# DL0WH_BiTuner_MCU_1V0.net
KiCad netlist of a schematic drawn in EAGLE
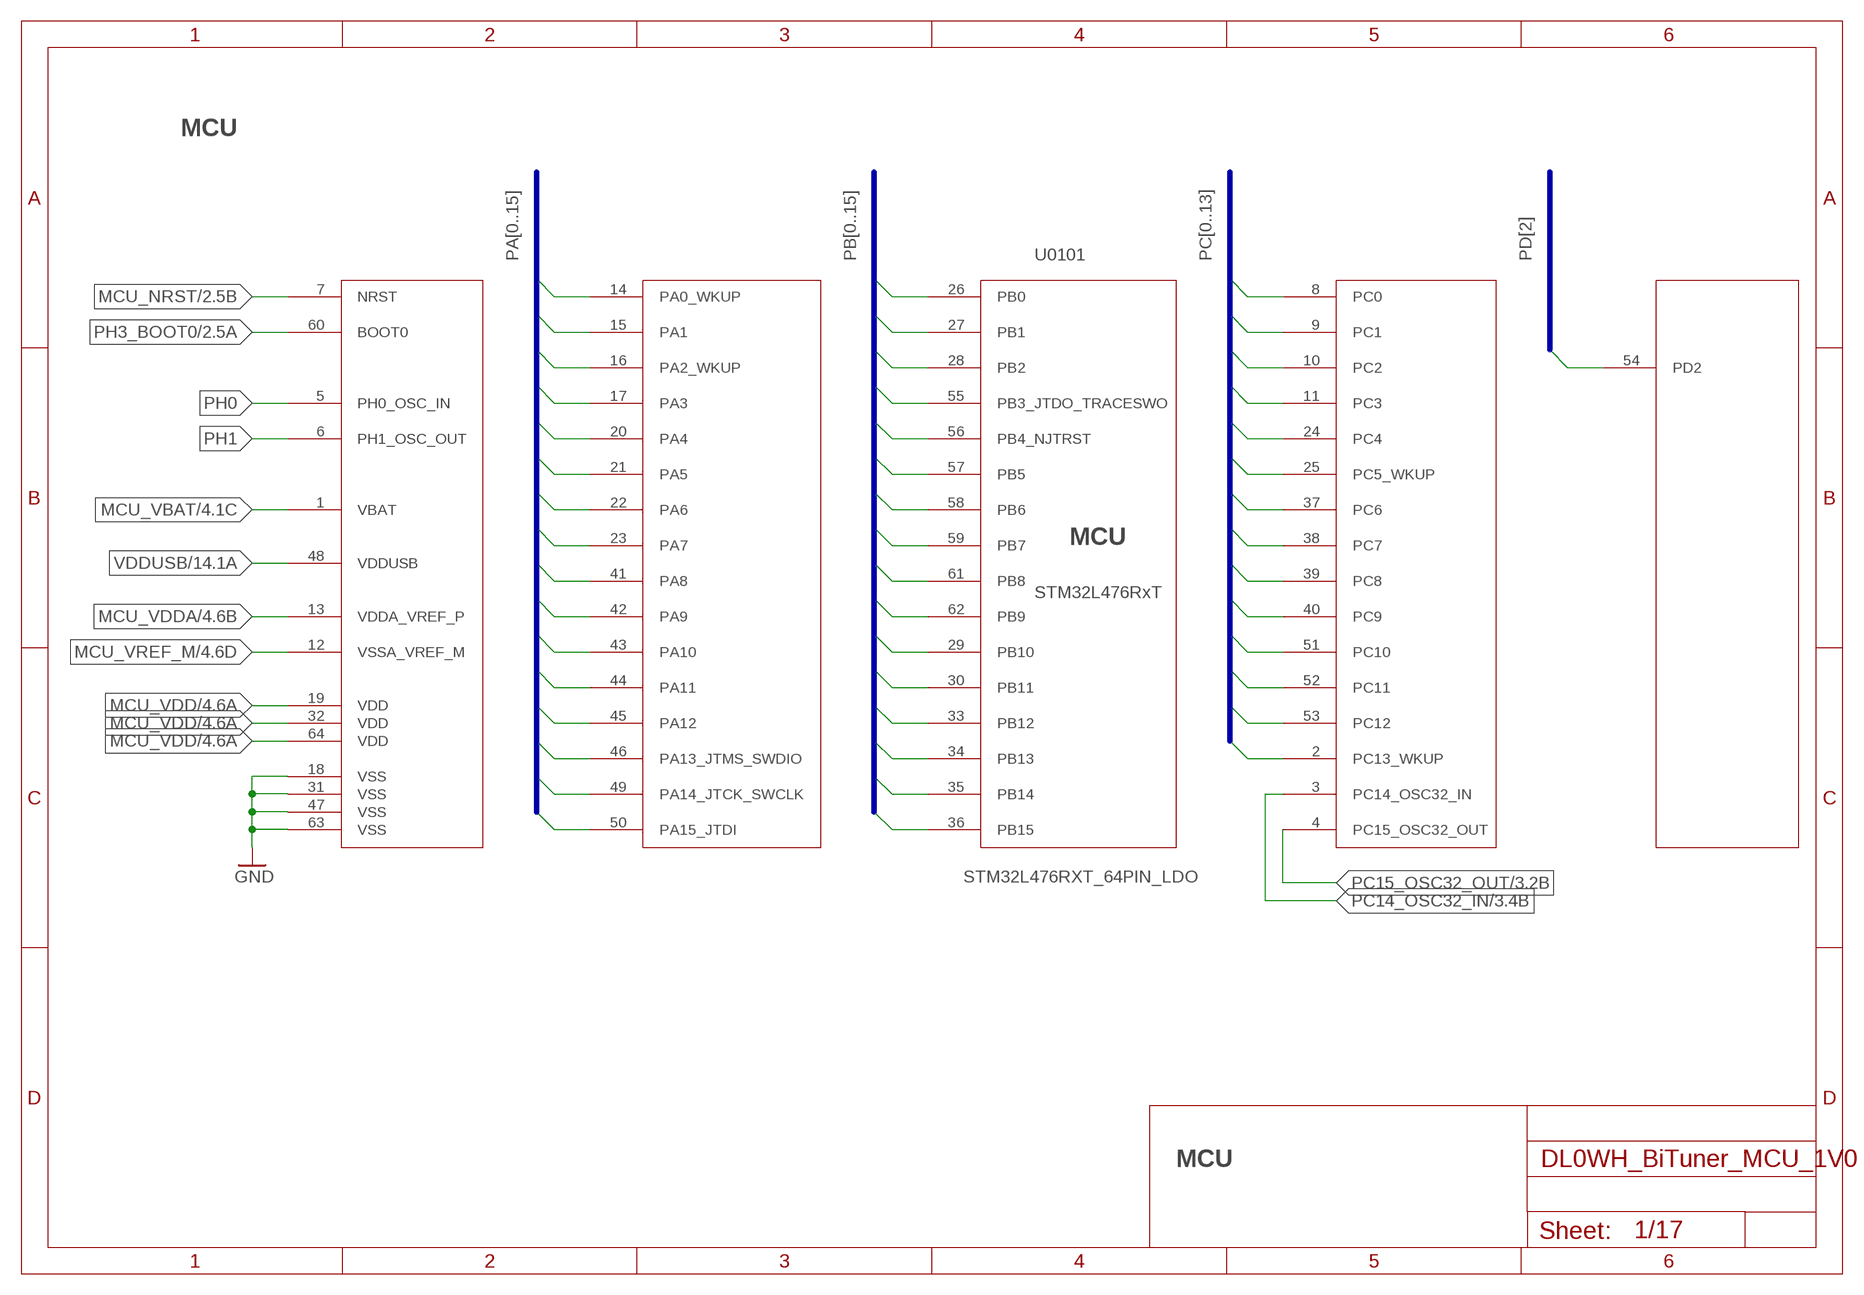
[diagram p0: schematic, sheet 1]
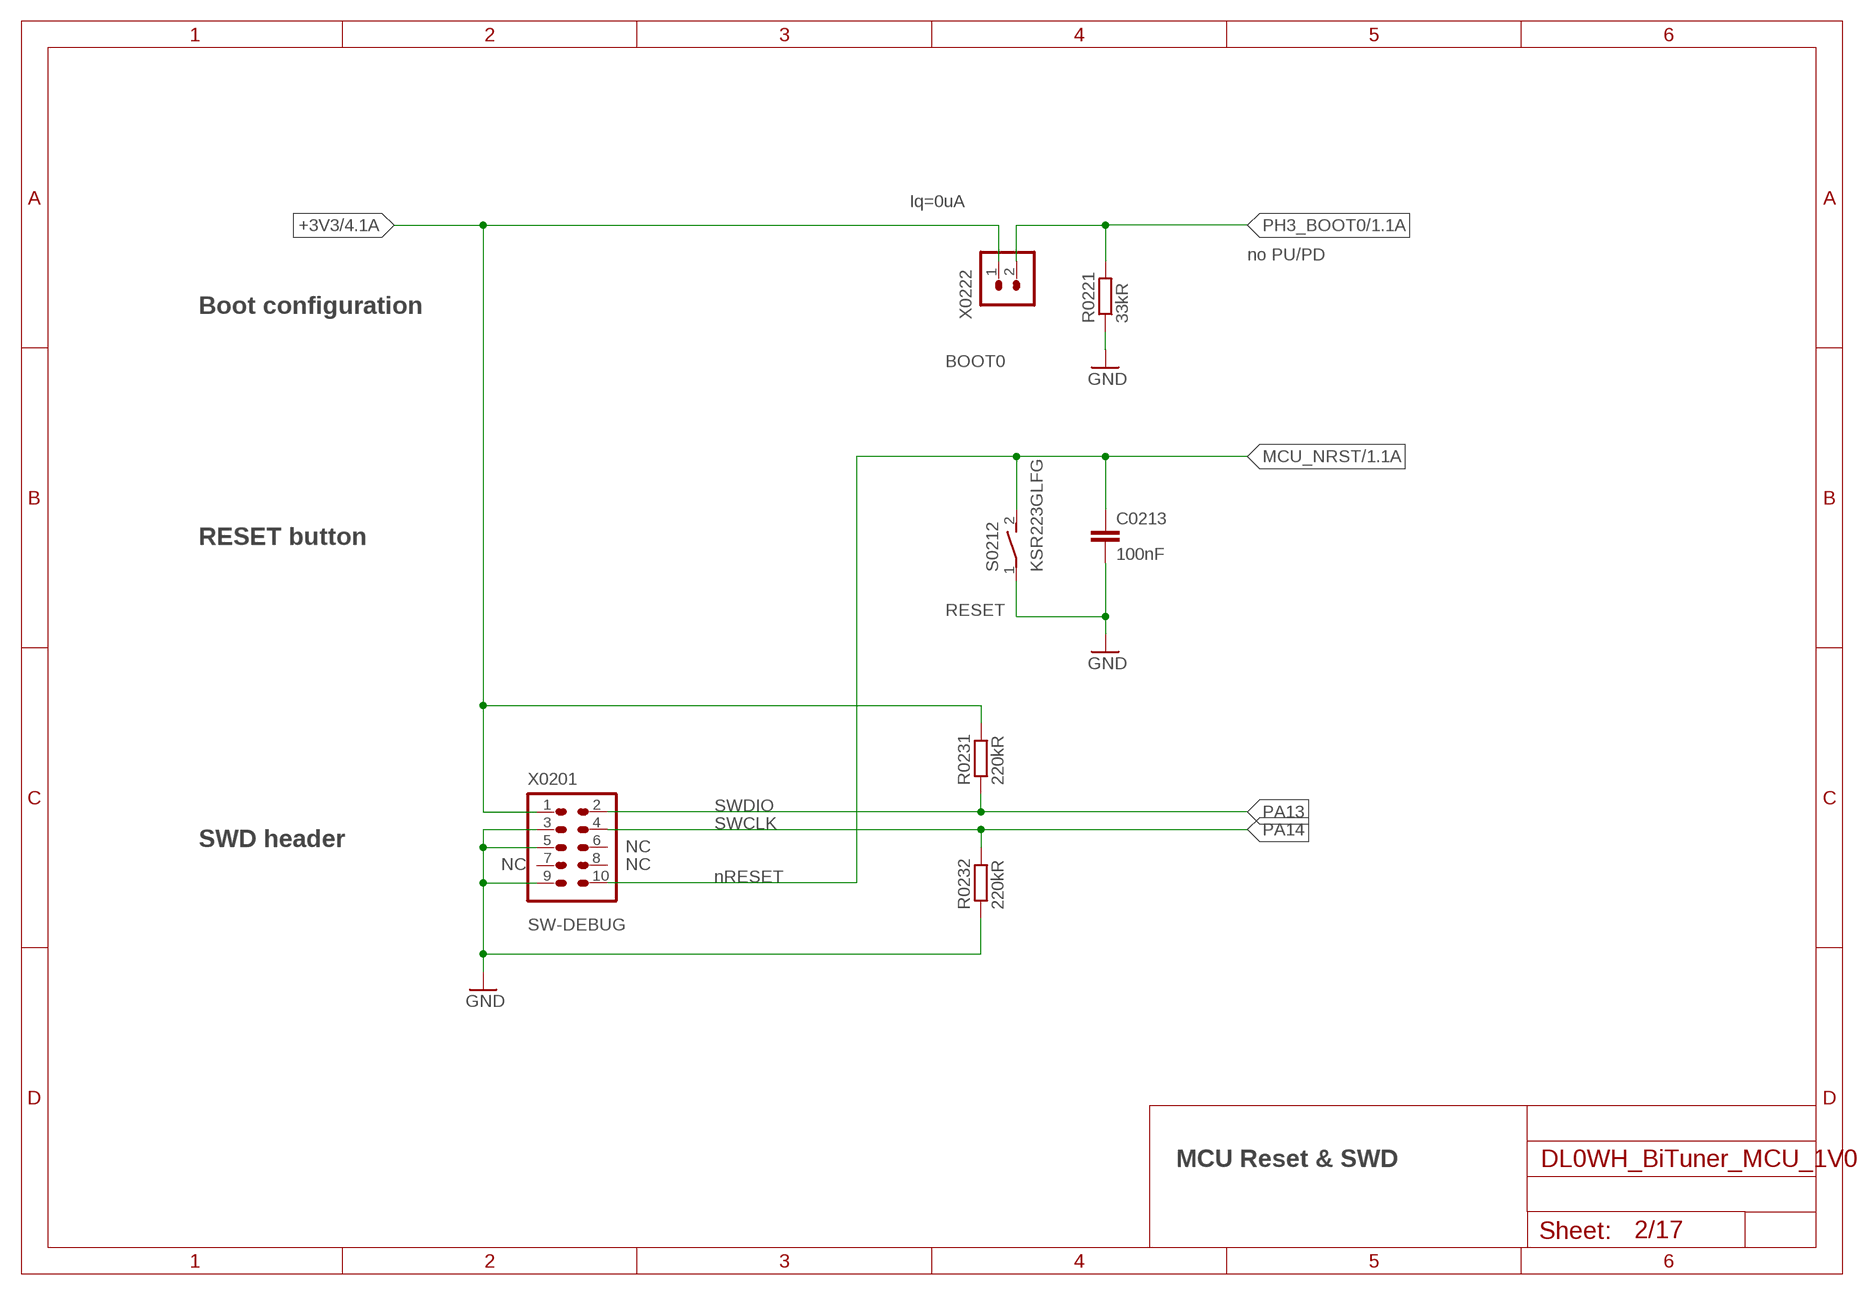
[diagram p1: schematic, sheet 2]
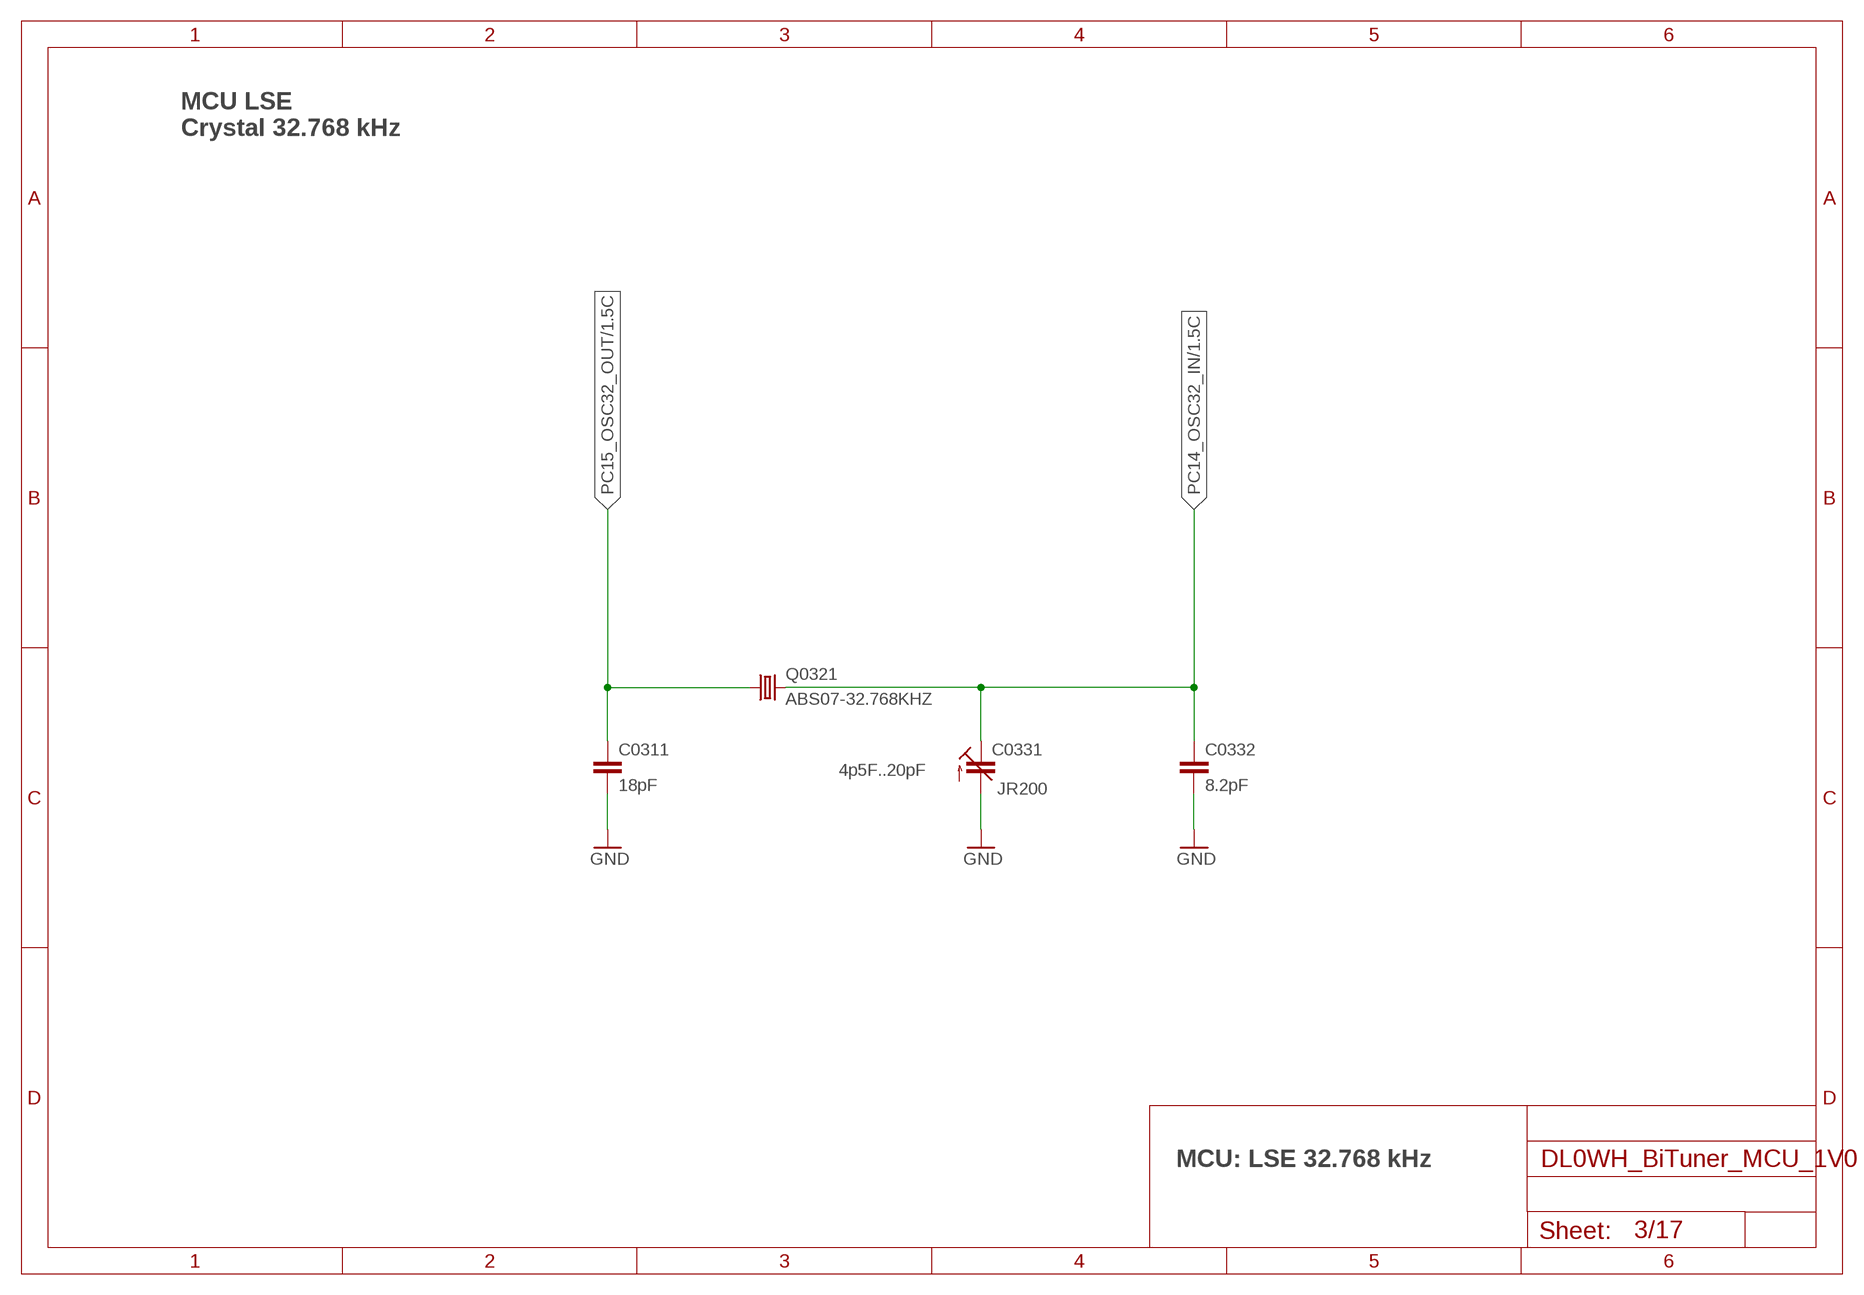
[diagram p2: schematic, sheet 3]
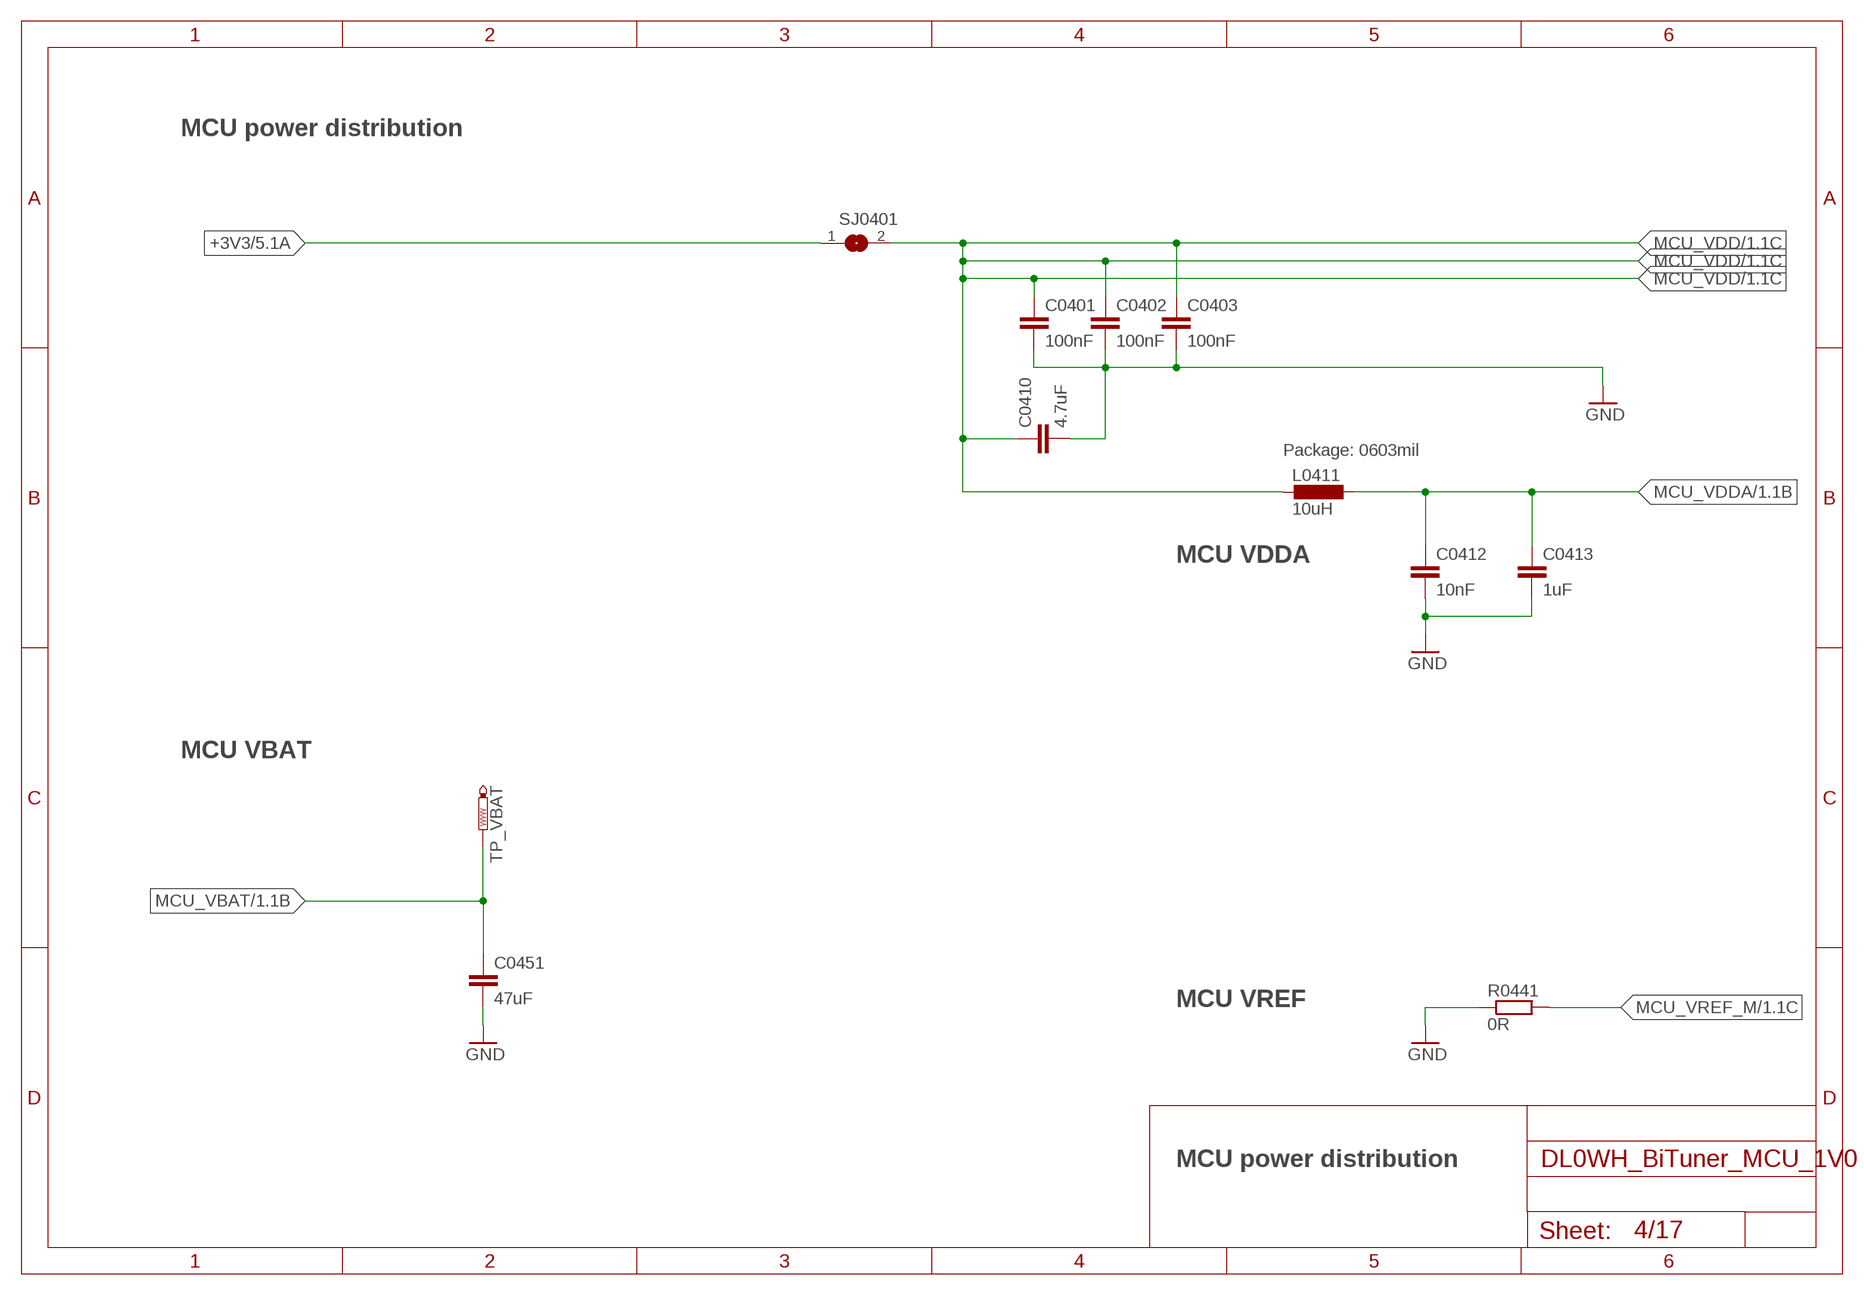
[diagram p3: schematic, sheet 4]
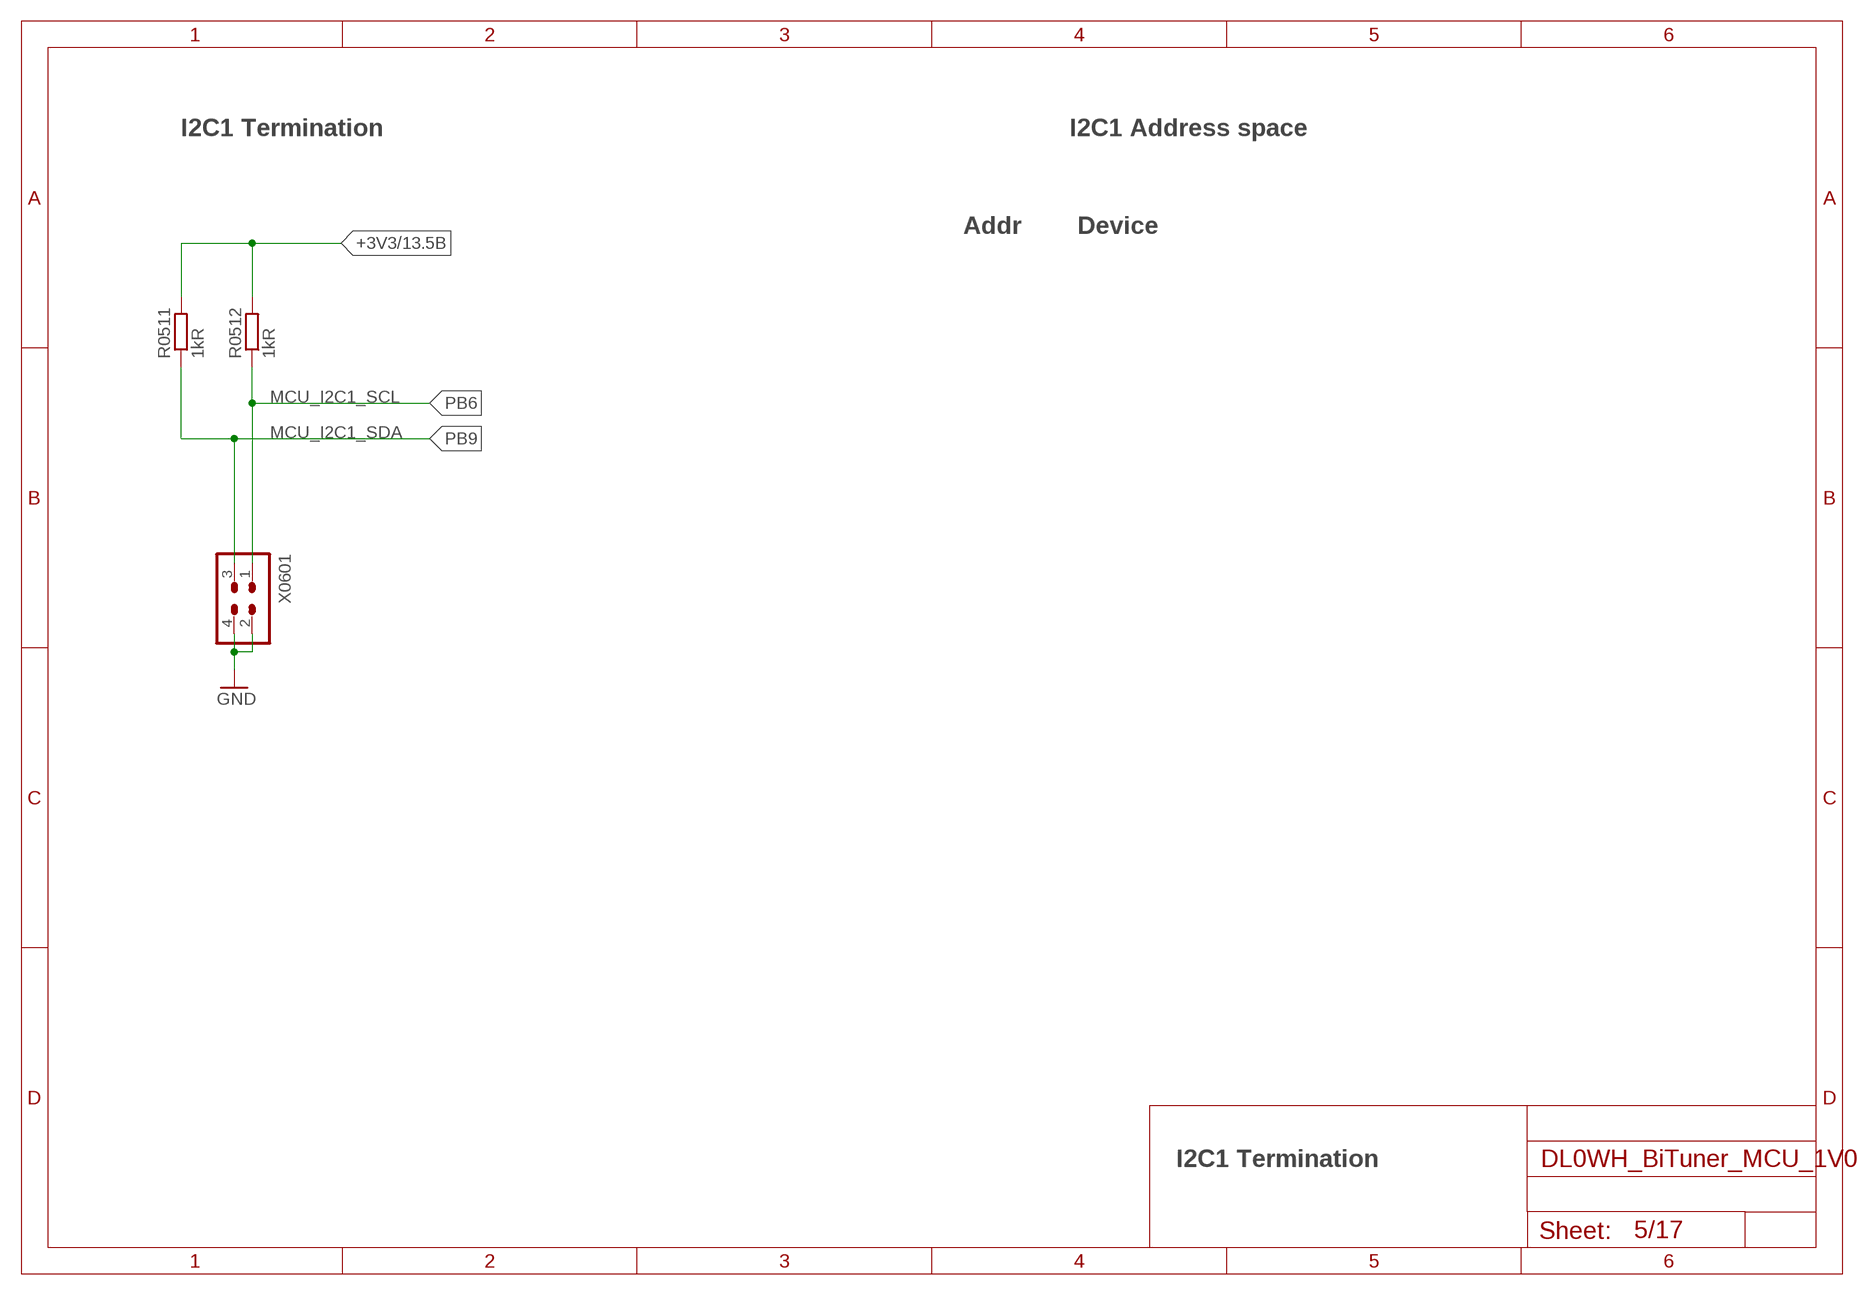
[diagram p4: schematic, sheet 5]
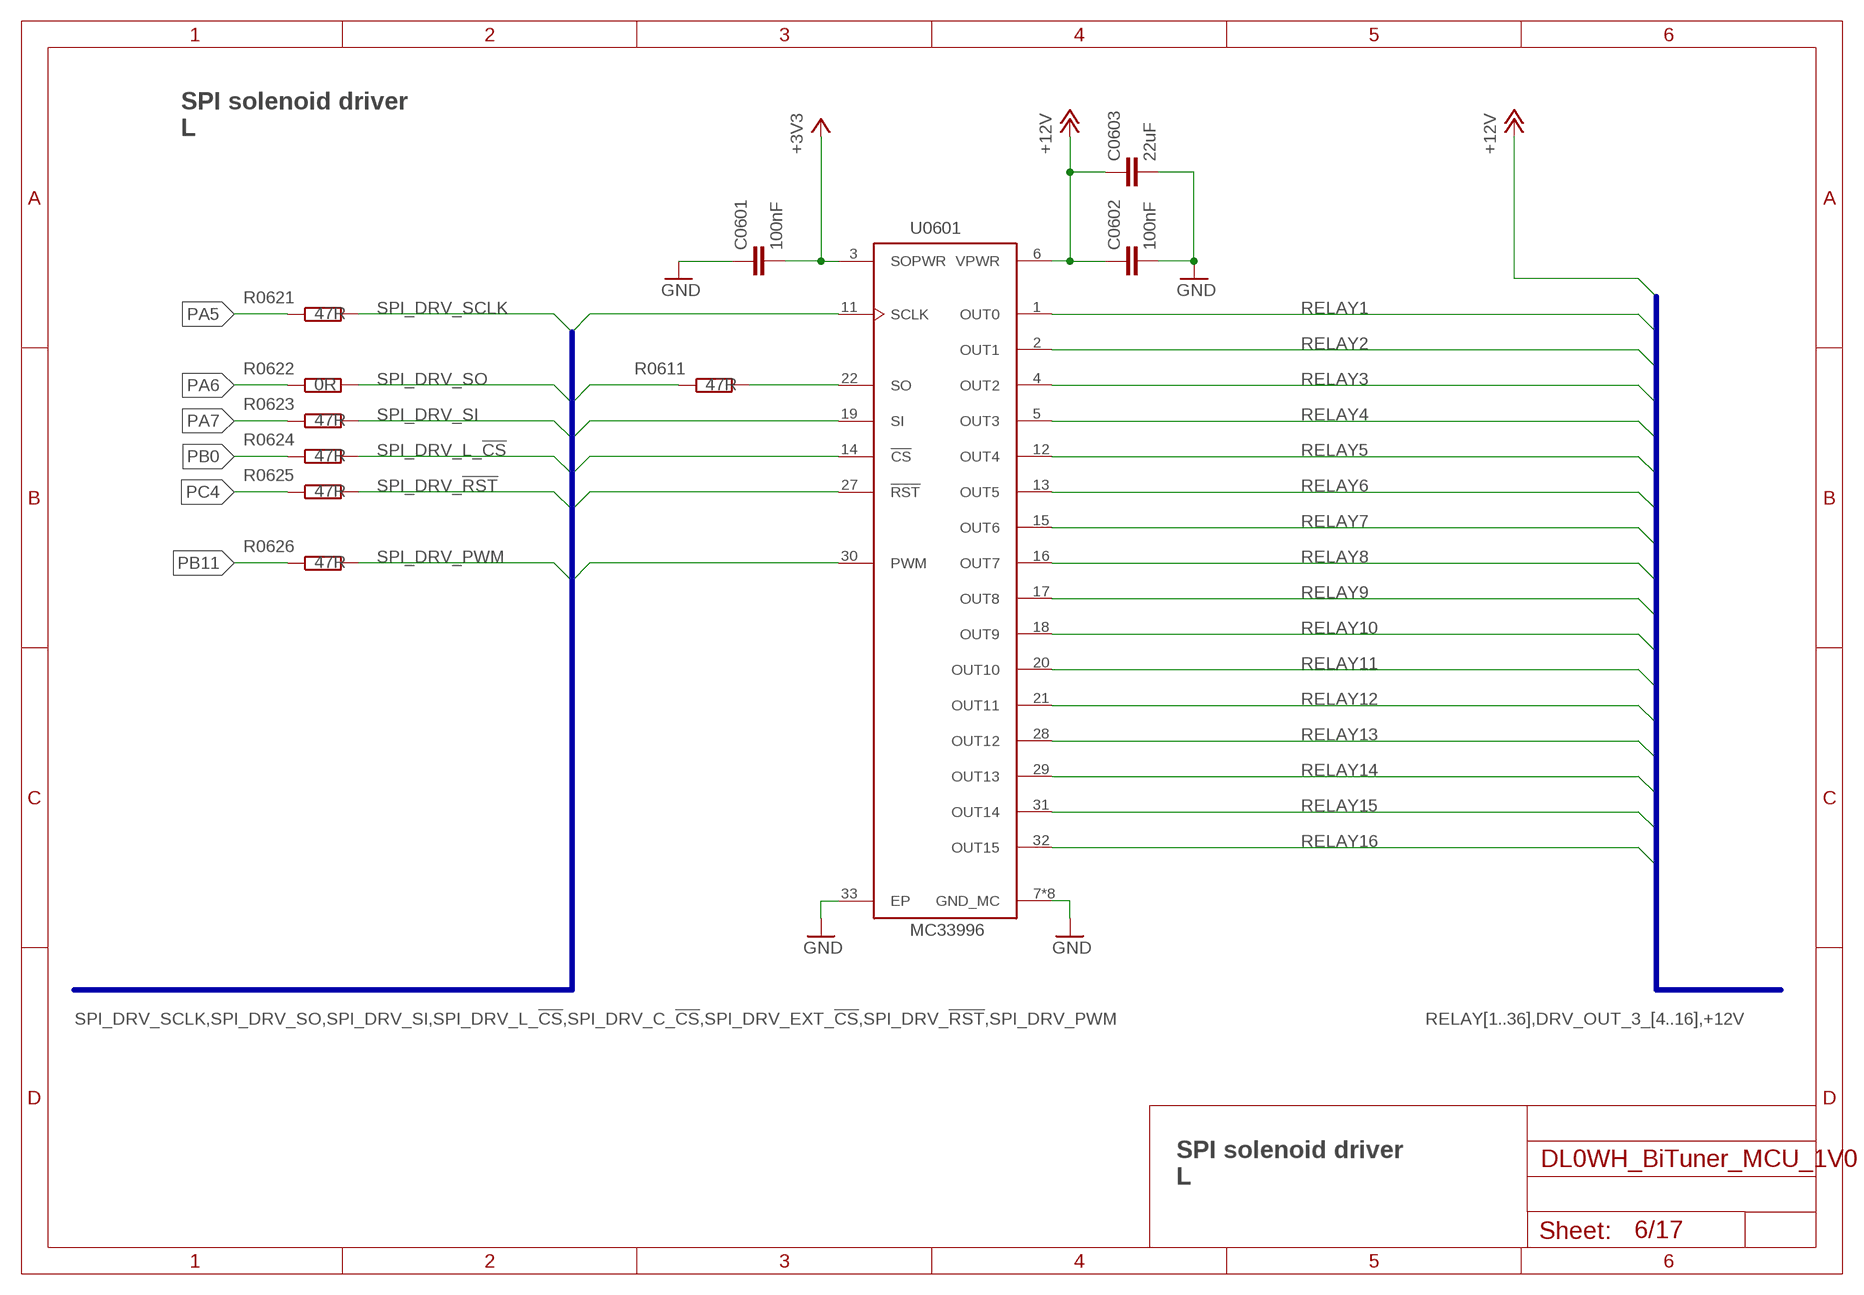
[diagram p5: schematic, sheet 6]
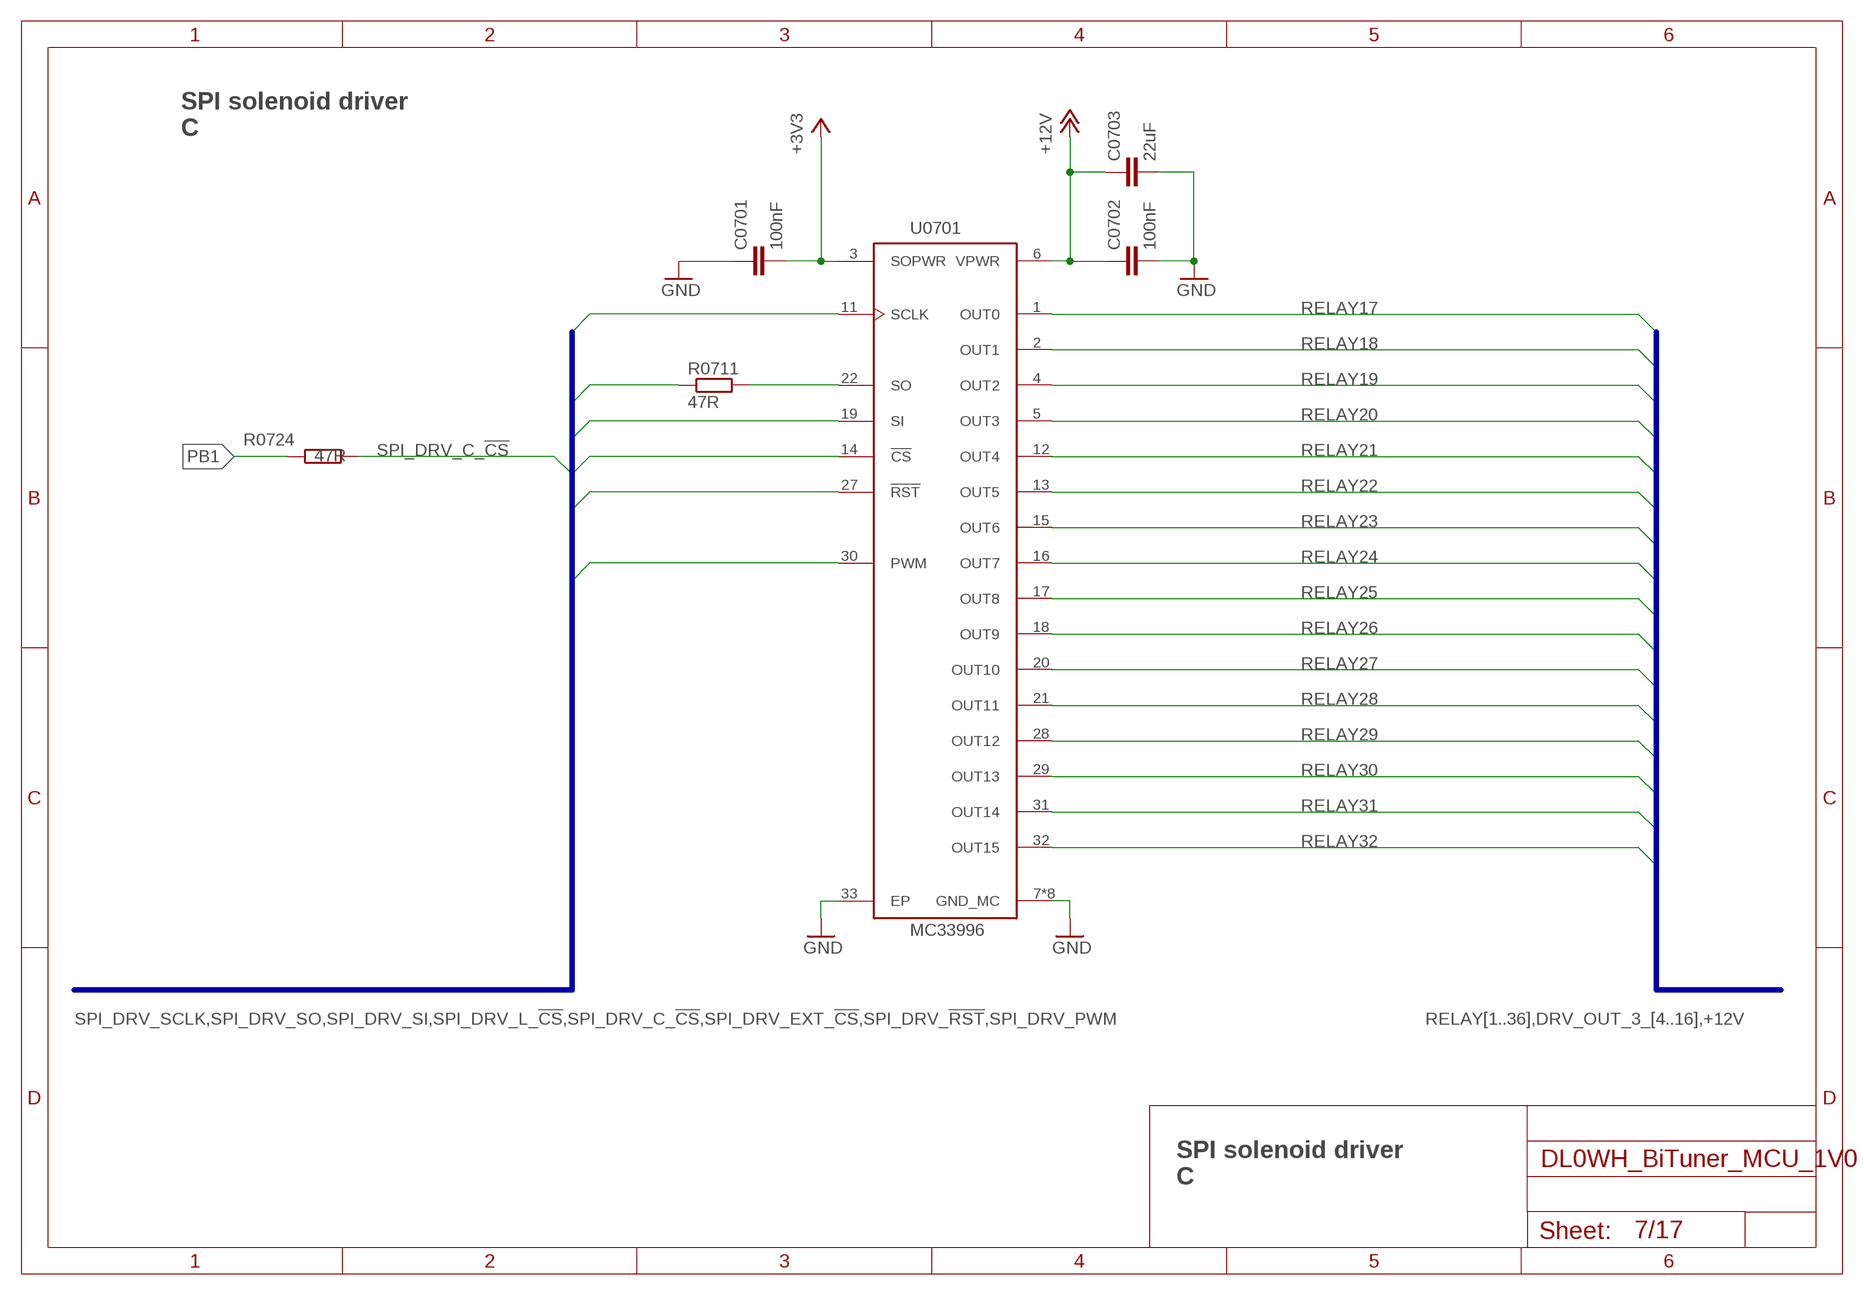
[diagram p6: schematic, sheet 7]
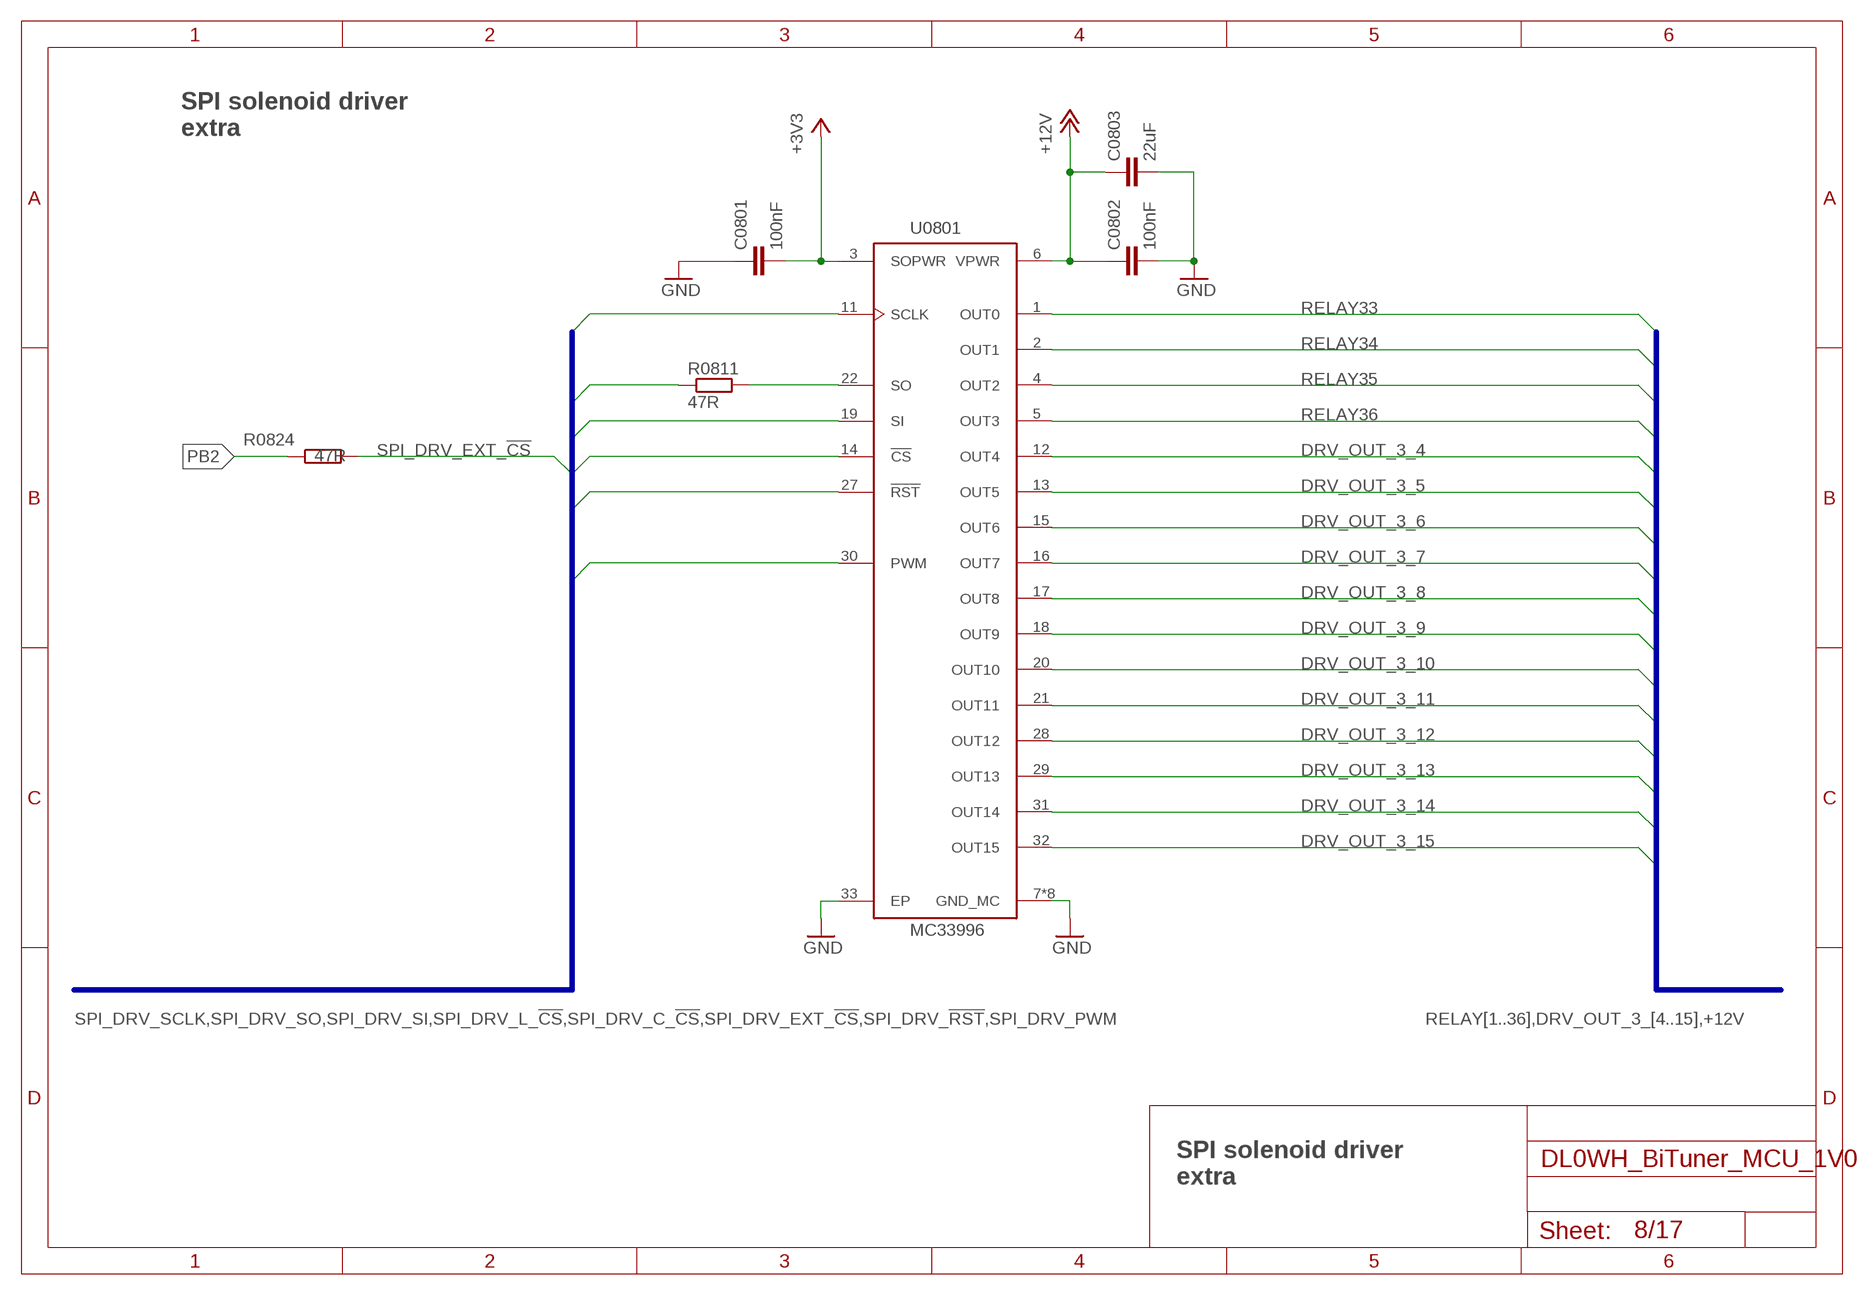
[diagram p7: schematic, sheet 8]
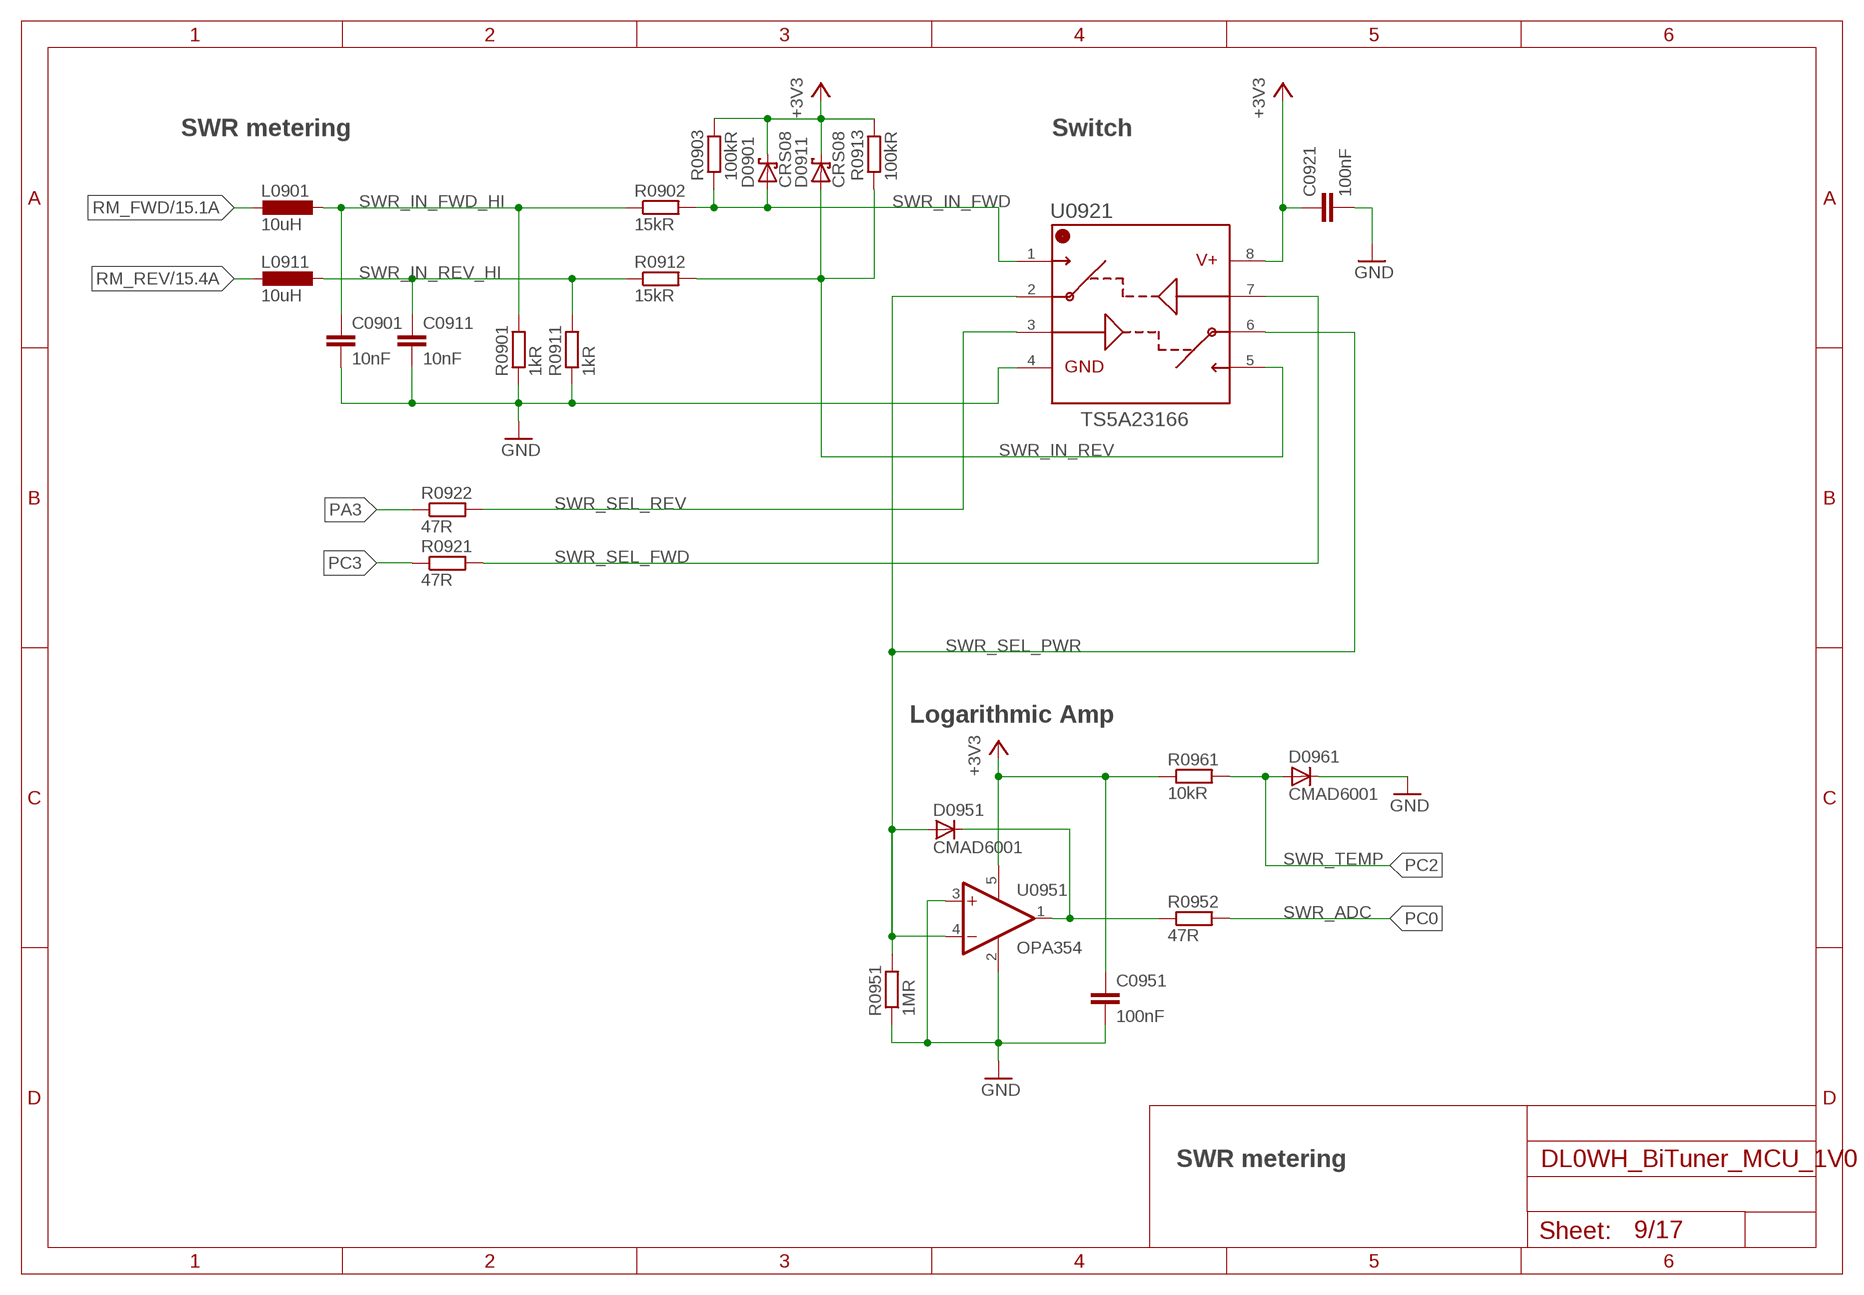
[diagram p8: schematic, sheet 9]
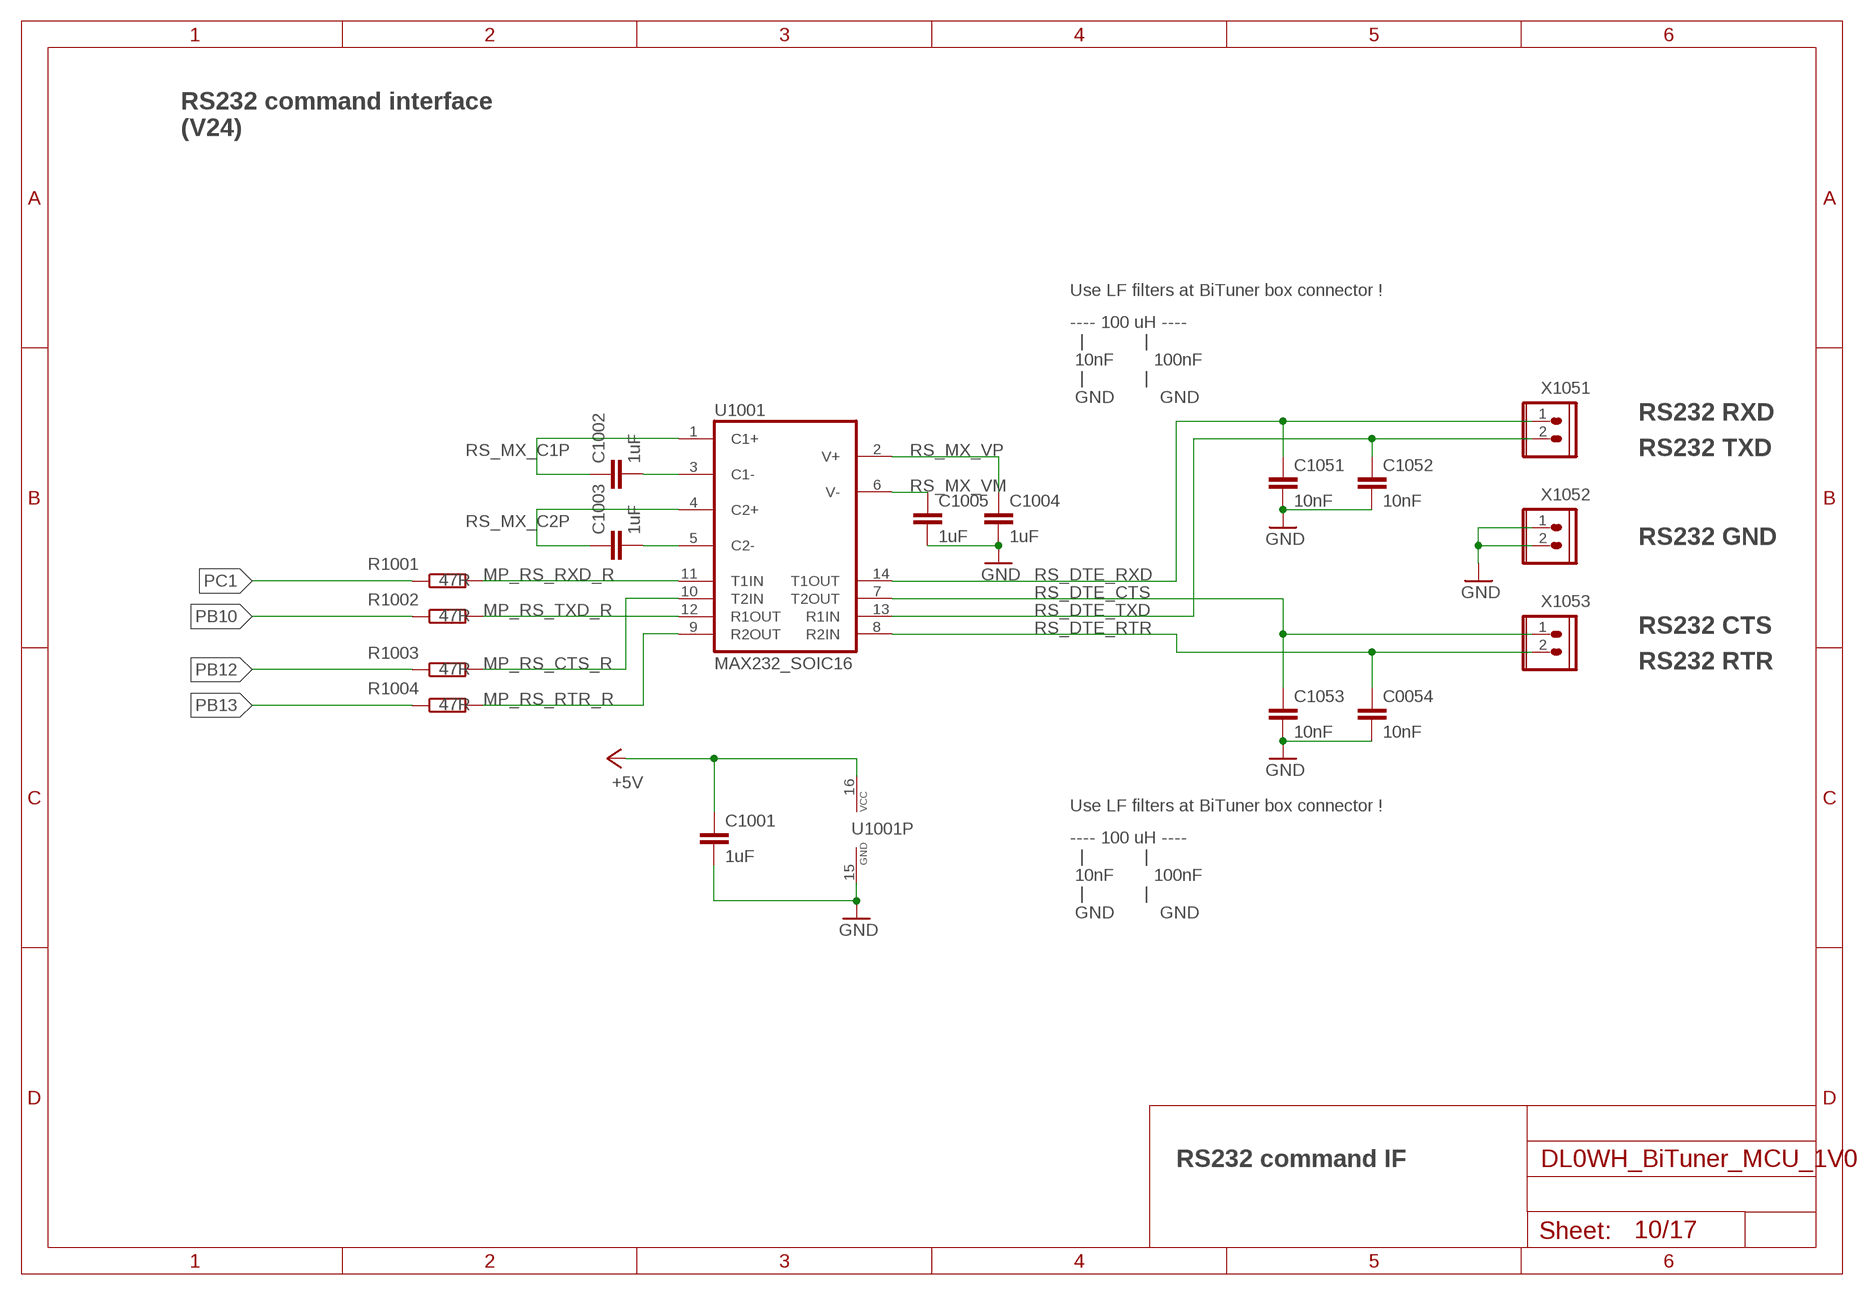
[diagram p9: schematic, sheet 10]
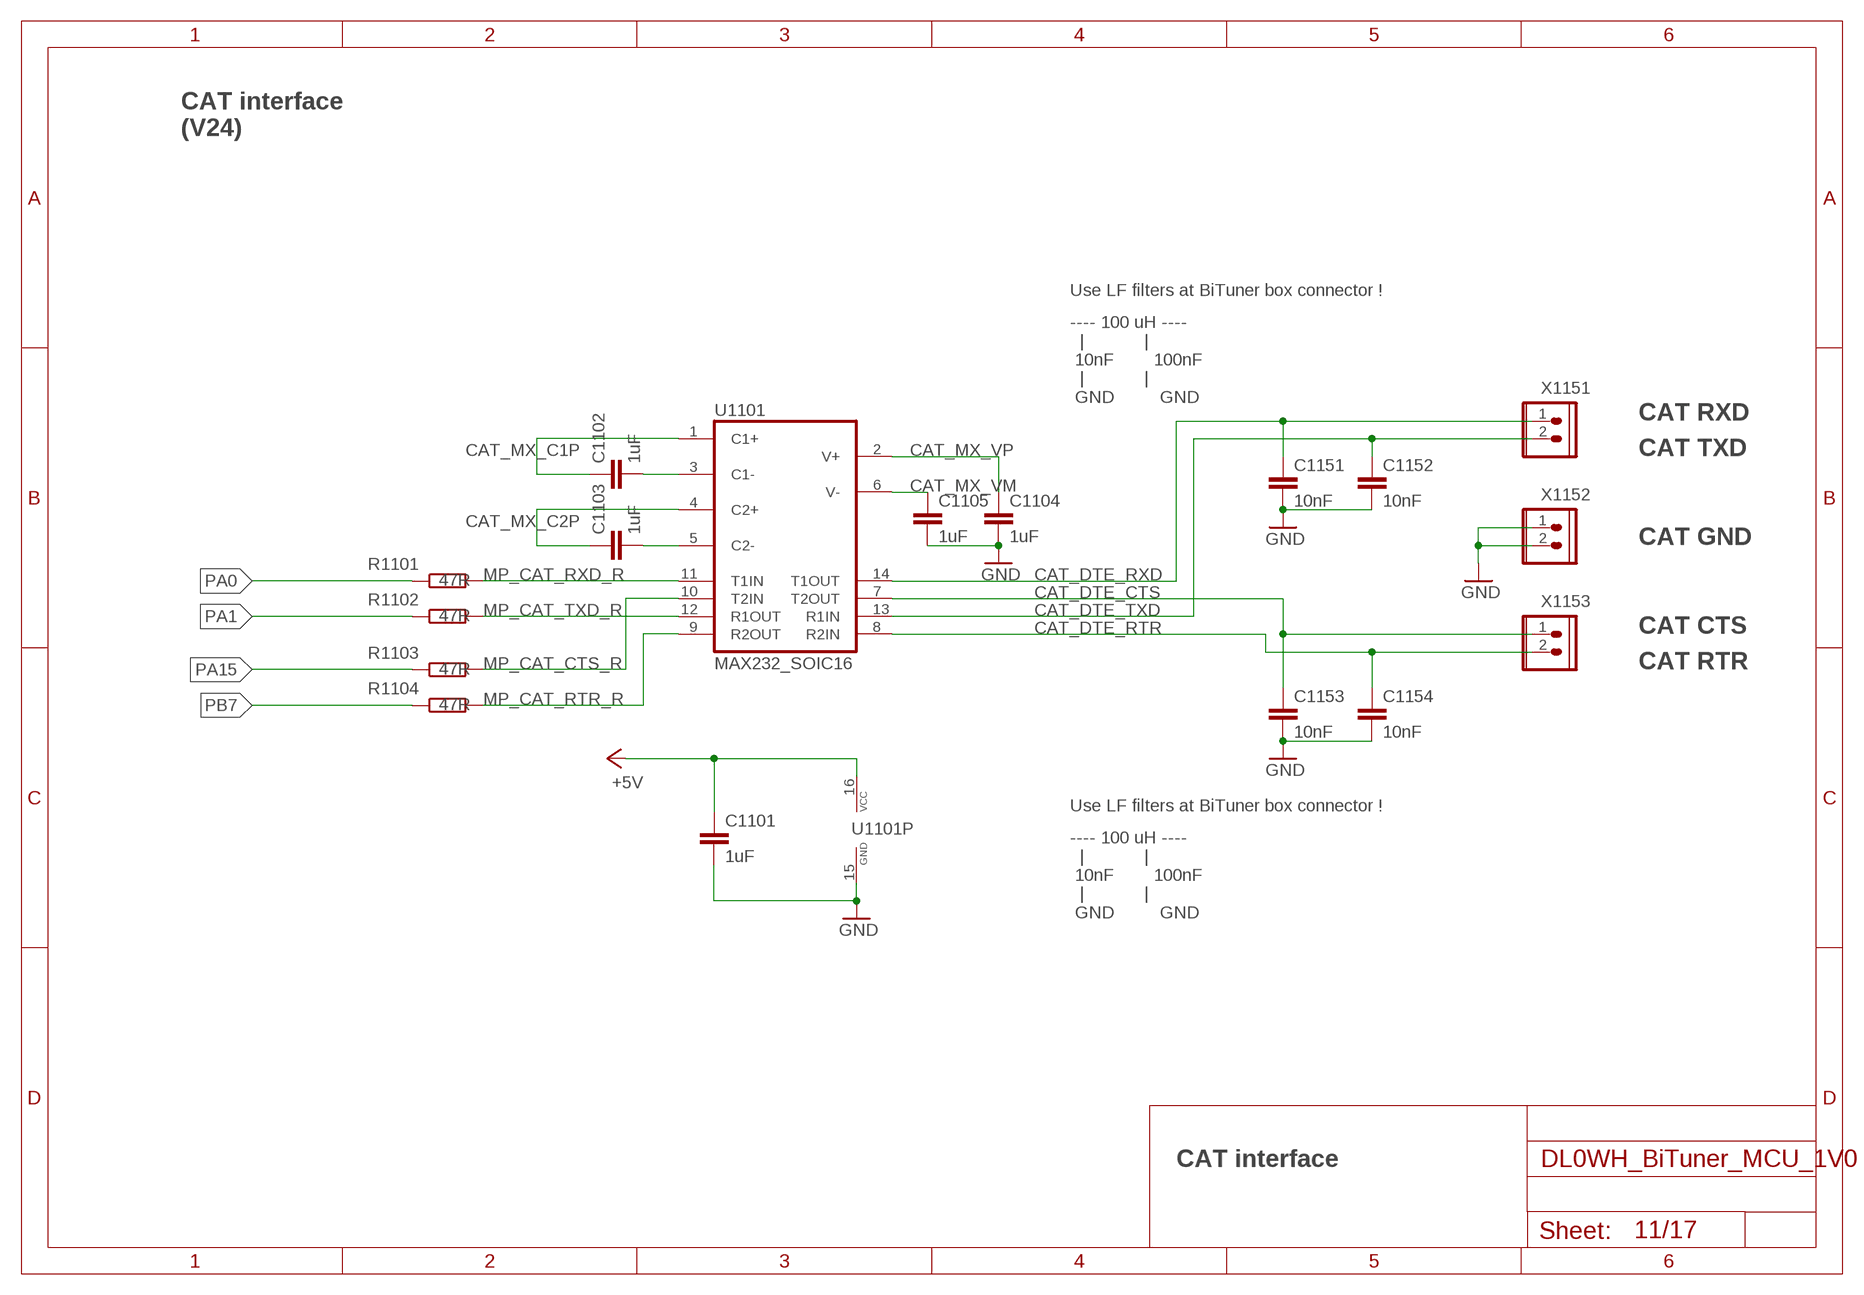
[diagram p10: schematic, sheet 11]
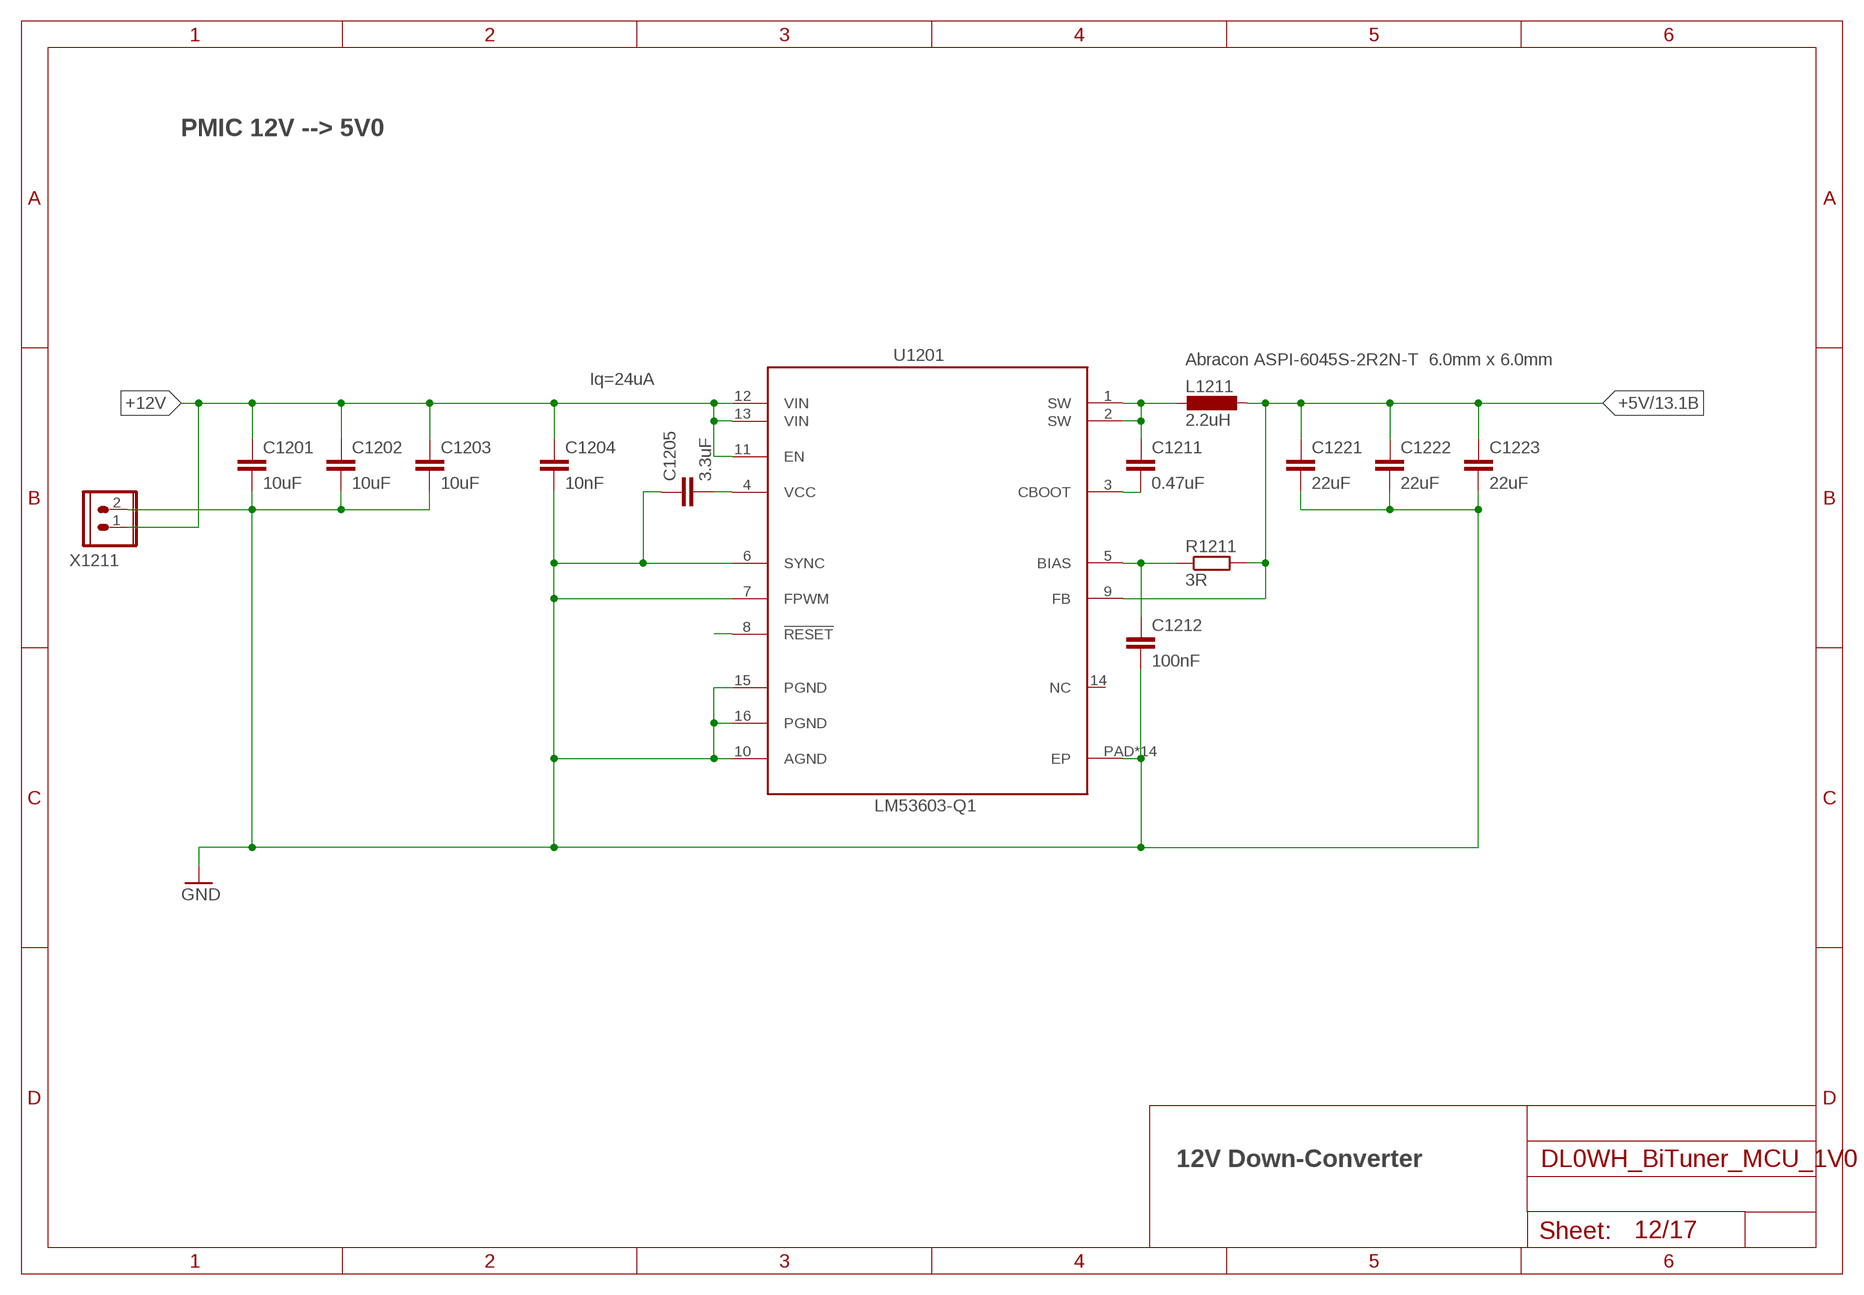
[diagram p11: schematic, sheet 12]
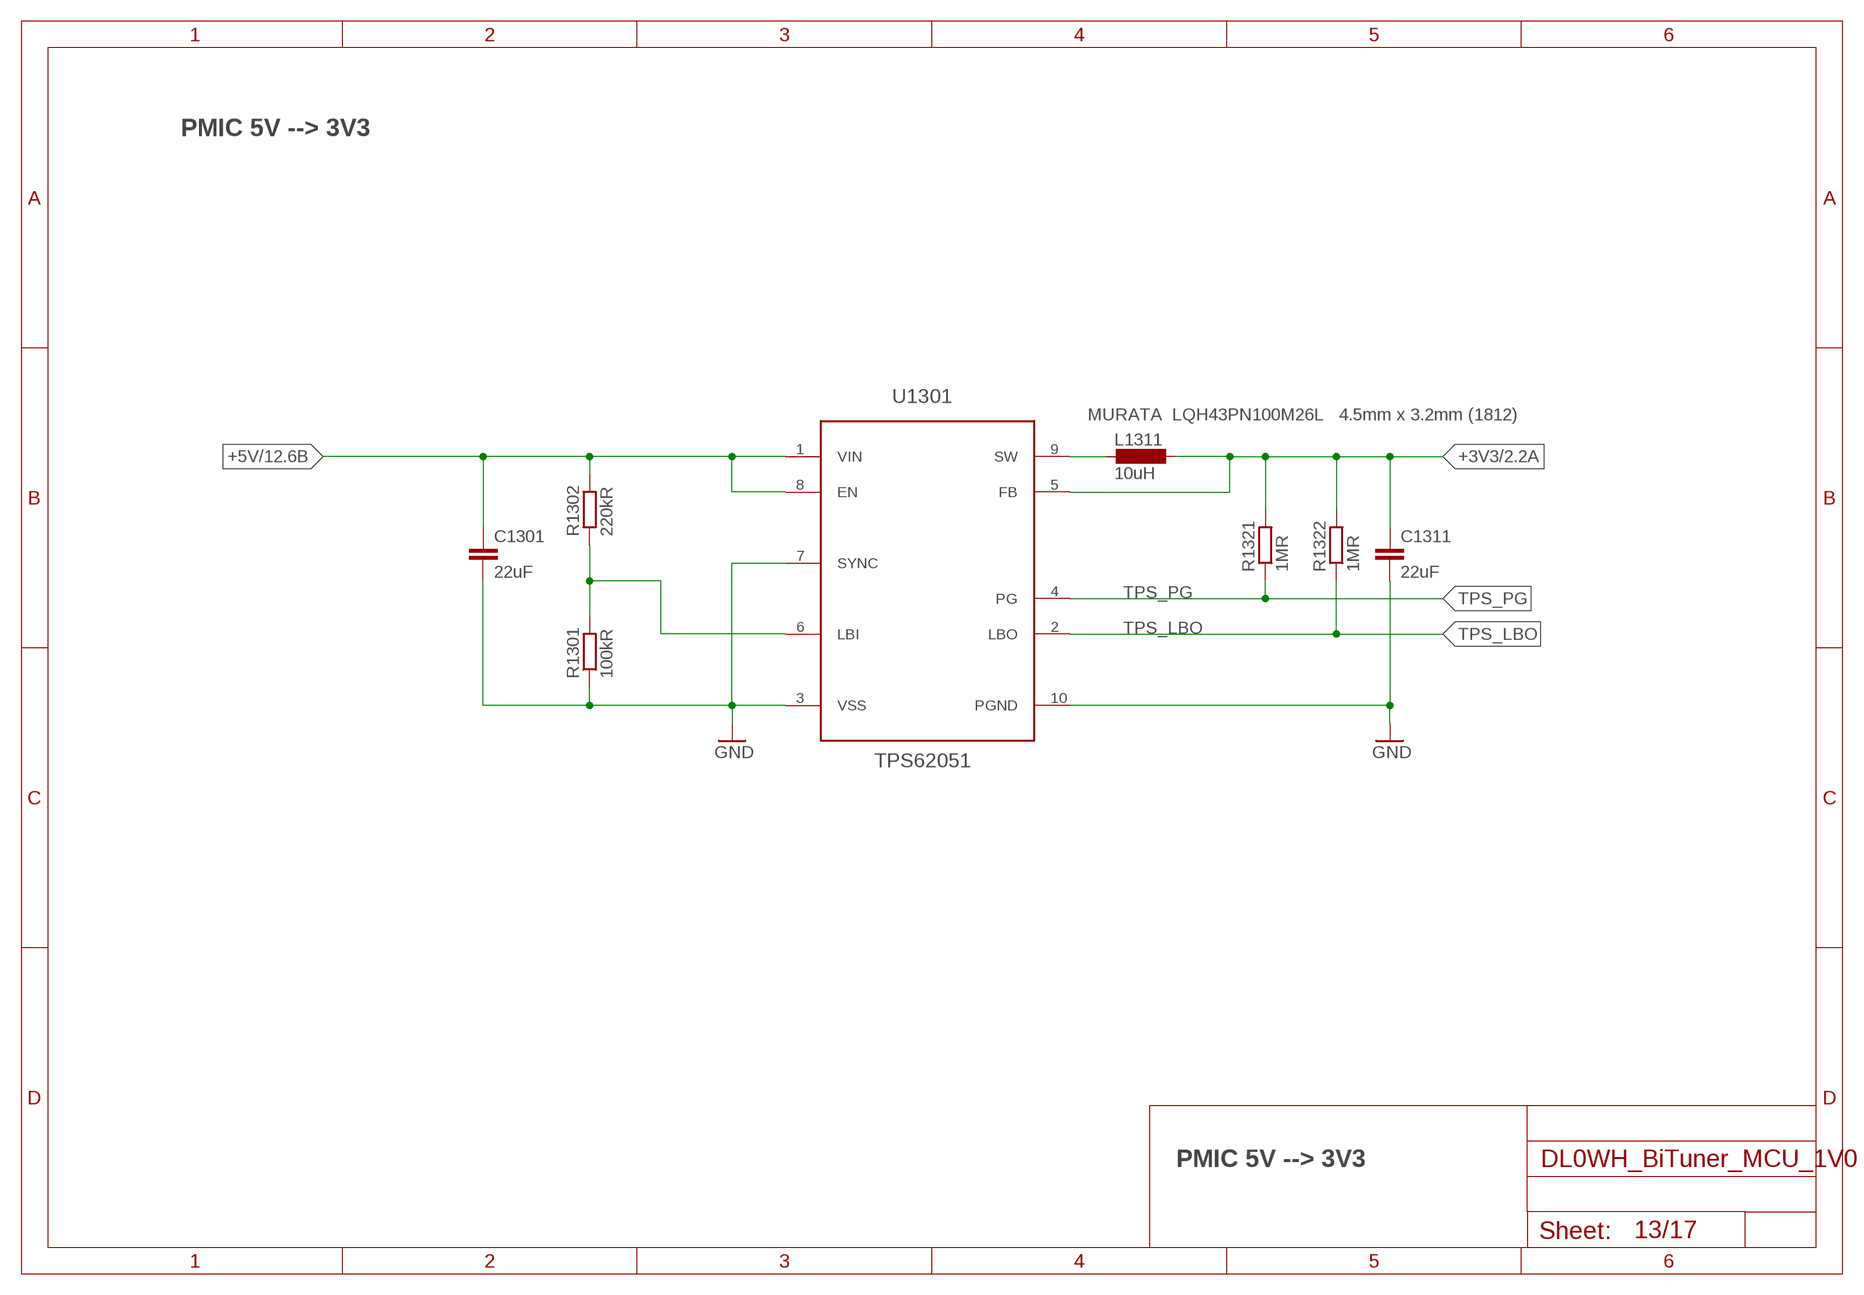
[diagram p12: schematic, sheet 13]
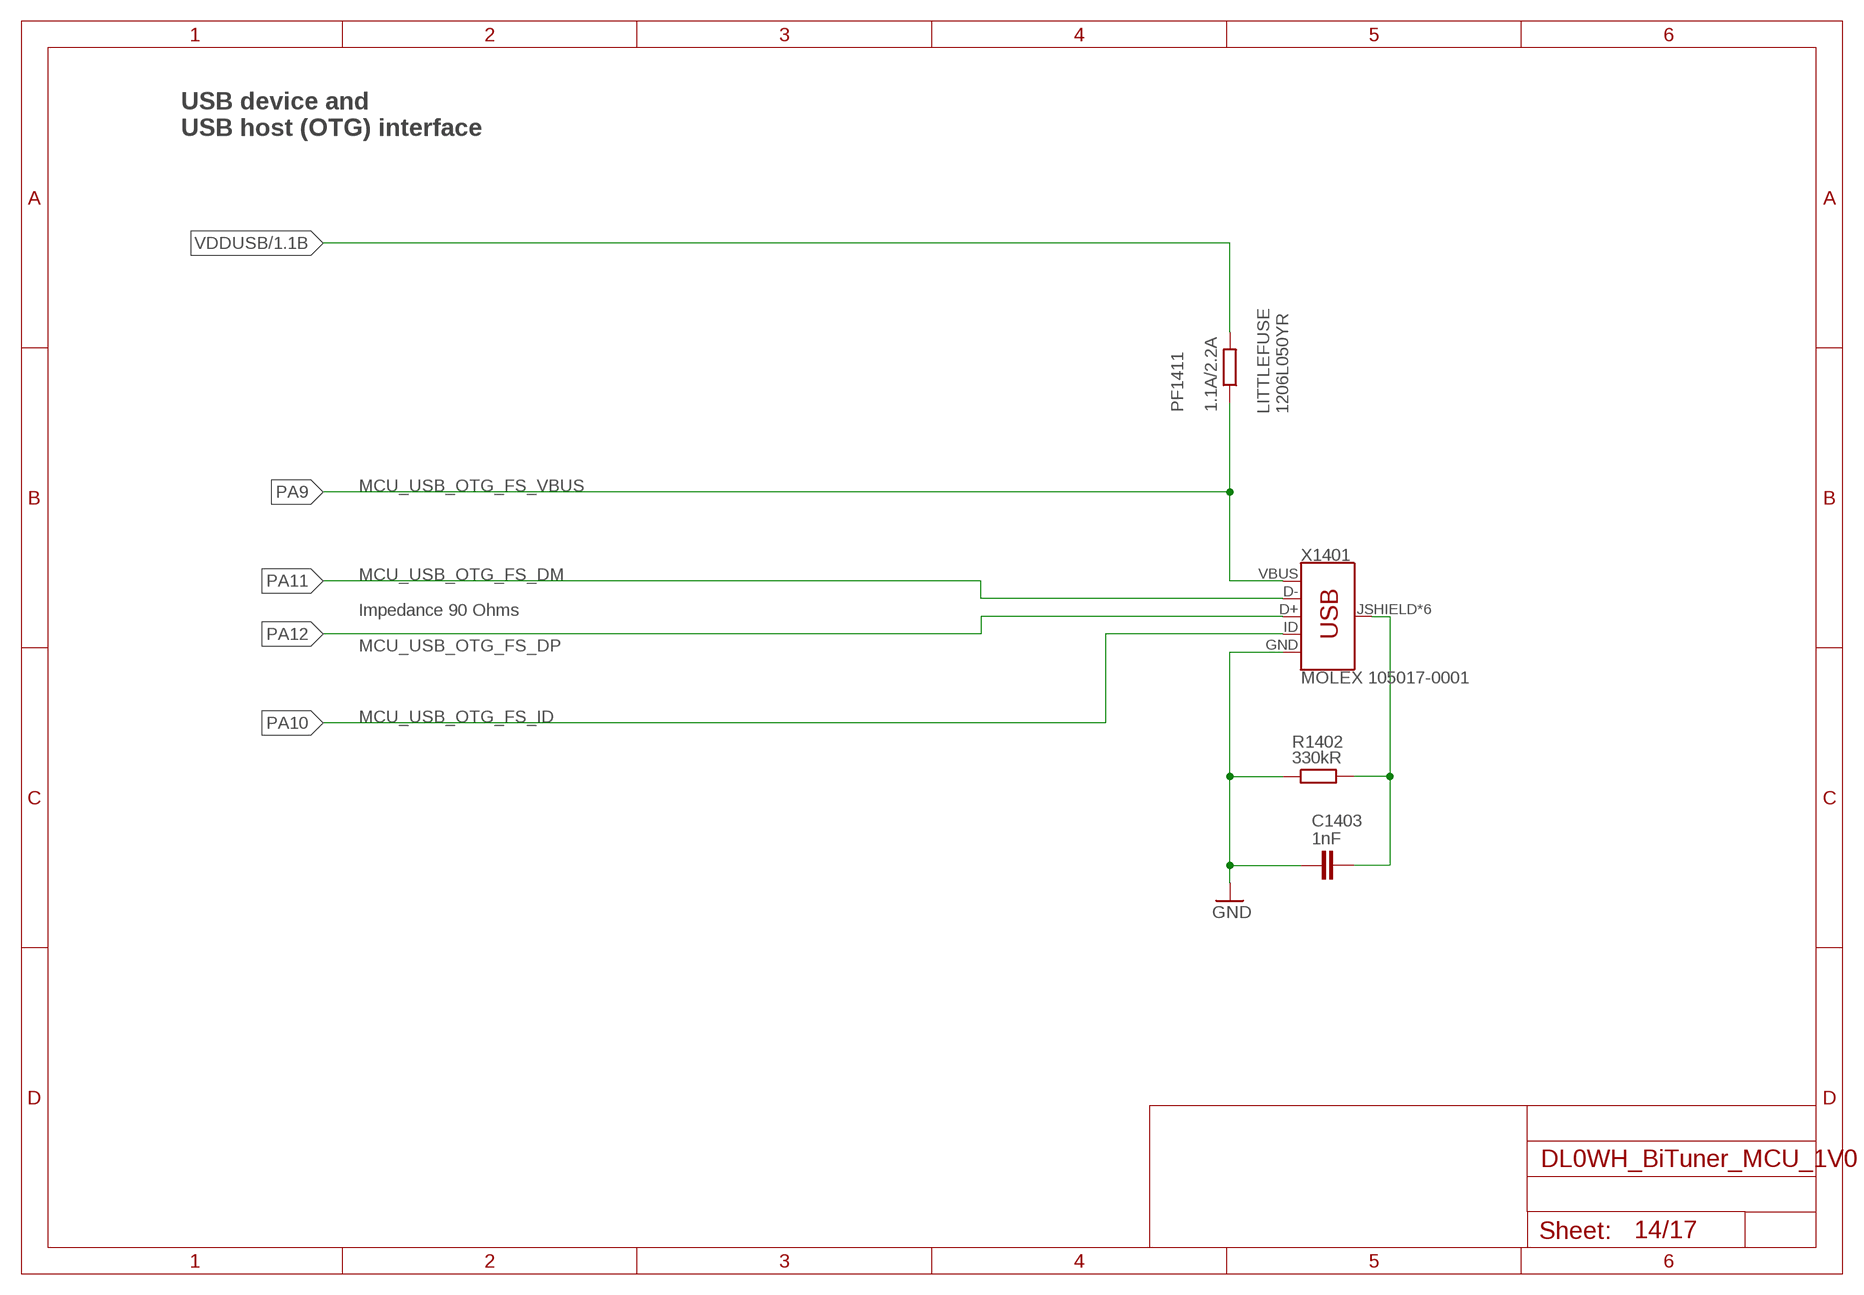
[diagram p13: schematic, sheet 14]
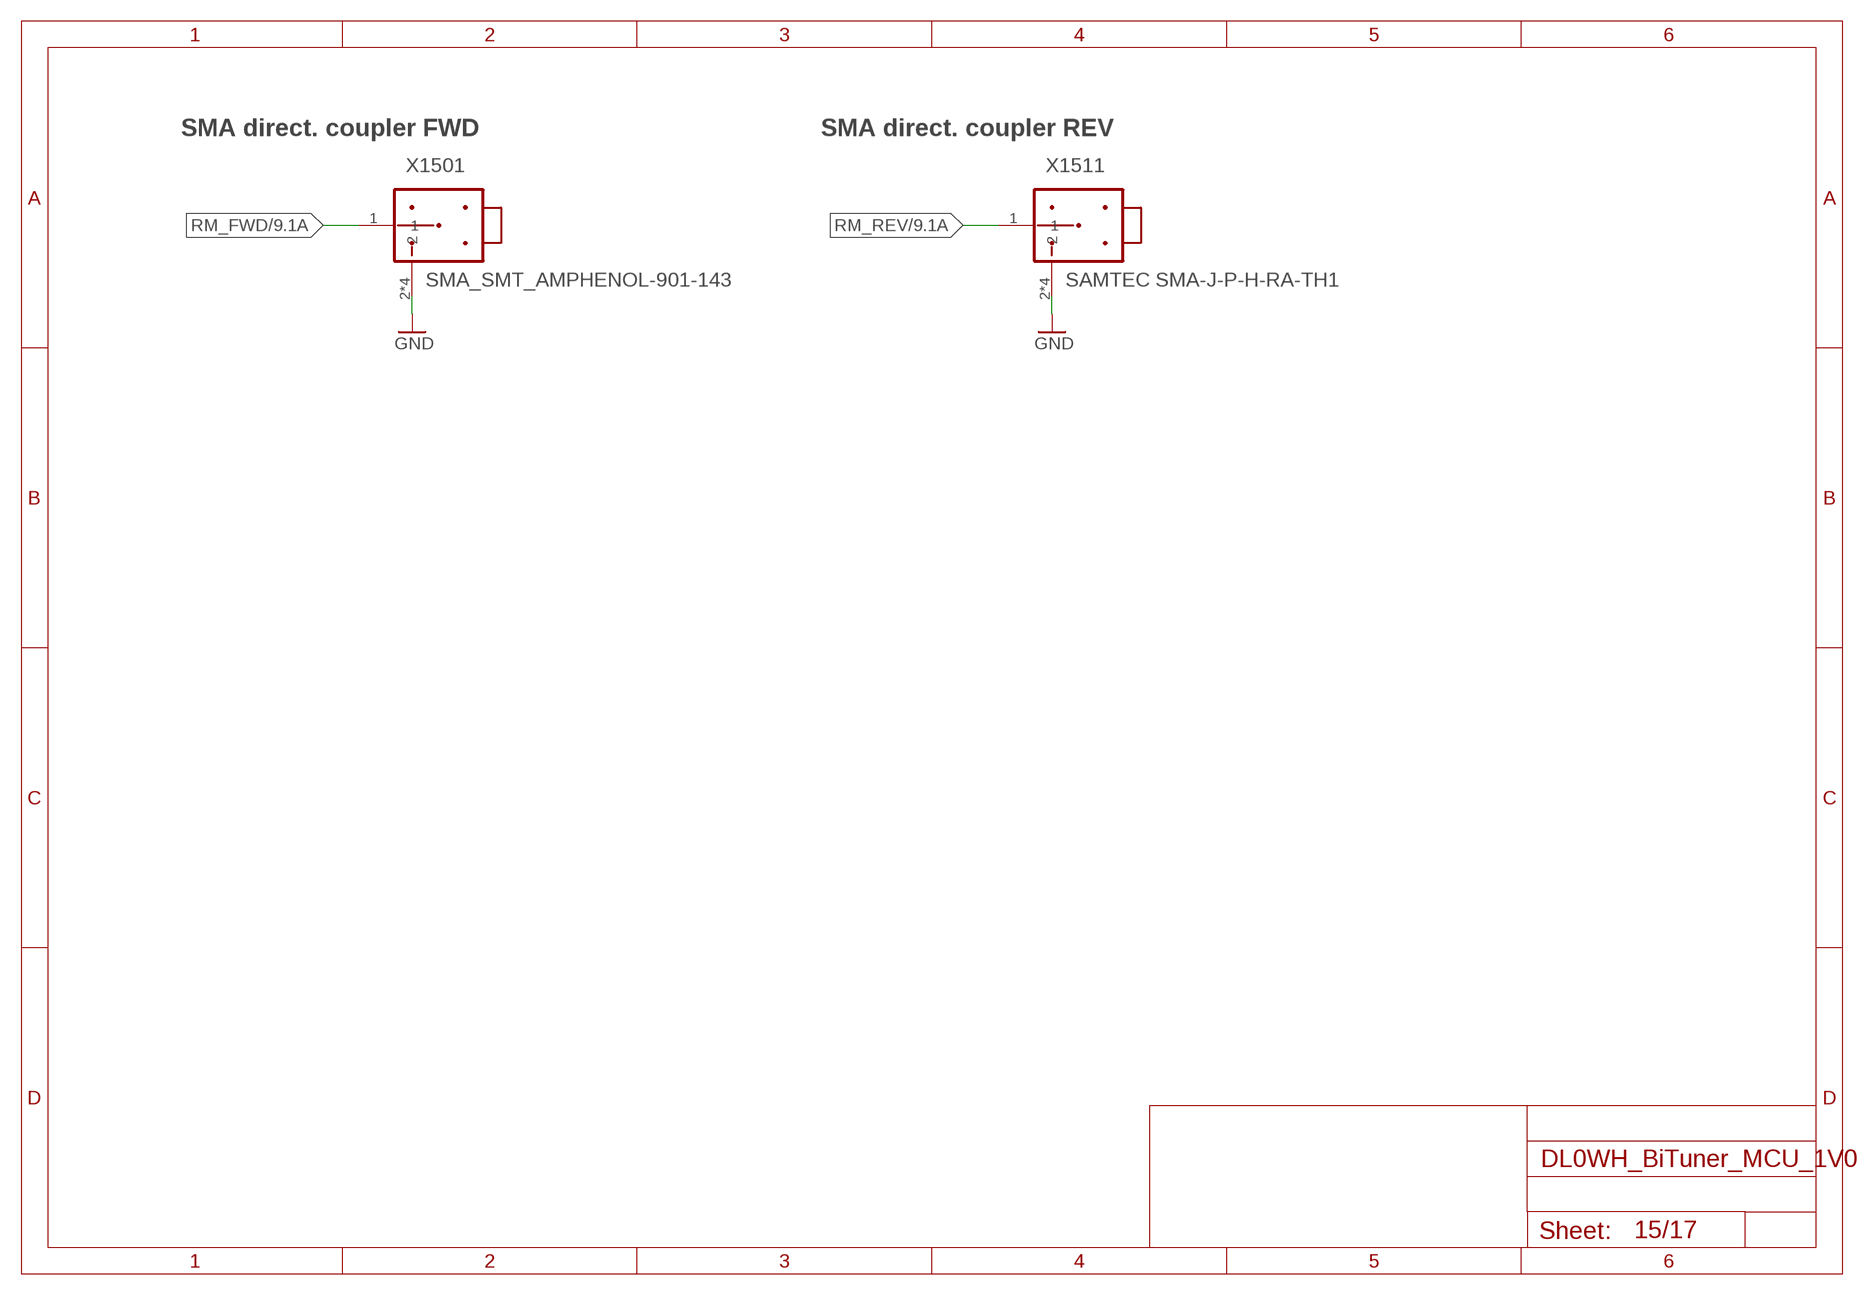
[diagram p14: schematic, sheet 15]
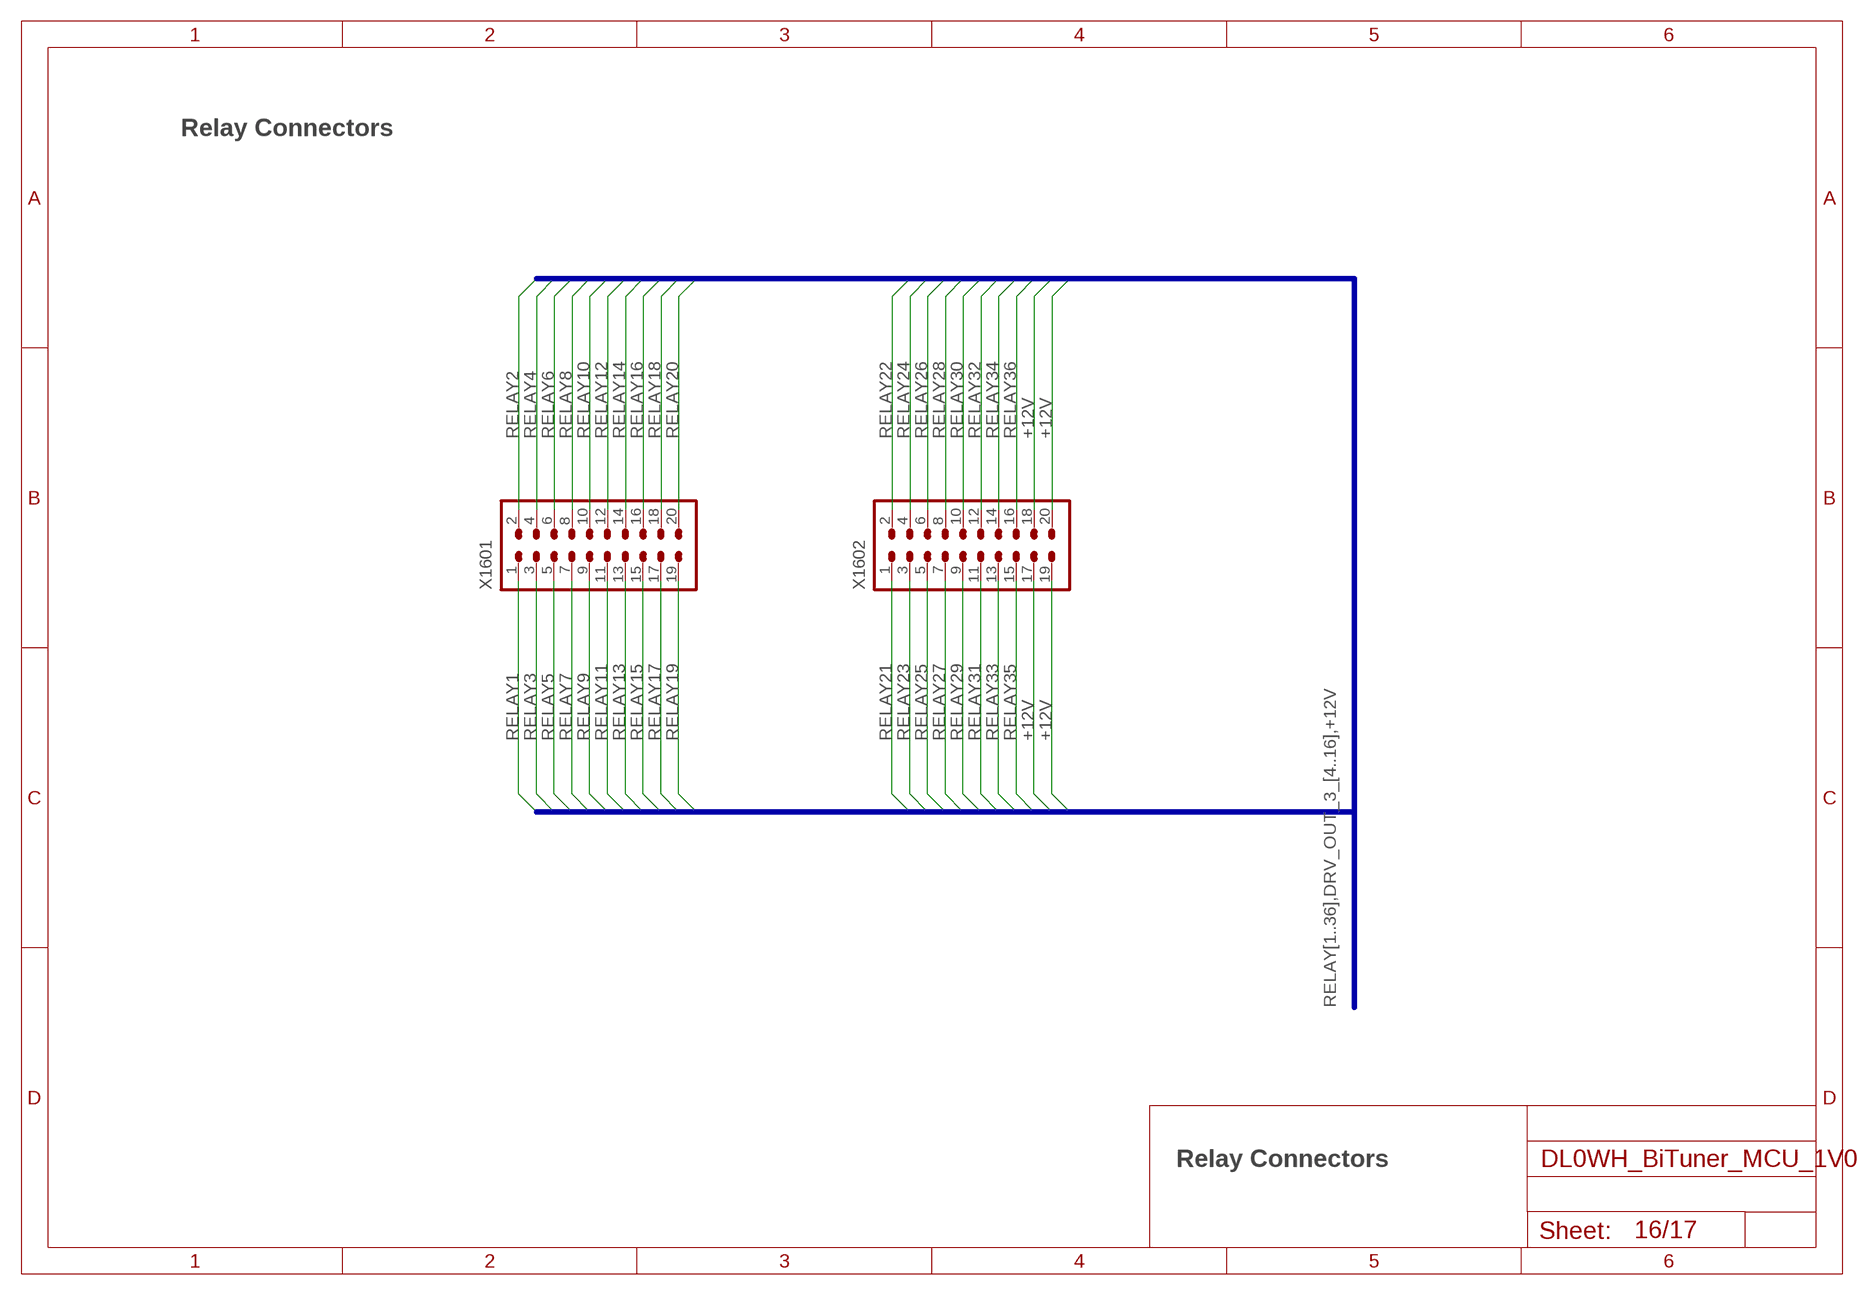
[diagram p15: schematic, sheet 16]
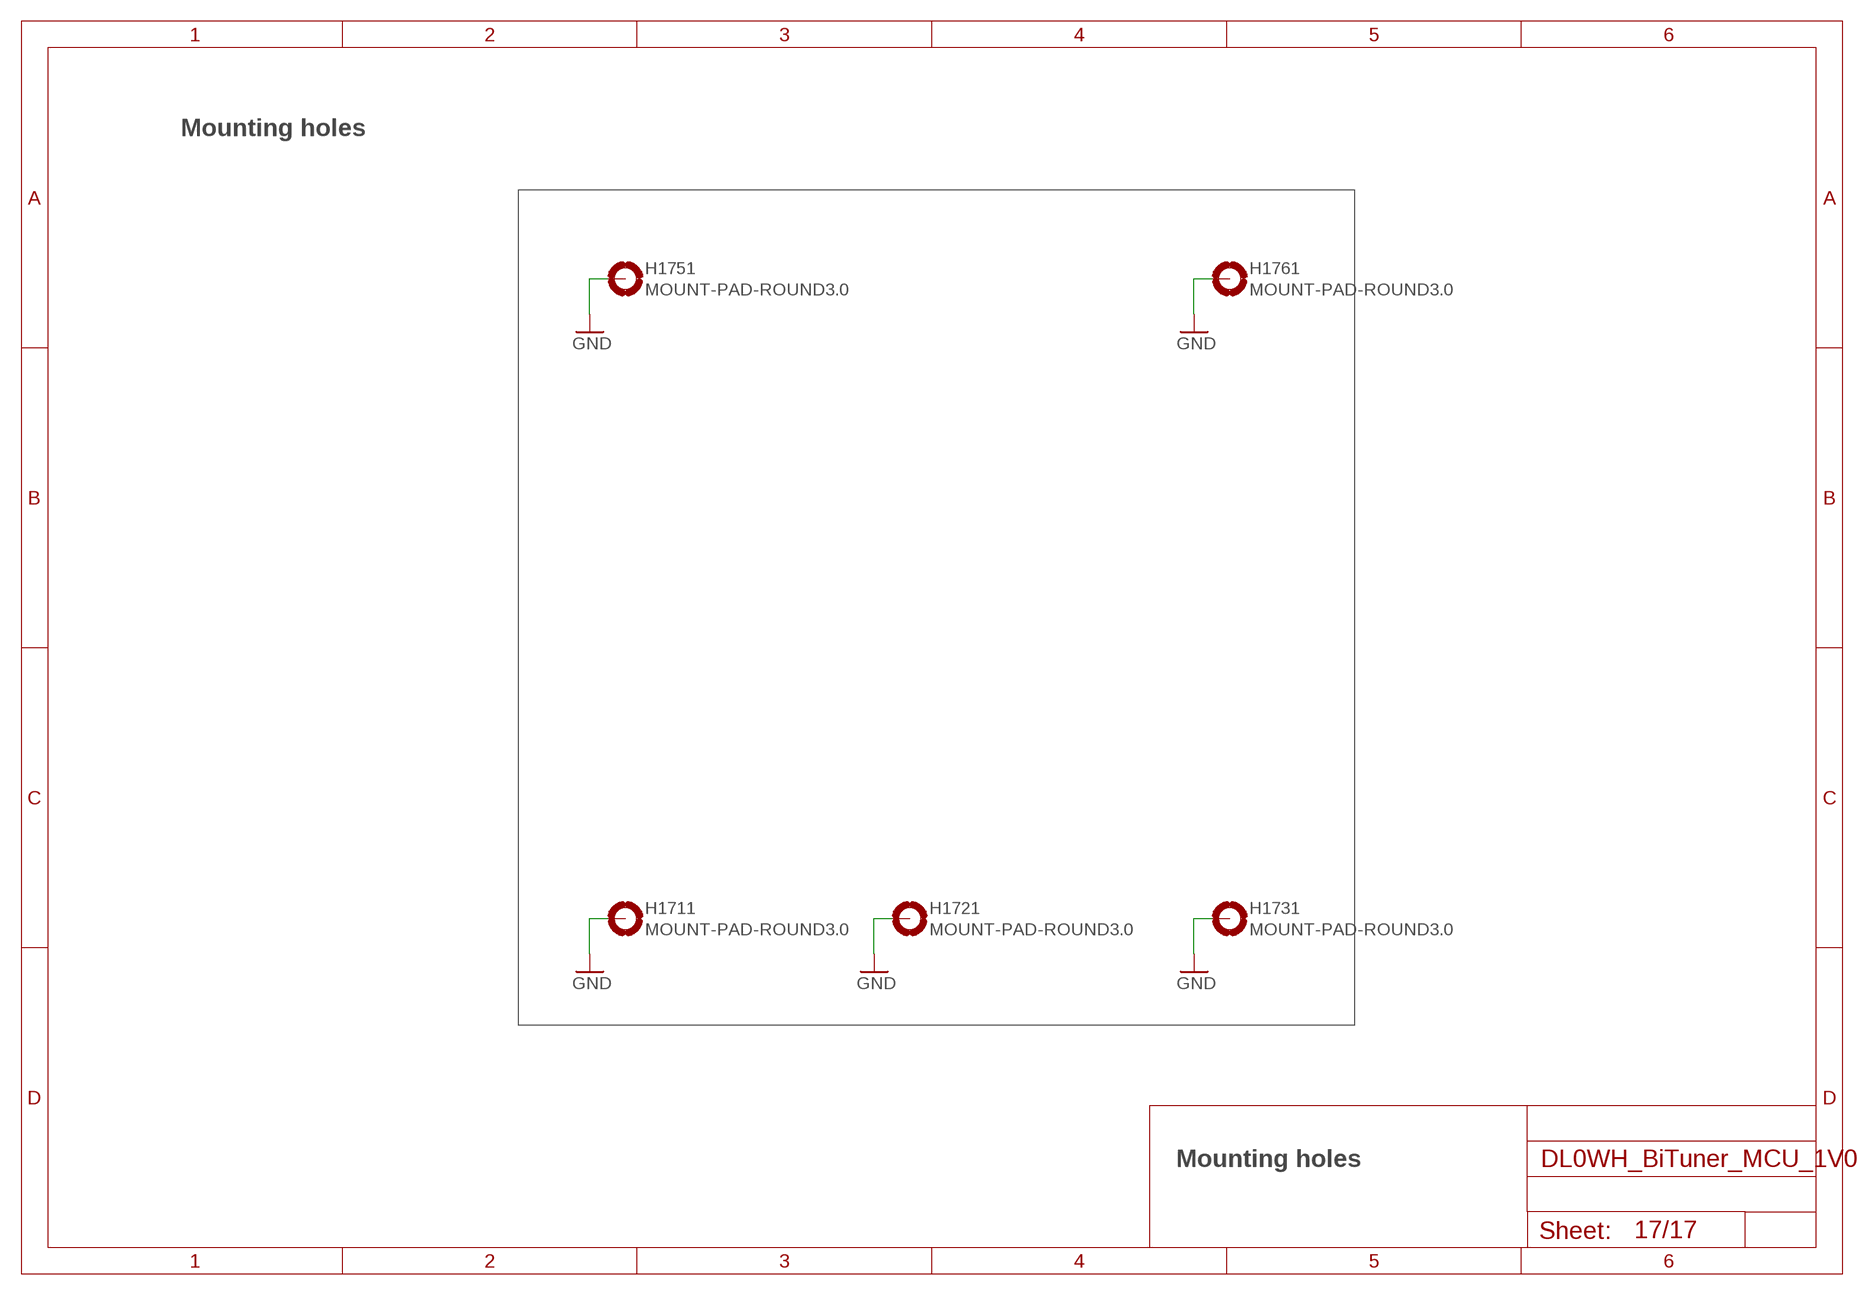
[diagram p16: schematic, sheet 17]

(export (version "E")
  (design (tool "Eeschema 10.0.6"))
  (components
    (comp (ref "C1301")
      (value "22uF")
      (footprint "eagle-import:C0603")
      (libsource (lib "eagle-import") (part "C-EUC0603"))
    )
    (comp (ref "C1311")
      (value "22uF")
      (footprint "eagle-import:C0603")
      (libsource (lib "eagle-import") (part "C-EUC0603"))
    )
    (comp (ref "L1311")
      (value "10uH")
      (footprint "eagle-import:L_4.50MM_X_3.20MM")
      (libsource (lib "eagle-import") (part "L-EU4.50X3.20MM"))
    )
    (comp (ref "R1301")
      (value "100kR")
      (footprint "eagle-import:R0402")
      (libsource (lib "eagle-import") (part "R-EU_R0402"))
    )
    (comp (ref "R1302")
      (value "220kR")
      (footprint "eagle-import:R0402")
      (libsource (lib "eagle-import") (part "R-EU_R0402"))
    )
    (comp (ref "R1321")
      (value "1MR")
      (footprint "eagle-import:R0402")
      (libsource (lib "eagle-import") (part "R-EU_R0402"))
    )
    (comp (ref "R1322")
      (value "1MR")
      (footprint "eagle-import:R0402")
      (libsource (lib "eagle-import") (part "R-EU_R0402"))
    )
    (comp (ref "U1301")
      (value "TPS62051")
      (footprint "eagle-import:S-PDSO-G10")
      (libsource (lib "eagle-import") (part "TPS62051"))
    )
    (comp (ref "C0901")
      (value "10nF")
      (footprint "eagle-import:C0402")
      (libsource (lib "eagle-import") (part "C-EUC0402"))
    )
    (comp (ref "C0911")
      (value "10nF")
      (footprint "eagle-import:C0402")
      (libsource (lib "eagle-import") (part "C-EUC0402"))
    )
    (comp (ref "C0921")
      (value "100nF")
      (footprint "eagle-import:C0402")
      (libsource (lib "eagle-import") (part "C-EUC0402"))
    )
    (comp (ref "C0951")
      (value "100nF")
      (footprint "eagle-import:C0402")
      (libsource (lib "eagle-import") (part "C-EUC0402"))
    )
    (comp (ref "D0901")
      (value "CRS08")
      (footprint "eagle-import:SOD80C")
      (libsource (lib "eagle-import") (part "CRS08"))
    )
    (comp (ref "D0911")
      (value "CRS08")
      (footprint "eagle-import:SOD80C")
      (libsource (lib "eagle-import") (part "CRS08"))
    )
    (comp (ref "D0951")
      (value "CMAD6001")
      (footprint "eagle-import:SOD923")
      (libsource (lib "eagle-import") (part "D_SOD923"))
    )
    (comp (ref "D0961")
      (value "CMAD6001")
      (footprint "eagle-import:SOD923")
      (libsource (lib "eagle-import") (part "D_SOD923"))
    )
    (comp (ref "L0901")
      (value "10uH")
      (footprint "eagle-import:L0603")
      (libsource (lib "eagle-import") (part "L-EUL0603"))
    )
    (comp (ref "L0911")
      (value "10uH")
      (footprint "eagle-import:L0603")
      (libsource (lib "eagle-import") (part "L-EUL0603"))
    )
    (comp (ref "R0901")
      (value "1kR")
      (footprint "eagle-import:R0402")
      (libsource (lib "eagle-import") (part "R-EU_R0402"))
    )
    (comp (ref "R0902")
      (value "15kR")
      (footprint "eagle-import:R0402")
      (libsource (lib "eagle-import") (part "R-EU_R0402"))
    )
    (comp (ref "R0903")
      (value "100kR")
      (footprint "eagle-import:R0402")
      (libsource (lib "eagle-import") (part "R-EU_R0402"))
    )
    (comp (ref "R0911")
      (value "1kR")
      (footprint "eagle-import:R0402")
      (libsource (lib "eagle-import") (part "R-EU_R0402"))
    )
    (comp (ref "R0912")
      (value "15kR")
      (footprint "eagle-import:R0402")
      (libsource (lib "eagle-import") (part "R-EU_R0402"))
    )
    (comp (ref "R0913")
      (value "100kR")
      (footprint "eagle-import:R0402")
      (libsource (lib "eagle-import") (part "R-EU_R0402"))
    )
    (comp (ref "R0921")
      (value "47R")
      (footprint "eagle-import:R0402")
      (libsource (lib "eagle-import") (part "R-EU_R0402"))
    )
    (comp (ref "R0922")
      (value "47R")
      (footprint "eagle-import:R0402")
      (libsource (lib "eagle-import") (part "R-EU_R0402"))
    )
    (comp (ref "R0951")
      (value "1MR")
      (footprint "eagle-import:R0402")
      (libsource (lib "eagle-import") (part "R-EU_R0402"))
    )
    (comp (ref "R0952")
      (value "47R")
      (footprint "eagle-import:R0402")
      (libsource (lib "eagle-import") (part "R-EU_R0402"))
    )
    (comp (ref "R0961")
      (value "10kR")
      (footprint "eagle-import:R0402")
      (libsource (lib "eagle-import") (part "R-EU_R0402"))
    )
    (comp (ref "U0921")
      (value "TS5A23166")
      (footprint "eagle-import:R-PDSO-G8")
      (libsource (lib "eagle-import") (part "TS5A23166"))
    )
    (comp (ref "U0951")
      (value "OPA354")
      (footprint "eagle-import:SOT-23-5")
      (fields (field (name "MPN") "OPA354AIDBVT"))
      (libsource (lib "eagle-import") (part "OPA354"))
    )
    (comp (ref "C1201")
      (value "10uF")
      (footprint "eagle-import:C0603")
      (libsource (lib "eagle-import") (part "C-EUC0603"))
    )
    (comp (ref "C1202")
      (value "10uF")
      (footprint "eagle-import:C0603")
      (libsource (lib "eagle-import") (part "C-EUC0603"))
    )
    (comp (ref "C1203")
      (value "10uF")
      (footprint "eagle-import:C0603")
      (libsource (lib "eagle-import") (part "C-EUC0603"))
    )
    (comp (ref "C1204")
      (value "10nF")
      (footprint "eagle-import:C0402")
      (libsource (lib "eagle-import") (part "C-EUC0402"))
    )
    (comp (ref "C1205")
      (value "3.3uF")
      (footprint "eagle-import:C0603")
      (libsource (lib "eagle-import") (part "C-EUC0603"))
    )
    (comp (ref "C1211")
      (value "0.47uF")
      (footprint "eagle-import:C0402")
      (libsource (lib "eagle-import") (part "C-EUC0402"))
    )
    (comp (ref "C1212")
      (value "100nF")
      (footprint "eagle-import:C0402")
      (libsource (lib "eagle-import") (part "C-EUC0402"))
    )
    (comp (ref "C1221")
      (value "22uF")
      (footprint "eagle-import:C0603")
      (libsource (lib "eagle-import") (part "C-EUC0603"))
    )
    (comp (ref "C1222")
      (value "22uF")
      (footprint "eagle-import:C0603")
      (libsource (lib "eagle-import") (part "C-EUC0603"))
    )
    (comp (ref "C1223")
      (value "22uF")
      (footprint "eagle-import:C0603")
      (libsource (lib "eagle-import") (part "C-EUC0603"))
    )
    (comp (ref "L1211")
      (value "2.2uH")
      (footprint "eagle-import:L_6.00MM_X_6.00MM")
      (libsource (lib "eagle-import") (part "L-EU6.00X6.00MM"))
    )
    (comp (ref "R1211")
      (value "3R")
      (footprint "eagle-import:R0402")
      (libsource (lib "eagle-import") (part "R-EU_R0402"))
    )
    (comp (ref "U1201")
      (value "LM53603-Q1")
      (footprint "eagle-import:HTSSOP16")
      (libsource (lib "eagle-import") (part "LM53603-Q1"))
    )
    (comp (ref "X1211")
      (value "WIRE-TO-BOARD_5MM08_1X02")
      (footprint "eagle-import:WIRE-TO-BOARD_5MM08_1X02")
      (libsource (lib "eagle-import") (part "WIRE-TO-BOARD_5MM08_1X02"))
    )
    (comp (ref "C1101")
      (value "1uF")
      (footprint "eagle-import:C0402")
      (libsource (lib "eagle-import") (part "C-EUC0402"))
    )
    (comp (ref "C1102")
      (value "1uF")
      (footprint "eagle-import:C0402")
      (libsource (lib "eagle-import") (part "C-EUC0402"))
    )
    (comp (ref "C1103")
      (value "1uF")
      (footprint "eagle-import:C0402")
      (libsource (lib "eagle-import") (part "C-EUC0402"))
    )
    (comp (ref "C1104")
      (value "1uF")
      (footprint "eagle-import:C0402")
      (libsource (lib "eagle-import") (part "C-EUC0402"))
    )
    (comp (ref "C1105")
      (value "1uF")
      (footprint "eagle-import:C0402")
      (libsource (lib "eagle-import") (part "C-EUC0402"))
    )
    (comp (ref "C1151")
      (value "10nF")
      (footprint "eagle-import:C0603")
      (libsource (lib "eagle-import") (part "C-EUC0603"))
    )
    (comp (ref "C1152")
      (value "10nF")
      (footprint "eagle-import:C0603")
      (libsource (lib "eagle-import") (part "C-EUC0603"))
    )
    (comp (ref "C1153")
      (value "10nF")
      (footprint "eagle-import:C0603")
      (libsource (lib "eagle-import") (part "C-EUC0603"))
    )
    (comp (ref "C1154")
      (value "10nF")
      (footprint "eagle-import:C0603")
      (libsource (lib "eagle-import") (part "C-EUC0603"))
    )
    (comp (ref "R1101")
      (value "47R")
      (footprint "eagle-import:R0402")
      (libsource (lib "eagle-import") (part "R-EU_R0402"))
    )
    (comp (ref "R1102")
      (value "47R")
      (footprint "eagle-import:R0402")
      (libsource (lib "eagle-import") (part "R-EU_R0402"))
    )
    (comp (ref "R1103")
      (value "47R")
      (footprint "eagle-import:R0402")
      (libsource (lib "eagle-import") (part "R-EU_R0402"))
    )
    (comp (ref "R1104")
      (value "47R")
      (footprint "eagle-import:R0402")
      (libsource (lib "eagle-import") (part "R-EU_R0402"))
    )
    (comp (ref "U1101")
      (value "MAX232_SOIC16")
      (footprint "eagle-import:SOIC16N")
      (fields (field (name "MF") "MAXIM") (field (name "MPN") "MAX232ECDR"))
      (libsource (lib "eagle-import") (part "MAX232_SOIC16"))
    )
    (comp (ref "X1151")
      (value "WIRE-TO-BOARD_5MM08_1X02")
      (footprint "eagle-import:WIRE-TO-BOARD_5MM08_1X02")
      (libsource (lib "eagle-import") (part "WIRE-TO-BOARD_5MM08_1X02"))
    )
    (comp (ref "X1152")
      (value "WIRE-TO-BOARD_5MM08_1X02")
      (footprint "eagle-import:WIRE-TO-BOARD_5MM08_1X02")
      (libsource (lib "eagle-import") (part "WIRE-TO-BOARD_5MM08_1X02"))
    )
    (comp (ref "X1153")
      (value "WIRE-TO-BOARD_5MM08_1X02")
      (footprint "eagle-import:WIRE-TO-BOARD_5MM08_1X02")
      (libsource (lib "eagle-import") (part "WIRE-TO-BOARD_5MM08_1X02"))
    )
    (comp (ref "C0601")
      (value "100nF")
      (footprint "eagle-import:C0402")
      (libsource (lib "eagle-import") (part "C-EUC0402"))
    )
    (comp (ref "C0602")
      (value "100nF")
      (footprint "eagle-import:C0402")
      (libsource (lib "eagle-import") (part "C-EUC0402"))
    )
    (comp (ref "C0603")
      (value "22uF")
      (footprint "eagle-import:C0603")
      (libsource (lib "eagle-import") (part "C-EUC0603"))
    )
    (comp (ref "R0611")
      (value "47R")
      (footprint "eagle-import:R0402")
      (libsource (lib "eagle-import") (part "R-EU_R0402"))
    )
    (comp (ref "R0621")
      (value "47R")
      (footprint "eagle-import:R0402")
      (libsource (lib "eagle-import") (part "R-EU_R0402"))
    )
    (comp (ref "R0622")
      (value "0R")
      (footprint "eagle-import:R0402")
      (libsource (lib "eagle-import") (part "R-EU_R0402"))
    )
    (comp (ref "R0623")
      (value "47R")
      (footprint "eagle-import:R0402")
      (libsource (lib "eagle-import") (part "R-EU_R0402"))
    )
    (comp (ref "R0624")
      (value "47R")
      (footprint "eagle-import:R0402")
      (libsource (lib "eagle-import") (part "R-EU_R0402"))
    )
    (comp (ref "R0625")
      (value "47R")
      (footprint "eagle-import:R0402")
      (libsource (lib "eagle-import") (part "R-EU_R0402"))
    )
    (comp (ref "R0626")
      (value "47R")
      (footprint "eagle-import:R0402")
      (libsource (lib "eagle-import") (part "R-EU_R0402"))
    )
    (comp (ref "U0601")
      (value "MC33996")
      (footprint "eagle-import:SOICW32")
      (libsource (lib "eagle-import") (part "MC33996"))
    )
    (comp (ref "C0213")
      (value "100nF")
      (footprint "eagle-import:C0402")
      (libsource (lib "eagle-import") (part "C-EUC0402"))
    )
    (comp (ref "R0221")
      (value "33kR")
      (footprint "eagle-import:R0402")
      (libsource (lib "eagle-import") (part "R-EU_R0402"))
    )
    (comp (ref "R0231")
      (value "220kR")
      (footprint "eagle-import:R0402")
      (libsource (lib "eagle-import") (part "R-EU_R0402"))
    )
    (comp (ref "R0232")
      (value "220kR")
      (footprint "eagle-import:R0402")
      (libsource (lib "eagle-import") (part "R-EU_R0402"))
    )
    (comp (ref "S0212")
      (value "KSR223GLFG")
      (footprint "eagle-import:KSR223G_SMD_1POL")
      (libsource (lib "eagle-import") (part "KSR223G_SMD_1POL"))
    )
    (comp (ref "X0201")
      (value "HEADER-2X5_1MM27CORTEX_10PIN_JTAG-SWD")
      (footprint "eagle-import:2X05_SHROUDED_1MM27")
      (libsource (lib "eagle-import") (part "HEADER-2X5_1MM27CORTEX_10PIN_JTAG-SWD"))
    )
    (comp (ref "X0222")
      (value "HEADER-1X2")
      (footprint "eagle-import:1X02")
      (libsource (lib "eagle-import") (part "HEADER-1X2"))
    )
    (comp (ref "U0101")
      (value "STM32L476RXT_64PIN_LDO")
      (footprint "eagle-import:LQFP64")
      (libsource (lib "eagle-import") (part "STM32L476RXT_64PIN_LDO"))
    )
    (comp (ref "C1403")
      (value "1nF")
      (footprint "eagle-import:C0402")
      (libsource (lib "eagle-import") (part "C-EUC0402"))
    )
    (comp (ref "PF1411")
      (value "1.1A/2.2A")
      (footprint "eagle-import:M1206")
      (libsource (lib "eagle-import") (part "rcl_R-EU_M1206"))
    )
    (comp (ref "R1402")
      (value "330kR")
      (footprint "eagle-import:R0402")
      (libsource (lib "eagle-import") (part "R-EU_R0402"))
    )
    (comp (ref "X1401")
      (value "MOLEX 105017-0001")
      (footprint "eagle-import:USB-B-MICRO-SMD_MOLEX-105017-0001")
      (libsource (lib "eagle-import") (part "USB_MICRO-B_MOLEX"))
    )
    (comp (ref "C0054")
      (value "10nF")
      (footprint "eagle-import:C0603")
      (libsource (lib "eagle-import") (part "C-EUC0603"))
    )
    (comp (ref "C1001")
      (value "1uF")
      (footprint "eagle-import:C0402")
      (libsource (lib "eagle-import") (part "C-EUC0402"))
    )
    (comp (ref "C1002")
      (value "1uF")
      (footprint "eagle-import:C0402")
      (libsource (lib "eagle-import") (part "C-EUC0402"))
    )
    (comp (ref "C1003")
      (value "1uF")
      (footprint "eagle-import:C0402")
      (libsource (lib "eagle-import") (part "C-EUC0402"))
    )
    (comp (ref "C1004")
      (value "1uF")
      (footprint "eagle-import:C0402")
      (libsource (lib "eagle-import") (part "C-EUC0402"))
    )
    (comp (ref "C1005")
      (value "1uF")
      (footprint "eagle-import:C0402")
      (libsource (lib "eagle-import") (part "C-EUC0402"))
    )
    (comp (ref "C1051")
      (value "10nF")
      (footprint "eagle-import:C0603")
      (libsource (lib "eagle-import") (part "C-EUC0603"))
    )
    (comp (ref "C1052")
      (value "10nF")
      (footprint "eagle-import:C0603")
      (libsource (lib "eagle-import") (part "C-EUC0603"))
    )
    (comp (ref "C1053")
      (value "10nF")
      (footprint "eagle-import:C0603")
      (libsource (lib "eagle-import") (part "C-EUC0603"))
    )
    (comp (ref "R1001")
      (value "47R")
      (footprint "eagle-import:R0402")
      (libsource (lib "eagle-import") (part "R-EU_R0402"))
    )
    (comp (ref "R1002")
      (value "47R")
      (footprint "eagle-import:R0402")
      (libsource (lib "eagle-import") (part "R-EU_R0402"))
    )
    (comp (ref "R1003")
      (value "47R")
      (footprint "eagle-import:R0402")
      (libsource (lib "eagle-import") (part "R-EU_R0402"))
    )
    (comp (ref "R1004")
      (value "47R")
      (footprint "eagle-import:R0402")
      (libsource (lib "eagle-import") (part "R-EU_R0402"))
    )
    (comp (ref "U1001")
      (value "MAX232_SOIC16")
      (footprint "eagle-import:SOIC16N")
      (fields (field (name "MF") "MAXIM") (field (name "MPN") "MAX232ECDR"))
      (libsource (lib "eagle-import") (part "MAX232_SOIC16"))
    )
    (comp (ref "X1051")
      (value "WIRE-TO-BOARD_5MM08_1X02")
      (footprint "eagle-import:WIRE-TO-BOARD_5MM08_1X02")
      (libsource (lib "eagle-import") (part "WIRE-TO-BOARD_5MM08_1X02"))
    )
    (comp (ref "X1052")
      (value "WIRE-TO-BOARD_5MM08_1X02")
      (footprint "eagle-import:WIRE-TO-BOARD_5MM08_1X02")
      (libsource (lib "eagle-import") (part "WIRE-TO-BOARD_5MM08_1X02"))
    )
    (comp (ref "X1053")
      (value "WIRE-TO-BOARD_5MM08_1X02")
      (footprint "eagle-import:WIRE-TO-BOARD_5MM08_1X02")
      (libsource (lib "eagle-import") (part "WIRE-TO-BOARD_5MM08_1X02"))
    )
    (comp (ref "C0311")
      (value "18pF")
      (footprint "eagle-import:C0402")
      (libsource (lib "eagle-import") (part "C-EUC0402"))
    )
    (comp (ref "C0331")
      (value "JR200")
      (footprint "eagle-import:3MM2_X_2MM5")
      (libsource (lib "eagle-import") (part "C-TRIMM3MM2_2MM5"))
    )
    (comp (ref "C0332")
      (value "8.2pF")
      (footprint "eagle-import:C0402")
      (libsource (lib "eagle-import") (part "C-EUC0402"))
    )
    (comp (ref "Q0321")
      (value "ABS07-32.768KHZ")
      (footprint "eagle-import:ABS07")
      (fields (field (name "MANUFACTURER") "ABS07-32.768KHZ-1-T"))
      (libsource (lib "eagle-import") (part "ABS07-32.768KHZ"))
    )
    (comp (ref "R0511")
      (value "1kR")
      (footprint "eagle-import:R0402")
      (libsource (lib "eagle-import") (part "R-EU_R0402"))
    )
    (comp (ref "R0512")
      (value "1kR")
      (footprint "eagle-import:R0402")
      (libsource (lib "eagle-import") (part "R-EU_R0402"))
    )
    (comp (ref "X0601")
      (value "HEADER-2X2")
      (footprint "eagle-import:2X02")
      (libsource (lib "eagle-import") (part "HEADER-2X2"))
    )
    (comp (ref "H1711")
      (value "MOUNT-PAD-ROUND3.0")
      (footprint "eagle-import:3,0-PAD")
      (libsource (lib "eagle-import") (part "MOUNT-PAD-ROUND3.0"))
    )
    (comp (ref "H1721")
      (value "MOUNT-PAD-ROUND3.0")
      (footprint "eagle-import:3,0-PAD")
      (libsource (lib "eagle-import") (part "MOUNT-PAD-ROUND3.0"))
    )
    (comp (ref "H1731")
      (value "MOUNT-PAD-ROUND3.0")
      (footprint "eagle-import:3,0-PAD")
      (libsource (lib "eagle-import") (part "MOUNT-PAD-ROUND3.0"))
    )
    (comp (ref "H1751")
      (value "MOUNT-PAD-ROUND3.0")
      (footprint "eagle-import:3,0-PAD")
      (libsource (lib "eagle-import") (part "MOUNT-PAD-ROUND3.0"))
    )
    (comp (ref "H1761")
      (value "MOUNT-PAD-ROUND3.0")
      (footprint "eagle-import:3,0-PAD")
      (libsource (lib "eagle-import") (part "MOUNT-PAD-ROUND3.0"))
    )
    (comp (ref "C0401")
      (value "100nF")
      (footprint "eagle-import:C0402")
      (libsource (lib "eagle-import") (part "C-EUC0402"))
    )
    (comp (ref "C0402")
      (value "100nF")
      (footprint "eagle-import:C0402")
      (libsource (lib "eagle-import") (part "C-EUC0402"))
    )
    (comp (ref "C0403")
      (value "100nF")
      (footprint "eagle-import:C0402")
      (libsource (lib "eagle-import") (part "C-EUC0402"))
    )
    (comp (ref "C0410")
      (value "4.7uF")
      (footprint "eagle-import:C0603")
      (libsource (lib "eagle-import") (part "C-EUC0603"))
    )
    (comp (ref "C0412")
      (value "10nF")
      (footprint "eagle-import:C0402")
      (libsource (lib "eagle-import") (part "C-EUC0402"))
    )
    (comp (ref "C0413")
      (value "1uF")
      (footprint "eagle-import:C0402")
      (libsource (lib "eagle-import") (part "C-EUC0402"))
    )
    (comp (ref "C0451")
      (value "47uF")
      (footprint "eagle-import:C0805")
      (libsource (lib "eagle-import") (part "C-EUC0805"))
    )
    (comp (ref "L0411")
      (value "10uH")
      (footprint "eagle-import:L0603")
      (libsource (lib "eagle-import") (part "L-EUL0603"))
    )
    (comp (ref "R0441")
      (value "0R")
      (footprint "eagle-import:R0402")
      (libsource (lib "eagle-import") (part "R-EU_R0402"))
    )
    (comp (ref "SJ0401")
      (value "SJ")
      (footprint "eagle-import:SJ")
      (libsource (lib "eagle-import") (part "SJ"))
    )
    (comp (ref "TP_VBAT")
      (value "PTR1B1,27")
      (footprint "eagle-import:B1,27")
      (libsource (lib "eagle-import") (part "PTR1B1,27"))
    )
    (comp (ref "X1501")
      (value "SMA_SMT_AMPHENOL-901-143")
      (footprint "eagle-import:SMA_SMT_AMPHENOL_901-143")
      (fields (field (name "MPN") "901-143"))
      (libsource (lib "eagle-import") (part "SMA_SMT_AMPHENOL-901-143"))
    )
    (comp (ref "X1511")
      (value "SAMTEC SMA-J-P-H-RA-TH1")
      (footprint "eagle-import:SMA_SMT_AMPHENOL_901-143")
      (fields (field (name "MPN") "901-143"))
      (libsource (lib "eagle-import") (part "SMA_SMT_AMPHENOL-901-143"))
    )
    (comp (ref "X1601")
      (value "2X10_2MM56_SOCKET")
      (footprint "eagle-import:2X10")
      (libsource (lib "eagle-import") (part "2X10_2MM56_SOCKET"))
    )
    (comp (ref "X1602")
      (value "2X10_2MM56_SOCKET")
      (footprint "eagle-import:2X10")
      (libsource (lib "eagle-import") (part "2X10_2MM56_SOCKET"))
    )
    (comp (ref "C0801")
      (value "100nF")
      (footprint "eagle-import:C0402")
      (libsource (lib "eagle-import") (part "C-EUC0402"))
    )
    (comp (ref "C0802")
      (value "100nF")
      (footprint "eagle-import:C0402")
      (libsource (lib "eagle-import") (part "C-EUC0402"))
    )
    (comp (ref "C0803")
      (value "22uF")
      (footprint "eagle-import:C0603")
      (libsource (lib "eagle-import") (part "C-EUC0603"))
    )
    (comp (ref "R0811")
      (value "47R")
      (footprint "eagle-import:R0402")
      (libsource (lib "eagle-import") (part "R-EU_R0402"))
    )
    (comp (ref "R0824")
      (value "47R")
      (footprint "eagle-import:R0402")
      (libsource (lib "eagle-import") (part "R-EU_R0402"))
    )
    (comp (ref "U0801")
      (value "MC33996")
      (footprint "eagle-import:SOICW32")
      (libsource (lib "eagle-import") (part "MC33996"))
    )
    (comp (ref "C0701")
      (value "100nF")
      (footprint "eagle-import:C0402")
      (libsource (lib "eagle-import") (part "C-EUC0402"))
    )
    (comp (ref "C0702")
      (value "100nF")
      (footprint "eagle-import:C0402")
      (libsource (lib "eagle-import") (part "C-EUC0402"))
    )
    (comp (ref "C0703")
      (value "22uF")
      (footprint "eagle-import:C0603")
      (libsource (lib "eagle-import") (part "C-EUC0603"))
    )
    (comp (ref "R0711")
      (value "47R")
      (footprint "eagle-import:R0402")
      (libsource (lib "eagle-import") (part "R-EU_R0402"))
    )
    (comp (ref "R0724")
      (value "47R")
      (footprint "eagle-import:R0402")
      (libsource (lib "eagle-import") (part "R-EU_R0402"))
    )
    (comp (ref "U0701")
      (value "MC33996")
      (footprint "eagle-import:SOICW32")
      (libsource (lib "eagle-import") (part "MC33996"))
    )
  )
  (nets
    (net (code "26") (name "+3V3") (class "Default")
      (node (ref "C0601") (pin "2") (pinfunction "2_2") (pintype "passive"))
      (node (ref "C0701") (pin "2") (pinfunction "2_2") (pintype "passive"))
      (node (ref "C0801") (pin "2") (pinfunction "2_2") (pintype "passive"))
      (node (ref "C0921") (pin "1") (pinfunction "1_1") (pintype "passive"))
      (node (ref "C0951") (pin "1") (pinfunction "1_1") (pintype "passive"))
      (node (ref "C1311") (pin "1") (pinfunction "1_1") (pintype "passive"))
      (node (ref "D0901") (pin "C") (pinfunction "C_C") (pintype "passive"))
      (node (ref "D0911") (pin "C") (pinfunction "C_C") (pintype "passive"))
      (node (ref "L1311") (pin "1") (pinfunction "1_1") (pintype "passive"))
      (node (ref "L1311") (pin "3") (pinfunction "1_3") (pintype "passive"))
      (node (ref "R0231") (pin "2") (pinfunction "2_2") (pintype "passive"))
      (node (ref "R0511") (pin "2") (pinfunction "2_2") (pintype "passive"))
      (node (ref "R0512") (pin "2") (pinfunction "2_2") (pintype "passive"))
      (node (ref "R0903") (pin "2") (pinfunction "2_2") (pintype "passive"))
      (node (ref "R0913") (pin "2") (pinfunction "2_2") (pintype "passive"))
      (node (ref "R0961") (pin "1") (pinfunction "1_1") (pintype "passive"))
      (node (ref "R1321") (pin "2") (pinfunction "2_2") (pintype "passive"))
      (node (ref "R1322") (pin "2") (pinfunction "2_2") (pintype "passive"))
      (node (ref "SJ0401") (pin "1") (pinfunction "1_1") (pintype "passive"))
      (node (ref "U0601") (pin "3") (pinfunction "SOPWR_3") (pintype "power_in"))
      (node (ref "U0701") (pin "3") (pinfunction "SOPWR_3") (pintype "power_in"))
      (node (ref "U0801") (pin "3") (pinfunction "SOPWR_3") (pintype "power_in"))
      (node (ref "U0921") (pin "8") (pinfunction "8_8") (pintype "power_in"))
      (node (ref "U0951") (pin "5") (pinfunction "V+_5") (pintype "power_in"))
      (node (ref "U1301") (pin "5") (pinfunction "FB_5") (pintype "passive"))
      (node (ref "X0201") (pin "1") (pinfunction "1_1") (pintype "passive"))
      (node (ref "X0222") (pin "1") (pinfunction "1_1") (pintype "passive"))
    )
    (net (code "27") (name "+5V") (class "Default")
      (node (ref "C1001") (pin "1") (pinfunction "1_1") (pintype "passive"))
      (node (ref "C1101") (pin "1") (pinfunction "1_1") (pintype "passive"))
      (node (ref "C1221") (pin "1") (pinfunction "1_1") (pintype "passive"))
      (node (ref "C1222") (pin "1") (pinfunction "1_1") (pintype "passive"))
      (node (ref "C1223") (pin "1") (pinfunction "1_1") (pintype "passive"))
      (node (ref "C1301") (pin "1") (pinfunction "1_1") (pintype "passive"))
      (node (ref "L1211") (pin "1") (pinfunction "1_1") (pintype "passive"))
      (node (ref "R1211") (pin "2") (pinfunction "2_2") (pintype "passive"))
      (node (ref "R1302") (pin "2") (pinfunction "2_2") (pintype "passive"))
      (node (ref "U1001") (pin "16") (pinfunction "VCC_16") (pintype "power_in"))
      (node (ref "U1101") (pin "16") (pinfunction "VCC_16") (pintype "power_in"))
      (node (ref "U1201") (pin "9") (pinfunction "FB_9") (pintype "passive"))
      (node (ref "U1301") (pin "1") (pinfunction "VIN_1") (pintype "power_in"))
      (node (ref "U1301") (pin "8") (pinfunction "EN_8") (pintype "input"))
    )
    (net (code "28") (name "+12V") (class "Default")
      (node (ref "C0602") (pin "1") (pinfunction "1_1") (pintype "passive"))
      (node (ref "C0603") (pin "1") (pinfunction "1_1") (pintype "passive"))
      (node (ref "C0702") (pin "1") (pinfunction "1_1") (pintype "passive"))
      (node (ref "C0703") (pin "1") (pinfunction "1_1") (pintype "passive"))
      (node (ref "C0802") (pin "1") (pinfunction "1_1") (pintype "passive"))
      (node (ref "C0803") (pin "1") (pinfunction "1_1") (pintype "passive"))
      (node (ref "C1201") (pin "1") (pinfunction "1_1") (pintype "passive"))
      (node (ref "C1202") (pin "1") (pinfunction "1_1") (pintype "passive"))
      (node (ref "C1203") (pin "1") (pinfunction "1_1") (pintype "passive"))
      (node (ref "C1204") (pin "1") (pinfunction "1_1") (pintype "passive"))
      (node (ref "U0601") (pin "6") (pinfunction "VPWR_6") (pintype "power_in"))
      (node (ref "U0701") (pin "6") (pinfunction "VPWR_6") (pintype "power_in"))
      (node (ref "U0801") (pin "6") (pinfunction "VPWR_6") (pintype "power_in"))
      (node (ref "U1201") (pin "11") (pinfunction "EN_11") (pintype "input"))
      (node (ref "U1201") (pin "12") (pinfunction "VIN_12") (pintype "power_in"))
      (node (ref "U1201") (pin "13") (pinfunction "VIN_13") (pintype "power_in"))
      (node (ref "X1211") (pin "1") (pinfunction "1_1") (pintype "passive"))
      (node (ref "X1602") (pin "17") (pinfunction "17_17") (pintype "passive"))
      (node (ref "X1602") (pin "18") (pinfunction "18_18") (pintype "passive"))
      (node (ref "X1602") (pin "19") (pinfunction "19_19") (pintype "passive"))
      (node (ref "X1602") (pin "20") (pinfunction "20_20") (pintype "passive"))
    )
    (net (code "40") (name "CAT_DTE_CTS") (class "Default")
      (node (ref "C1153") (pin "1") (pinfunction "1_1") (pintype "passive"))
      (node (ref "U1101") (pin "7") (pinfunction "T2OUT_7") (pintype "output"))
      (node (ref "X1153") (pin "1") (pinfunction "1_1") (pintype "passive"))
    )
    (net (code "41") (name "CAT_DTE_RTR") (class "Default")
      (node (ref "C1154") (pin "1") (pinfunction "1_1") (pintype "passive"))
      (node (ref "U1101") (pin "8") (pinfunction "R2IN_8") (pintype "input"))
      (node (ref "X1153") (pin "2") (pinfunction "2_2") (pintype "passive"))
    )
    (net (code "42") (name "CAT_DTE_RXD") (class "Default")
      (node (ref "C1151") (pin "1") (pinfunction "1_1") (pintype "passive"))
      (node (ref "U1101") (pin "14") (pinfunction "T1OUT_14") (pintype "output"))
      (node (ref "X1151") (pin "1") (pinfunction "1_1") (pintype "passive"))
    )
    (net (code "43") (name "CAT_DTE_TXD") (class "Default")
      (node (ref "C1152") (pin "1") (pinfunction "1_1") (pintype "passive"))
      (node (ref "U1101") (pin "13") (pinfunction "R1IN_13") (pintype "input"))
      (node (ref "X1151") (pin "2") (pinfunction "2_2") (pintype "passive"))
    )
    (net (code "44") (name "CAT_MX_C1P") (class "Default")
      (node (ref "C1102") (pin "1") (pinfunction "1_1") (pintype "passive"))
      (node (ref "U1101") (pin "1") (pinfunction "C1+_1") (pintype "bidirectional"))
    )
    (net (code "45") (name "CAT_MX_C2P") (class "Default")
      (node (ref "C1103") (pin "1") (pinfunction "1_1") (pintype "passive"))
      (node (ref "U1101") (pin "4") (pinfunction "C2+_4") (pintype "bidirectional"))
    )
    (net (code "46") (name "CAT_MX_VM") (class "Default")
      (node (ref "C1105") (pin "1") (pinfunction "1_1") (pintype "passive"))
      (node (ref "U1101") (pin "6") (pinfunction "V-_6") (pintype "bidirectional"))
    )
    (net (code "47") (name "CAT_MX_VP") (class "Default")
      (node (ref "C1104") (pin "1") (pinfunction "1_1") (pintype "passive"))
      (node (ref "U1101") (pin "2") (pinfunction "V+_2") (pintype "bidirectional"))
    )
    (net (code "48") (name "DRV_OUT_3_4") (class "Default")
      (node (ref "U0801") (pin "12") (pinfunction "OUT4_12") (pintype "passive"))
    )
    (net (code "49") (name "DRV_OUT_3_5") (class "Default")
      (node (ref "U0801") (pin "13") (pinfunction "OUT5_13") (pintype "passive"))
    )
    (net (code "50") (name "DRV_OUT_3_6") (class "Default")
      (node (ref "U0801") (pin "15") (pinfunction "OUT6_15") (pintype "passive"))
    )
    (net (code "51") (name "DRV_OUT_3_7") (class "Default")
      (node (ref "U0801") (pin "16") (pinfunction "OUT7_16") (pintype "passive"))
    )
    (net (code "52") (name "DRV_OUT_3_8") (class "Default")
      (node (ref "U0801") (pin "17") (pinfunction "OUT8_17") (pintype "passive"))
    )
    (net (code "53") (name "DRV_OUT_3_9") (class "Default")
      (node (ref "U0801") (pin "18") (pinfunction "OUT9_18") (pintype "passive"))
    )
    (net (code "54") (name "DRV_OUT_3_10") (class "Default")
      (node (ref "U0801") (pin "20") (pinfunction "OUT10_20") (pintype "passive"))
    )
    (net (code "55") (name "DRV_OUT_3_11") (class "Default")
      (node (ref "U0801") (pin "21") (pinfunction "OUT11_21") (pintype "passive"))
    )
    (net (code "56") (name "DRV_OUT_3_12") (class "Default")
      (node (ref "U0801") (pin "28") (pinfunction "OUT12_28") (pintype "passive"))
    )
    (net (code "57") (name "DRV_OUT_3_13") (class "Default")
      (node (ref "U0801") (pin "29") (pinfunction "OUT13_29") (pintype "passive"))
    )
    (net (code "58") (name "DRV_OUT_3_14") (class "Default")
      (node (ref "U0801") (pin "31") (pinfunction "OUT14_31") (pintype "passive"))
    )
    (net (code "59") (name "DRV_OUT_3_15") (class "Default")
      (node (ref "U0801") (pin "32") (pinfunction "OUT15_32") (pintype "passive"))
    )
    (net (code "60") (name "GND") (class "Default")
      (node (ref "C0054") (pin "2") (pinfunction "2_2") (pintype "passive"))
      (node (ref "C0213") (pin "2") (pinfunction "2_2") (pintype "passive"))
      (node (ref "C0311") (pin "2") (pinfunction "2_2") (pintype "passive"))
      (node (ref "C0331") (pin "+") (pinfunction "A_+") (pintype "passive"))
      (node (ref "C0332") (pin "2") (pinfunction "2_2") (pintype "passive"))
      (node (ref "C0401") (pin "2") (pinfunction "2_2") (pintype "passive"))
      (node (ref "C0402") (pin "2") (pinfunction "2_2") (pintype "passive"))
      (node (ref "C0403") (pin "2") (pinfunction "2_2") (pintype "passive"))
      (node (ref "C0410") (pin "2") (pinfunction "2_2") (pintype "passive"))
      (node (ref "C0412") (pin "2") (pinfunction "2_2") (pintype "passive"))
      (node (ref "C0413") (pin "2") (pinfunction "2_2") (pintype "passive"))
      (node (ref "C0451") (pin "2") (pinfunction "2_2") (pintype "passive"))
      (node (ref "C0601") (pin "1") (pinfunction "1_1") (pintype "passive"))
      (node (ref "C0602") (pin "2") (pinfunction "2_2") (pintype "passive"))
      (node (ref "C0603") (pin "2") (pinfunction "2_2") (pintype "passive"))
      (node (ref "C0701") (pin "1") (pinfunction "1_1") (pintype "passive"))
      (node (ref "C0702") (pin "2") (pinfunction "2_2") (pintype "passive"))
      (node (ref "C0703") (pin "2") (pinfunction "2_2") (pintype "passive"))
      (node (ref "C0801") (pin "1") (pinfunction "1_1") (pintype "passive"))
      (node (ref "C0802") (pin "2") (pinfunction "2_2") (pintype "passive"))
      (node (ref "C0803") (pin "2") (pinfunction "2_2") (pintype "passive"))
      (node (ref "C0901") (pin "2") (pinfunction "2_2") (pintype "passive"))
      (node (ref "C0911") (pin "2") (pinfunction "2_2") (pintype "passive"))
      (node (ref "C0921") (pin "2") (pinfunction "2_2") (pintype "passive"))
      (node (ref "C0951") (pin "2") (pinfunction "2_2") (pintype "passive"))
      (node (ref "C1001") (pin "2") (pinfunction "2_2") (pintype "passive"))
      (node (ref "C1004") (pin "2") (pinfunction "2_2") (pintype "passive"))
      (node (ref "C1005") (pin "2") (pinfunction "2_2") (pintype "passive"))
      (node (ref "C1051") (pin "2") (pinfunction "2_2") (pintype "passive"))
      (node (ref "C1052") (pin "2") (pinfunction "2_2") (pintype "passive"))
      (node (ref "C1053") (pin "2") (pinfunction "2_2") (pintype "passive"))
      (node (ref "C1101") (pin "2") (pinfunction "2_2") (pintype "passive"))
      (node (ref "C1104") (pin "2") (pinfunction "2_2") (pintype "passive"))
      (node (ref "C1105") (pin "2") (pinfunction "2_2") (pintype "passive"))
      (node (ref "C1151") (pin "2") (pinfunction "2_2") (pintype "passive"))
      (node (ref "C1152") (pin "2") (pinfunction "2_2") (pintype "passive"))
      (node (ref "C1153") (pin "2") (pinfunction "2_2") (pintype "passive"))
      (node (ref "C1154") (pin "2") (pinfunction "2_2") (pintype "passive"))
      (node (ref "C1201") (pin "2") (pinfunction "2_2") (pintype "passive"))
      (node (ref "C1202") (pin "2") (pinfunction "2_2") (pintype "passive"))
      (node (ref "C1203") (pin "2") (pinfunction "2_2") (pintype "passive"))
      (node (ref "C1204") (pin "2") (pinfunction "2_2") (pintype "passive"))
      (node (ref "C1205") (pin "1") (pinfunction "1_1") (pintype "passive"))
      (node (ref "C1212") (pin "2") (pinfunction "2_2") (pintype "passive"))
      (node (ref "C1221") (pin "2") (pinfunction "2_2") (pintype "passive"))
      (node (ref "C1222") (pin "2") (pinfunction "2_2") (pintype "passive"))
      (node (ref "C1223") (pin "2") (pinfunction "2_2") (pintype "passive"))
      (node (ref "C1301") (pin "2") (pinfunction "2_2") (pintype "passive"))
      (node (ref "C1311") (pin "2") (pinfunction "2_2") (pintype "passive"))
      (node (ref "C1403") (pin "1") (pinfunction "1_1") (pintype "passive"))
      (node (ref "D0961") (pin "C") (pinfunction "C_C") (pintype "passive"))
      (node (ref "H1711") (pin "B3,0") (pinfunction "MOUNT_B3,0") (pintype "passive"))
      (node (ref "H1721") (pin "B3,0") (pinfunction "MOUNT_B3,0") (pintype "passive"))
      (node (ref "H1731") (pin "B3,0") (pinfunction "MOUNT_B3,0") (pintype "passive"))
      (node (ref "H1751") (pin "B3,0") (pinfunction "MOUNT_B3,0") (pintype "passive"))
      (node (ref "H1761") (pin "B3,0") (pinfunction "MOUNT_B3,0") (pintype "passive"))
      (node (ref "R0221") (pin "1") (pinfunction "1_1") (pintype "passive"))
      (node (ref "R0232") (pin "1") (pinfunction "1_1") (pintype "passive"))
      (node (ref "R0441") (pin "1") (pinfunction "1_1") (pintype "passive"))
      (node (ref "R0901") (pin "1") (pinfunction "1_1") (pintype "passive"))
      (node (ref "R0911") (pin "1") (pinfunction "1_1") (pintype "passive"))
      (node (ref "R0951") (pin "1") (pinfunction "1_1") (pintype "passive"))
      (node (ref "R1301") (pin "1") (pinfunction "1_1") (pintype "passive"))
      (node (ref "R1402") (pin "1") (pinfunction "1_1") (pintype "passive"))
      (node (ref "S0212") (pin "1") (pinfunction "P_1") (pintype "passive"))
      (node (ref "U0101") (pin "18") (pinfunction "VSS_18") (pintype "passive"))
      (node (ref "U0101") (pin "31") (pinfunction "VSS_31") (pintype "passive"))
      (node (ref "U0101") (pin "47") (pinfunction "VSS_47") (pintype "passive"))
      (node (ref "U0101") (pin "63") (pinfunction "VSS_63") (pintype "passive"))
      (node (ref "U0601") (pin "10") (pinfunction "GND_MC_10") (pintype "passive"))
      (node (ref "U0601") (pin "23") (pinfunction "GND_MC_23") (pintype "passive"))
      (node (ref "U0601") (pin "24") (pinfunction "GND_MC_24") (pintype "passive"))
      (node (ref "U0601") (pin "25") (pinfunction "GND_MC_25") (pintype "passive"))
      (node (ref "U0601") (pin "26") (pinfunction "GND_MC_26") (pintype "passive"))
      (node (ref "U0601") (pin "33") (pinfunction "EP_33") (pintype "passive"))
      (node (ref "U0601") (pin "7") (pinfunction "GND_MC_7") (pintype "passive"))
      (node (ref "U0601") (pin "8") (pinfunction "GND_MC_8") (pintype "passive"))
      (node (ref "U0601") (pin "9") (pinfunction "GND_MC_9") (pintype "passive"))
      (node (ref "U0701") (pin "10") (pinfunction "GND_MC_10") (pintype "passive"))
      (node (ref "U0701") (pin "23") (pinfunction "GND_MC_23") (pintype "passive"))
      (node (ref "U0701") (pin "24") (pinfunction "GND_MC_24") (pintype "passive"))
      (node (ref "U0701") (pin "25") (pinfunction "GND_MC_25") (pintype "passive"))
      (node (ref "U0701") (pin "26") (pinfunction "GND_MC_26") (pintype "passive"))
      (node (ref "U0701") (pin "33") (pinfunction "EP_33") (pintype "passive"))
      (node (ref "U0701") (pin "7") (pinfunction "GND_MC_7") (pintype "passive"))
      (node (ref "U0701") (pin "8") (pinfunction "GND_MC_8") (pintype "passive"))
      (node (ref "U0701") (pin "9") (pinfunction "GND_MC_9") (pintype "passive"))
      (node (ref "U0801") (pin "10") (pinfunction "GND_MC_10") (pintype "passive"))
      (node (ref "U0801") (pin "23") (pinfunction "GND_MC_23") (pintype "passive"))
      (node (ref "U0801") (pin "24") (pinfunction "GND_MC_24") (pintype "passive"))
      (node (ref "U0801") (pin "25") (pinfunction "GND_MC_25") (pintype "passive"))
      (node (ref "U0801") (pin "26") (pinfunction "GND_MC_26") (pintype "passive"))
      (node (ref "U0801") (pin "33") (pinfunction "EP_33") (pintype "passive"))
      (node (ref "U0801") (pin "7") (pinfunction "GND_MC_7") (pintype "passive"))
      (node (ref "U0801") (pin "8") (pinfunction "GND_MC_8") (pintype "passive"))
      (node (ref "U0801") (pin "9") (pinfunction "GND_MC_9") (pintype "passive"))
      (node (ref "U0921") (pin "4") (pinfunction "4_4") (pintype "passive"))
      (node (ref "U0951") (pin "2") (pinfunction "V-_2") (pintype "power_in"))
      (node (ref "U0951") (pin "3") (pinfunction "+IN_3") (pintype "input"))
      (node (ref "U1001") (pin "15") (pinfunction "GND_15") (pintype "power_in"))
      (node (ref "U1101") (pin "15") (pinfunction "GND_15") (pintype "power_in"))
      (node (ref "U1201") (pin "10") (pinfunction "AGND_10") (pintype "passive"))
      (node (ref "U1201") (pin "15") (pinfunction "PGND_15") (pintype "passive"))
      (node (ref "U1201") (pin "16") (pinfunction "PGND_16") (pintype "passive"))
      (node (ref "U1201") (pin "6") (pinfunction "SYNC_6") (pintype "input"))
      (node (ref "U1201") (pin "7") (pinfunction "FPWM_7") (pintype "input"))
      (node (ref "U1201") (pin "PAD") (pinfunction "EP_PAD") (pintype "passive"))
      (node (ref "U1201") (pin "PAD1") (pinfunction "EP_PAD1") (pintype "passive"))
      (node (ref "U1201") (pin "PAD10") (pinfunction "EP_PAD10") (pintype "passive"))
      (node (ref "U1201") (pin "PAD11") (pinfunction "EP_PAD11") (pintype "passive"))
      (node (ref "U1201") (pin "PAD12") (pinfunction "EP_PAD12") (pintype "passive"))
      (node (ref "U1201") (pin "PAD13") (pinfunction "EP_PAD13") (pintype "passive"))
      (node (ref "U1201") (pin "PAD2") (pinfunction "EP_PAD2") (pintype "passive"))
      (node (ref "U1201") (pin "PAD3") (pinfunction "EP_PAD3") (pintype "passive"))
      (node (ref "U1201") (pin "PAD4") (pinfunction "EP_PAD4") (pintype "passive"))
      (node (ref "U1201") (pin "PAD5") (pinfunction "EP_PAD5") (pintype "passive"))
      (node (ref "U1201") (pin "PAD6") (pinfunction "EP_PAD6") (pintype "passive"))
      (node (ref "U1201") (pin "PAD7") (pinfunction "EP_PAD7") (pintype "passive"))
      (node (ref "U1201") (pin "PAD8") (pinfunction "EP_PAD8") (pintype "passive"))
      (node (ref "U1201") (pin "PAD9") (pinfunction "EP_PAD9") (pintype "passive"))
      (node (ref "U1301") (pin "10") (pinfunction "PGND_10") (pintype "passive"))
      (node (ref "U1301") (pin "3") (pinfunction "VSS_3") (pintype "passive"))
      (node (ref "U1301") (pin "7") (pinfunction "SYNC_7") (pintype "input"))
      (node (ref "X0201") (pin "3") (pinfunction "3_3") (pintype "passive"))
      (node (ref "X0201") (pin "5") (pinfunction "5_5") (pintype "passive"))
      (node (ref "X0201") (pin "9") (pinfunction "9_9") (pintype "passive"))
      (node (ref "X0601") (pin "2") (pinfunction "2_2") (pintype "passive"))
      (node (ref "X0601") (pin "4") (pinfunction "4_4") (pintype "passive"))
      (node (ref "X1052") (pin "1") (pinfunction "1_1") (pintype "passive"))
      (node (ref "X1052") (pin "2") (pinfunction "2_2") (pintype "passive"))
      (node (ref "X1152") (pin "1") (pinfunction "1_1") (pintype "passive"))
      (node (ref "X1152") (pin "2") (pinfunction "2_2") (pintype "passive"))
      (node (ref "X1211") (pin "2") (pinfunction "2_2") (pintype "passive"))
      (node (ref "X1401") (pin "GND") (pinfunction "GND_GND") (pintype "passive"))
      (node (ref "X1501") (pin "2") (pinfunction "2_2") (pintype "passive"))
      (node (ref "X1501") (pin "3") (pinfunction "2_3") (pintype "passive"))
      (node (ref "X1501") (pin "4") (pinfunction "2_4") (pintype "passive"))
      (node (ref "X1501") (pin "5") (pinfunction "2_5") (pintype "passive"))
      (node (ref "X1511") (pin "2") (pinfunction "2_2") (pintype "passive"))
      (node (ref "X1511") (pin "3") (pinfunction "2_3") (pintype "passive"))
      (node (ref "X1511") (pin "4") (pinfunction "2_4") (pintype "passive"))
      (node (ref "X1511") (pin "5") (pinfunction "2_5") (pintype "passive"))
    )
    (net (code "61") (name "MCU_NRST") (class "Default")
      (node (ref "C0213") (pin "1") (pinfunction "1_1") (pintype "passive"))
      (node (ref "S0212") (pin "2") (pinfunction "S_2") (pintype "passive"))
      (node (ref "U0101") (pin "7") (pinfunction "NRST_7") (pintype "bidirectional"))
      (node (ref "X0201") (pin "10") (pinfunction "10_10") (pintype "passive"))
    )
    (net (code "62") (name "MCU_VBAT") (class "Default")
      (node (ref "C0451") (pin "1") (pinfunction "1_1") (pintype "passive"))
      (node (ref "TP_VBAT") (pin "TP") (pinfunction "TP_TP") (pintype "input"))
      (node (ref "U0101") (pin "1") (pinfunction "VBAT_1") (pintype "power_in"))
    )
    (net (code "63") (name "MCU_VDD") (class "Default")
      (node (ref "C0401") (pin "1") (pinfunction "1_1") (pintype "passive"))
      (node (ref "C0402") (pin "1") (pinfunction "1_1") (pintype "passive"))
      (node (ref "C0403") (pin "1") (pinfunction "1_1") (pintype "passive"))
      (node (ref "C0410") (pin "1") (pinfunction "1_1") (pintype "passive"))
      (node (ref "L0411") (pin "1") (pinfunction "1_1") (pintype "passive"))
      (node (ref "SJ0401") (pin "2") (pinfunction "2_2") (pintype "passive"))
      (node (ref "U0101") (pin "19") (pinfunction "VDD_19") (pintype "power_in"))
      (node (ref "U0101") (pin "32") (pinfunction "VDD_32") (pintype "power_in"))
      (node (ref "U0101") (pin "64") (pinfunction "VDD_64") (pintype "power_in"))
    )
    (net (code "64") (name "MCU_VDDA") (class "Default")
      (node (ref "C0412") (pin "1") (pinfunction "1_1") (pintype "passive"))
      (node (ref "C0413") (pin "1") (pinfunction "1_1") (pintype "passive"))
      (node (ref "L0411") (pin "2") (pinfunction "2_2") (pintype "passive"))
      (node (ref "U0101") (pin "13") (pinfunction "VDDA_VREF_P_13") (pintype "power_in"))
    )
    (net (code "65") (name "MCU_VREF_M") (class "Default")
      (node (ref "R0441") (pin "2") (pinfunction "2_2") (pintype "passive"))
      (node (ref "U0101") (pin "12") (pinfunction "VSSA_VREF_M_12") (pintype "passive"))
    )
    (net (code "66") (name "MP_CAT_CTS_R") (class "Default")
      (node (ref "R1103") (pin "2") (pinfunction "2_2") (pintype "passive"))
      (node (ref "U1101") (pin "10") (pinfunction "T2IN_10") (pintype "input"))
    )
    (net (code "67") (name "MP_CAT_RTR_R") (class "Default")
      (node (ref "R1104") (pin "2") (pinfunction "2_2") (pintype "passive"))
      (node (ref "U1101") (pin "9") (pinfunction "R2OUT_9") (pintype "output"))
    )
    (net (code "68") (name "MP_CAT_RXD_R") (class "Default")
      (node (ref "R1101") (pin "2") (pinfunction "2_2") (pintype "passive"))
      (node (ref "U1101") (pin "11") (pinfunction "T1IN_11") (pintype "input"))
    )
    (net (code "69") (name "MP_CAT_TXD_R") (class "Default")
      (node (ref "R1102") (pin "2") (pinfunction "2_2") (pintype "passive"))
      (node (ref "U1101") (pin "12") (pinfunction "R1OUT_12") (pintype "output"))
    )
    (net (code "70") (name "MP_RS_CTS_R") (class "Default")
      (node (ref "R1003") (pin "2") (pinfunction "2_2") (pintype "passive"))
      (node (ref "U1001") (pin "10") (pinfunction "T2IN_10") (pintype "input"))
    )
    (net (code "71") (name "MP_RS_RTR_R") (class "Default")
      (node (ref "R1004") (pin "2") (pinfunction "2_2") (pintype "passive"))
      (node (ref "U1001") (pin "9") (pinfunction "R2OUT_9") (pintype "output"))
    )
    (net (code "72") (name "MP_RS_RXD_R") (class "Default")
      (node (ref "R1001") (pin "2") (pinfunction "2_2") (pintype "passive"))
      (node (ref "U1001") (pin "11") (pinfunction "T1IN_11") (pintype "input"))
    )
    (net (code "73") (name "MP_RS_TXD_R") (class "Default")
      (node (ref "R1002") (pin "2") (pinfunction "2_2") (pintype "passive"))
      (node (ref "U1001") (pin "12") (pinfunction "R1OUT_12") (pintype "output"))
    )
    (net (code "74") (name "Net-(C1211-Pad1)") (class "Default")
      (node (ref "C1211") (pin "1") (pinfunction "1_1") (pintype "passive"))
      (node (ref "L1211") (pin "2") (pinfunction "2_2") (pintype "passive"))
      (node (ref "U1201") (pin "1") (pinfunction "SW_1") (pintype "passive"))
      (node (ref "U1201") (pin "2") (pinfunction "SW_2") (pintype "passive"))
    )
    (net (code "75") (name "Net-(C1403-Pad2)") (class "Default")
      (node (ref "C1403") (pin "2") (pinfunction "2_2") (pintype "passive"))
      (node (ref "R1402") (pin "2") (pinfunction "2_2") (pintype "passive"))
      (node (ref "X1401") (pin "JSHIELD") (pinfunction "SHIELD_JSHIELD") (pintype "passive"))
      (node (ref "X1401") (pin "JSHIELD@2") (pinfunction "SHIELD_JSHIELD@2") (pintype "passive"))
      (node (ref "X1401") (pin "JSHIELD@3") (pinfunction "SHIELD_JSHIELD@3") (pintype "passive"))
      (node (ref "X1401") (pin "JSHIELD@4") (pinfunction "SHIELD_JSHIELD@4") (pintype "passive"))
      (node (ref "X1401") (pin "JSHIELD@5") (pinfunction "SHIELD_JSHIELD@5") (pintype "passive"))
      (node (ref "X1401") (pin "JSHIELD@6") (pinfunction "SHIELD_JSHIELD@6") (pintype "passive"))
    )
    (net (code "76") (name "Net-(U0601-SO)") (class "Default")
      (node (ref "R0611") (pin "2") (pinfunction "2_2") (pintype "passive"))
      (node (ref "U0601") (pin "22") (pinfunction "SO_22") (pintype "output"))
    )
    (net (code "77") (name "Net-(U0701-SO)") (class "Default")
      (node (ref "R0711") (pin "2") (pinfunction "2_2") (pintype "passive"))
      (node (ref "U0701") (pin "22") (pinfunction "SO_22") (pintype "output"))
    )
    (net (code "78") (name "Net-(U0801-SO)") (class "Default")
      (node (ref "R0811") (pin "2") (pinfunction "2_2") (pintype "passive"))
      (node (ref "U0801") (pin "22") (pinfunction "SO_22") (pintype "output"))
    )
    (net (code "79") (name "Net-(U0951-OUT)") (class "Default")
      (node (ref "D0951") (pin "C") (pinfunction "C_C") (pintype "passive"))
      (node (ref "R0952") (pin "1") (pinfunction "1_1") (pintype "passive"))
      (node (ref "U0951") (pin "1") (pinfunction "OUT_1") (pintype "output"))
    )
    (net (code "80") (name "Net-(U1001A-C1-)") (class "Default")
      (node (ref "C1002") (pin "2") (pinfunction "2_2") (pintype "passive"))
      (node (ref "U1001") (pin "3") (pinfunction "C1-_3") (pintype "bidirectional"))
    )
    (net (code "81") (name "Net-(U1001A-C2-)") (class "Default")
      (node (ref "C1003") (pin "2") (pinfunction "2_2") (pintype "passive"))
      (node (ref "U1001") (pin "5") (pinfunction "C2-_5") (pintype "bidirectional"))
    )
    (net (code "82") (name "Net-(U1101A-C1-)") (class "Default")
      (node (ref "C1102") (pin "2") (pinfunction "2_2") (pintype "passive"))
      (node (ref "U1101") (pin "3") (pinfunction "C1-_3") (pintype "bidirectional"))
    )
    (net (code "83") (name "Net-(U1101A-C2-)") (class "Default")
      (node (ref "C1103") (pin "2") (pinfunction "2_2") (pintype "passive"))
      (node (ref "U1101") (pin "5") (pinfunction "C2-_5") (pintype "bidirectional"))
    )
    (net (code "84") (name "Net-(U1201-BIAS)") (class "Default")
      (node (ref "C1212") (pin "1") (pinfunction "1_1") (pintype "passive"))
      (node (ref "R1211") (pin "1") (pinfunction "1_1") (pintype "passive"))
      (node (ref "U1201") (pin "5") (pinfunction "BIAS_5") (pintype "power_in"))
    )
    (net (code "85") (name "Net-(U1201-CBOOT)") (class "Default")
      (node (ref "C1211") (pin "2") (pinfunction "2_2") (pintype "passive"))
      (node (ref "U1201") (pin "3") (pinfunction "CBOOT_3") (pintype "passive"))
    )
    (net (code "86") (name "Net-(U1201-VCC)") (class "Default")
      (node (ref "C1205") (pin "2") (pinfunction "2_2") (pintype "passive"))
      (node (ref "U1201") (pin "4") (pinfunction "VCC_4") (pintype "passive"))
    )
    (net (code "87") (name "Net-(U1301-LBI)") (class "Default")
      (node (ref "R1301") (pin "2") (pinfunction "2_2") (pintype "passive"))
      (node (ref "R1302") (pin "1") (pinfunction "1_1") (pintype "passive"))
      (node (ref "U1301") (pin "6") (pinfunction "LBI_6") (pintype "input"))
    )
    (net (code "88") (name "Net-(U1301-SW)") (class "Default")
      (node (ref "L1311") (pin "2") (pinfunction "2_2") (pintype "passive"))
      (node (ref "L1311") (pin "4") (pinfunction "2_4") (pintype "passive"))
      (node (ref "U1301") (pin "9") (pinfunction "SW_9") (pintype "passive"))
    )
    (net (code "89") (name "PA0") (class "Default")
      (node (ref "R1101") (pin "1") (pinfunction "1_1") (pintype "passive"))
      (node (ref "U0101") (pin "14") (pinfunction "PA0_WKUP_14") (pintype "bidirectional"))
    )
    (net (code "90") (name "PA1") (class "Default")
      (node (ref "R1102") (pin "1") (pinfunction "1_1") (pintype "passive"))
      (node (ref "U0101") (pin "15") (pinfunction "PA1_15") (pintype "bidirectional"))
    )
    (net (code "91") (name "PA3") (class "Default")
      (node (ref "R0922") (pin "1") (pinfunction "1_1") (pintype "passive"))
      (node (ref "U0101") (pin "17") (pinfunction "PA3_17") (pintype "bidirectional"))
    )
    (net (code "92") (name "PA5") (class "Default")
      (node (ref "R0621") (pin "1") (pinfunction "1_1") (pintype "passive"))
      (node (ref "U0101") (pin "21") (pinfunction "PA5_21") (pintype "bidirectional"))
    )
    (net (code "93") (name "PA6") (class "Default")
      (node (ref "R0622") (pin "1") (pinfunction "1_1") (pintype "passive"))
      (node (ref "U0101") (pin "22") (pinfunction "PA6_22") (pintype "bidirectional"))
    )
    (net (code "94") (name "PA7") (class "Default")
      (node (ref "R0623") (pin "1") (pinfunction "1_1") (pintype "passive"))
      (node (ref "U0101") (pin "23") (pinfunction "PA7_23") (pintype "bidirectional"))
    )
    (net (code "95") (name "PA9") (class "Default")
      (node (ref "PF1411") (pin "1") (pinfunction "1_1") (pintype "passive"))
      (node (ref "U0101") (pin "42") (pinfunction "PA9_42") (pintype "bidirectional"))
      (node (ref "X1401") (pin "VBUS") (pinfunction "J_VUSB_VBUS") (pintype "power_in"))
    )
    (net (code "96") (name "PA10") (class "Default")
      (node (ref "U0101") (pin "43") (pinfunction "PA10_43") (pintype "bidirectional"))
      (node (ref "X1401") (pin "ID") (pinfunction "J_ID_ID") (pintype "bidirectional"))
    )
    (net (code "97") (name "PA11") (class "Default")
      (node (ref "U0101") (pin "44") (pinfunction "PA11_44") (pintype "bidirectional"))
      (node (ref "X1401") (pin "D-") (pinfunction "J_D-_D-") (pintype "bidirectional"))
    )
    (net (code "98") (name "PA12") (class "Default")
      (node (ref "U0101") (pin "45") (pinfunction "PA12_45") (pintype "bidirectional"))
      (node (ref "X1401") (pin "D+") (pinfunction "J_D+_D+") (pintype "bidirectional"))
    )
    (net (code "99") (name "PA13") (class "Default")
      (node (ref "R0231") (pin "1") (pinfunction "1_1") (pintype "passive"))
      (node (ref "U0101") (pin "46") (pinfunction "PA13_JTMS_SWDIO_46") (pintype "bidirectional"))
      (node (ref "X0201") (pin "2") (pinfunction "2_2") (pintype "passive"))
    )
    (net (code "100") (name "PA14") (class "Default")
      (node (ref "R0232") (pin "2") (pinfunction "2_2") (pintype "passive"))
      (node (ref "U0101") (pin "49") (pinfunction "PA14_JTCK_SWCLK_49") (pintype "bidirectional"))
      (node (ref "X0201") (pin "4") (pinfunction "4_4") (pintype "passive"))
    )
    (net (code "101") (name "PA15") (class "Default")
      (node (ref "R1103") (pin "1") (pinfunction "1_1") (pintype "passive"))
      (node (ref "U0101") (pin "50") (pinfunction "PA15_JTDI_50") (pintype "bidirectional"))
    )
    (net (code "102") (name "PB0") (class "Default")
      (node (ref "R0624") (pin "1") (pinfunction "1_1") (pintype "passive"))
      (node (ref "U0101") (pin "26") (pinfunction "PB0_26") (pintype "bidirectional"))
    )
    (net (code "103") (name "PB1") (class "Default")
      (node (ref "R0724") (pin "1") (pinfunction "1_1") (pintype "passive"))
      (node (ref "U0101") (pin "27") (pinfunction "PB1_27") (pintype "bidirectional"))
    )
    (net (code "104") (name "PB2") (class "Default")
      (node (ref "R0824") (pin "1") (pinfunction "1_1") (pintype "passive"))
      (node (ref "U0101") (pin "28") (pinfunction "PB2_28") (pintype "bidirectional"))
    )
    (net (code "105") (name "PB6") (class "Default")
      (node (ref "R0512") (pin "1") (pinfunction "1_1") (pintype "passive"))
      (node (ref "U0101") (pin "58") (pinfunction "PB6_58") (pintype "bidirectional"))
      (node (ref "X0601") (pin "1") (pinfunction "1_1") (pintype "passive"))
    )
    (net (code "106") (name "PB7") (class "Default")
      (node (ref "R1104") (pin "1") (pinfunction "1_1") (pintype "passive"))
      (node (ref "U0101") (pin "59") (pinfunction "PB7_59") (pintype "bidirectional"))
    )
    (net (code "107") (name "PB9") (class "Default")
      (node (ref "R0511") (pin "1") (pinfunction "1_1") (pintype "passive"))
      (node (ref "U0101") (pin "62") (pinfunction "PB9_62") (pintype "bidirectional"))
      (node (ref "X0601") (pin "3") (pinfunction "3_3") (pintype "passive"))
    )
    (net (code "108") (name "PB10") (class "Default")
      (node (ref "R1002") (pin "1") (pinfunction "1_1") (pintype "passive"))
      (node (ref "U0101") (pin "29") (pinfunction "PB10_29") (pintype "bidirectional"))
    )
    (net (code "109") (name "PB11") (class "Default")
      (node (ref "R0626") (pin "1") (pinfunction "1_1") (pintype "passive"))
      (node (ref "U0101") (pin "30") (pinfunction "PB11_30") (pintype "bidirectional"))
    )
    (net (code "110") (name "PB12") (class "Default")
      (node (ref "R1003") (pin "1") (pinfunction "1_1") (pintype "passive"))
      (node (ref "U0101") (pin "33") (pinfunction "PB12_33") (pintype "bidirectional"))
    )
    (net (code "111") (name "PB13") (class "Default")
      (node (ref "R1004") (pin "1") (pinfunction "1_1") (pintype "passive"))
      (node (ref "U0101") (pin "34") (pinfunction "PB13_34") (pintype "bidirectional"))
    )
    (net (code "112") (name "PC0") (class "Default")
      (node (ref "R0952") (pin "2") (pinfunction "2_2") (pintype "passive"))
      (node (ref "U0101") (pin "8") (pinfunction "PC0_8") (pintype "bidirectional"))
    )
    (net (code "113") (name "PC1") (class "Default")
      (node (ref "R1001") (pin "1") (pinfunction "1_1") (pintype "passive"))
      (node (ref "U0101") (pin "9") (pinfunction "PC1_9") (pintype "bidirectional"))
    )
    (net (code "114") (name "PC2") (class "Default")
      (node (ref "D0961") (pin "A") (pinfunction "A_A") (pintype "passive"))
      (node (ref "R0961") (pin "2") (pinfunction "2_2") (pintype "passive"))
      (node (ref "U0101") (pin "10") (pinfunction "PC2_10") (pintype "bidirectional"))
    )
    (net (code "115") (name "PC3") (class "Default")
      (node (ref "R0921") (pin "1") (pinfunction "1_1") (pintype "passive"))
      (node (ref "U0101") (pin "11") (pinfunction "PC3_11") (pintype "bidirectional"))
    )
    (net (code "116") (name "PC4") (class "Default")
      (node (ref "R0625") (pin "1") (pinfunction "1_1") (pintype "passive"))
      (node (ref "U0101") (pin "24") (pinfunction "PC4_24") (pintype "bidirectional"))
    )
    (net (code "117") (name "PC14_OSC32_IN") (class "Default")
      (node (ref "C0331") (pin "-") (pinfunction "E_-") (pintype "passive"))
      (node (ref "C0332") (pin "1") (pinfunction "1_1") (pintype "passive"))
      (node (ref "Q0321") (pin "2") (pinfunction "2_2") (pintype "passive"))
      (node (ref "U0101") (pin "3") (pinfunction "PC14_OSC32_IN_3") (pintype "bidirectional"))
    )
    (net (code "118") (name "PC15_OSC32_OUT") (class "Default")
      (node (ref "C0311") (pin "1") (pinfunction "1_1") (pintype "passive"))
      (node (ref "Q0321") (pin "1") (pinfunction "1_1") (pintype "passive"))
      (node (ref "U0101") (pin "4") (pinfunction "PC15_OSC32_OUT_4") (pintype "bidirectional"))
    )
    (net (code "119") (name "PH0") (class "Default")
      (node (ref "U0101") (pin "5") (pinfunction "PH0_OSC_IN_5") (pintype "bidirectional"))
    )
    (net (code "120") (name "PH1") (class "Default")
      (node (ref "U0101") (pin "6") (pinfunction "PH1_OSC_OUT_6") (pintype "bidirectional"))
    )
    (net (code "121") (name "PH3_BOOT0") (class "Default")
      (node (ref "R0221") (pin "2") (pinfunction "2_2") (pintype "passive"))
      (node (ref "U0101") (pin "60") (pinfunction "BOOT0_60") (pintype "output"))
      (node (ref "X0222") (pin "2") (pinfunction "2_2") (pintype "passive"))
    )
    (net (code "122") (name "RELAY1") (class "Default")
      (node (ref "U0601") (pin "1") (pinfunction "OUT0_1") (pintype "passive"))
      (node (ref "X1601") (pin "1") (pinfunction "1_1") (pintype "passive"))
    )
    (net (code "123") (name "RELAY2") (class "Default")
      (node (ref "U0601") (pin "2") (pinfunction "OUT1_2") (pintype "passive"))
      (node (ref "X1601") (pin "2") (pinfunction "2_2") (pintype "passive"))
    )
    (net (code "124") (name "RELAY3") (class "Default")
      (node (ref "U0601") (pin "4") (pinfunction "OUT2_4") (pintype "passive"))
      (node (ref "X1601") (pin "3") (pinfunction "3_3") (pintype "passive"))
    )
    (net (code "125") (name "RELAY4") (class "Default")
      (node (ref "U0601") (pin "5") (pinfunction "OUT3_5") (pintype "passive"))
      (node (ref "X1601") (pin "4") (pinfunction "4_4") (pintype "passive"))
    )
    (net (code "126") (name "RELAY5") (class "Default")
      (node (ref "U0601") (pin "12") (pinfunction "OUT4_12") (pintype "passive"))
      (node (ref "X1601") (pin "5") (pinfunction "5_5") (pintype "passive"))
    )
    (net (code "127") (name "RELAY6") (class "Default")
      (node (ref "U0601") (pin "13") (pinfunction "OUT5_13") (pintype "passive"))
      (node (ref "X1601") (pin "6") (pinfunction "6_6") (pintype "passive"))
    )
    (net (code "128") (name "RELAY7") (class "Default")
      (node (ref "U0601") (pin "15") (pinfunction "OUT6_15") (pintype "passive"))
      (node (ref "X1601") (pin "7") (pinfunction "7_7") (pintype "passive"))
    )
    (net (code "129") (name "RELAY8") (class "Default")
      (node (ref "U0601") (pin "16") (pinfunction "OUT7_16") (pintype "passive"))
      (node (ref "X1601") (pin "8") (pinfunction "8_8") (pintype "passive"))
    )
    (net (code "130") (name "RELAY9") (class "Default")
      (node (ref "U0601") (pin "17") (pinfunction "OUT8_17") (pintype "passive"))
      (node (ref "X1601") (pin "9") (pinfunction "9_9") (pintype "passive"))
    )
    (net (code "131") (name "RELAY10") (class "Default")
      (node (ref "U0601") (pin "18") (pinfunction "OUT9_18") (pintype "passive"))
      (node (ref "X1601") (pin "10") (pinfunction "10_10") (pintype "passive"))
    )
    (net (code "132") (name "RELAY11") (class "Default")
      (node (ref "U0601") (pin "20") (pinfunction "OUT10_20") (pintype "passive"))
      (node (ref "X1601") (pin "11") (pinfunction "11_11") (pintype "passive"))
    )
    (net (code "133") (name "RELAY12") (class "Default")
      (node (ref "U0601") (pin "21") (pinfunction "OUT11_21") (pintype "passive"))
      (node (ref "X1601") (pin "12") (pinfunction "12_12") (pintype "passive"))
    )
    (net (code "134") (name "RELAY13") (class "Default")
      (node (ref "U0601") (pin "28") (pinfunction "OUT12_28") (pintype "passive"))
      (node (ref "X1601") (pin "13") (pinfunction "13_13") (pintype "passive"))
    )
    (net (code "135") (name "RELAY14") (class "Default")
      (node (ref "U0601") (pin "29") (pinfunction "OUT13_29") (pintype "passive"))
      (node (ref "X1601") (pin "14") (pinfunction "14_14") (pintype "passive"))
    )
    (net (code "136") (name "RELAY15") (class "Default")
      (node (ref "U0601") (pin "31") (pinfunction "OUT14_31") (pintype "passive"))
      (node (ref "X1601") (pin "15") (pinfunction "15_15") (pintype "passive"))
    )
    (net (code "137") (name "RELAY16") (class "Default")
      (node (ref "U0601") (pin "32") (pinfunction "OUT15_32") (pintype "passive"))
      (node (ref "X1601") (pin "16") (pinfunction "16_16") (pintype "passive"))
    )
    (net (code "138") (name "RELAY17") (class "Default")
      (node (ref "U0701") (pin "1") (pinfunction "OUT0_1") (pintype "passive"))
      (node (ref "X1601") (pin "17") (pinfunction "17_17") (pintype "passive"))
    )
    (net (code "139") (name "RELAY18") (class "Default")
      (node (ref "U0701") (pin "2") (pinfunction "OUT1_2") (pintype "passive"))
      (node (ref "X1601") (pin "18") (pinfunction "18_18") (pintype "passive"))
    )
    (net (code "140") (name "RELAY19") (class "Default")
      (node (ref "U0701") (pin "4") (pinfunction "OUT2_4") (pintype "passive"))
      (node (ref "X1601") (pin "19") (pinfunction "19_19") (pintype "passive"))
    )
    (net (code "141") (name "RELAY20") (class "Default")
      (node (ref "U0701") (pin "5") (pinfunction "OUT3_5") (pintype "passive"))
      (node (ref "X1601") (pin "20") (pinfunction "20_20") (pintype "passive"))
    )
    (net (code "142") (name "RELAY21") (class "Default")
      (node (ref "U0701") (pin "12") (pinfunction "OUT4_12") (pintype "passive"))
      (node (ref "X1602") (pin "1") (pinfunction "1_1") (pintype "passive"))
    )
    (net (code "143") (name "RELAY22") (class "Default")
      (node (ref "U0701") (pin "13") (pinfunction "OUT5_13") (pintype "passive"))
      (node (ref "X1602") (pin "2") (pinfunction "2_2") (pintype "passive"))
    )
    (net (code "144") (name "RELAY23") (class "Default")
      (node (ref "U0701") (pin "15") (pinfunction "OUT6_15") (pintype "passive"))
      (node (ref "X1602") (pin "3") (pinfunction "3_3") (pintype "passive"))
    )
    (net (code "145") (name "RELAY24") (class "Default")
      (node (ref "U0701") (pin "16") (pinfunction "OUT7_16") (pintype "passive"))
      (node (ref "X1602") (pin "4") (pinfunction "4_4") (pintype "passive"))
    )
    (net (code "146") (name "RELAY25") (class "Default")
      (node (ref "U0701") (pin "17") (pinfunction "OUT8_17") (pintype "passive"))
      (node (ref "X1602") (pin "5") (pinfunction "5_5") (pintype "passive"))
    )
    (net (code "147") (name "RELAY26") (class "Default")
      (node (ref "U0701") (pin "18") (pinfunction "OUT9_18") (pintype "passive"))
      (node (ref "X1602") (pin "6") (pinfunction "6_6") (pintype "passive"))
    )
    (net (code "148") (name "RELAY27") (class "Default")
      (node (ref "U0701") (pin "20") (pinfunction "OUT10_20") (pintype "passive"))
      (node (ref "X1602") (pin "7") (pinfunction "7_7") (pintype "passive"))
    )
    (net (code "149") (name "RELAY28") (class "Default")
      (node (ref "U0701") (pin "21") (pinfunction "OUT11_21") (pintype "passive"))
      (node (ref "X1602") (pin "8") (pinfunction "8_8") (pintype "passive"))
    )
    (net (code "150") (name "RELAY29") (class "Default")
      (node (ref "U0701") (pin "28") (pinfunction "OUT12_28") (pintype "passive"))
      (node (ref "X1602") (pin "9") (pinfunction "9_9") (pintype "passive"))
    )
    (net (code "151") (name "RELAY30") (class "Default")
      (node (ref "U0701") (pin "29") (pinfunction "OUT13_29") (pintype "passive"))
      (node (ref "X1602") (pin "10") (pinfunction "10_10") (pintype "passive"))
    )
    (net (code "152") (name "RELAY31") (class "Default")
      (node (ref "U0701") (pin "31") (pinfunction "OUT14_31") (pintype "passive"))
      (node (ref "X1602") (pin "11") (pinfunction "11_11") (pintype "passive"))
    )
    (net (code "153") (name "RELAY32") (class "Default")
      (node (ref "U0701") (pin "32") (pinfunction "OUT15_32") (pintype "passive"))
      (node (ref "X1602") (pin "12") (pinfunction "12_12") (pintype "passive"))
    )
    (net (code "154") (name "RELAY33") (class "Default")
      (node (ref "U0801") (pin "1") (pinfunction "OUT0_1") (pintype "passive"))
      (node (ref "X1602") (pin "13") (pinfunction "13_13") (pintype "passive"))
    )
    (net (code "155") (name "RELAY34") (class "Default")
      (node (ref "U0801") (pin "2") (pinfunction "OUT1_2") (pintype "passive"))
      (node (ref "X1602") (pin "14") (pinfunction "14_14") (pintype "passive"))
    )
    (net (code "156") (name "RELAY35") (class "Default")
      (node (ref "U0801") (pin "4") (pinfunction "OUT2_4") (pintype "passive"))
      (node (ref "X1602") (pin "15") (pinfunction "15_15") (pintype "passive"))
    )
    (net (code "157") (name "RELAY36") (class "Default")
      (node (ref "U0801") (pin "5") (pinfunction "OUT3_5") (pintype "passive"))
      (node (ref "X1602") (pin "16") (pinfunction "16_16") (pintype "passive"))
    )
    (net (code "158") (name "RM_FWD") (class "Default")
      (node (ref "L0901") (pin "2") (pinfunction "2_2") (pintype "passive"))
      (node (ref "X1501") (pin "1") (pinfunction "1_1") (pintype "passive"))
    )
    (net (code "159") (name "RM_REV") (class "Default")
      (node (ref "L0911") (pin "2") (pinfunction "2_2") (pintype "passive"))
      (node (ref "X1511") (pin "1") (pinfunction "1_1") (pintype "passive"))
    )
    (net (code "160") (name "RS_DTE_CTS") (class "Default")
      (node (ref "C1053") (pin "1") (pinfunction "1_1") (pintype "passive"))
      (node (ref "U1001") (pin "7") (pinfunction "T2OUT_7") (pintype "output"))
      (node (ref "X1053") (pin "1") (pinfunction "1_1") (pintype "passive"))
    )
    (net (code "161") (name "RS_DTE_RTR") (class "Default")
      (node (ref "C0054") (pin "1") (pinfunction "1_1") (pintype "passive"))
      (node (ref "U1001") (pin "8") (pinfunction "R2IN_8") (pintype "input"))
      (node (ref "X1053") (pin "2") (pinfunction "2_2") (pintype "passive"))
    )
    (net (code "162") (name "RS_DTE_RXD") (class "Default")
      (node (ref "C1051") (pin "1") (pinfunction "1_1") (pintype "passive"))
      (node (ref "U1001") (pin "14") (pinfunction "T1OUT_14") (pintype "output"))
      (node (ref "X1051") (pin "1") (pinfunction "1_1") (pintype "passive"))
    )
    (net (code "163") (name "RS_DTE_TXD") (class "Default")
      (node (ref "C1052") (pin "1") (pinfunction "1_1") (pintype "passive"))
      (node (ref "U1001") (pin "13") (pinfunction "R1IN_13") (pintype "input"))
      (node (ref "X1051") (pin "2") (pinfunction "2_2") (pintype "passive"))
    )
    (net (code "164") (name "RS_MX_C1P") (class "Default")
      (node (ref "C1002") (pin "1") (pinfunction "1_1") (pintype "passive"))
      (node (ref "U1001") (pin "1") (pinfunction "C1+_1") (pintype "bidirectional"))
    )
    (net (code "165") (name "RS_MX_C2P") (class "Default")
      (node (ref "C1003") (pin "1") (pinfunction "1_1") (pintype "passive"))
      (node (ref "U1001") (pin "4") (pinfunction "C2+_4") (pintype "bidirectional"))
    )
    (net (code "166") (name "RS_MX_VM") (class "Default")
      (node (ref "C1005") (pin "1") (pinfunction "1_1") (pintype "passive"))
      (node (ref "U1001") (pin "6") (pinfunction "V-_6") (pintype "bidirectional"))
    )
    (net (code "167") (name "RS_MX_VP") (class "Default")
      (node (ref "C1004") (pin "1") (pinfunction "1_1") (pintype "passive"))
      (node (ref "U1001") (pin "2") (pinfunction "V+_2") (pintype "bidirectional"))
    )
    (net (code "168") (name "SPI_DRV_C_~{CS}") (class "Default")
      (node (ref "R0724") (pin "2") (pinfunction "2_2") (pintype "passive"))
      (node (ref "U0701") (pin "14") (pinfunction "~{CS}_14") (pintype "input"))
    )
    (net (code "169") (name "SPI_DRV_EXT_~{CS}") (class "Default")
      (node (ref "R0824") (pin "2") (pinfunction "2_2") (pintype "passive"))
      (node (ref "U0801") (pin "14") (pinfunction "~{CS}_14") (pintype "input"))
    )
    (net (code "170") (name "SPI_DRV_L_~{CS}") (class "Default")
      (node (ref "R0624") (pin "2") (pinfunction "2_2") (pintype "passive"))
      (node (ref "U0601") (pin "14") (pinfunction "~{CS}_14") (pintype "input"))
    )
    (net (code "171") (name "SPI_DRV_PWM") (class "Default")
      (node (ref "R0626") (pin "2") (pinfunction "2_2") (pintype "passive"))
      (node (ref "U0601") (pin "30") (pinfunction "PWM_30") (pintype "input"))
      (node (ref "U0701") (pin "30") (pinfunction "PWM_30") (pintype "input"))
      (node (ref "U0801") (pin "30") (pinfunction "PWM_30") (pintype "input"))
    )
    (net (code "172") (name "SPI_DRV_SCLK") (class "Default")
      (node (ref "R0621") (pin "2") (pinfunction "2_2") (pintype "passive"))
      (node (ref "U0601") (pin "11") (pinfunction "SCLK_11") (pintype "input"))
      (node (ref "U0701") (pin "11") (pinfunction "SCLK_11") (pintype "input"))
      (node (ref "U0801") (pin "11") (pinfunction "SCLK_11") (pintype "input"))
    )
    (net (code "173") (name "SPI_DRV_SI") (class "Default")
      (node (ref "R0623") (pin "2") (pinfunction "2_2") (pintype "passive"))
      (node (ref "U0601") (pin "19") (pinfunction "SI_19") (pintype "input"))
      (node (ref "U0701") (pin "19") (pinfunction "SI_19") (pintype "input"))
      (node (ref "U0801") (pin "19") (pinfunction "SI_19") (pintype "input"))
    )
    (net (code "174") (name "SPI_DRV_SO") (class "Default")
      (node (ref "R0611") (pin "1") (pinfunction "1_1") (pintype "passive"))
      (node (ref "R0622") (pin "2") (pinfunction "2_2") (pintype "passive"))
      (node (ref "R0711") (pin "1") (pinfunction "1_1") (pintype "passive"))
      (node (ref "R0811") (pin "1") (pinfunction "1_1") (pintype "passive"))
    )
    (net (code "175") (name "SPI_DRV_~{RST}") (class "Default")
      (node (ref "R0625") (pin "2") (pinfunction "2_2") (pintype "passive"))
      (node (ref "U0601") (pin "27") (pinfunction "~{RST}_27") (pintype "input"))
      (node (ref "U0701") (pin "27") (pinfunction "~{RST}_27") (pintype "input"))
      (node (ref "U0801") (pin "27") (pinfunction "~{RST}_27") (pintype "input"))
    )
    (net (code "176") (name "SWR_IN_FWD") (class "Default")
      (node (ref "D0901") (pin "A") (pinfunction "A_A") (pintype "passive"))
      (node (ref "R0902") (pin "2") (pinfunction "2_2") (pintype "passive"))
      (node (ref "R0903") (pin "1") (pinfunction "1_1") (pintype "passive"))
      (node (ref "U0921") (pin "1") (pinfunction "1_1") (pintype "passive"))
    )
    (net (code "177") (name "SWR_IN_FWD_HI") (class "Default")
      (node (ref "C0901") (pin "1") (pinfunction "1_1") (pintype "passive"))
      (node (ref "L0901") (pin "1") (pinfunction "1_1") (pintype "passive"))
      (node (ref "R0901") (pin "2") (pinfunction "2_2") (pintype "passive"))
      (node (ref "R0902") (pin "1") (pinfunction "1_1") (pintype "passive"))
    )
    (net (code "178") (name "SWR_IN_REV") (class "Default")
      (node (ref "D0911") (pin "A") (pinfunction "A_A") (pintype "passive"))
      (node (ref "R0912") (pin "2") (pinfunction "2_2") (pintype "passive"))
      (node (ref "R0913") (pin "1") (pinfunction "1_1") (pintype "passive"))
      (node (ref "U0921") (pin "5") (pinfunction "5_5") (pintype "passive"))
    )
    (net (code "179") (name "SWR_IN_REV_HI") (class "Default")
      (node (ref "C0911") (pin "1") (pinfunction "1_1") (pintype "passive"))
      (node (ref "L0911") (pin "1") (pinfunction "1_1") (pintype "passive"))
      (node (ref "R0911") (pin "2") (pinfunction "2_2") (pintype "passive"))
      (node (ref "R0912") (pin "1") (pinfunction "1_1") (pintype "passive"))
    )
    (net (code "180") (name "SWR_SEL_FWD") (class "Default")
      (node (ref "R0921") (pin "2") (pinfunction "2_2") (pintype "passive"))
      (node (ref "U0921") (pin "7") (pinfunction "7_7") (pintype "input"))
    )
    (net (code "181") (name "SWR_SEL_PWR") (class "Default")
      (node (ref "D0951") (pin "A") (pinfunction "A_A") (pintype "passive"))
      (node (ref "R0951") (pin "2") (pinfunction "2_2") (pintype "passive"))
      (node (ref "U0921") (pin "2") (pinfunction "2_2") (pintype "passive"))
      (node (ref "U0921") (pin "6") (pinfunction "6_6") (pintype "passive"))
      (node (ref "U0951") (pin "4") (pinfunction "-IN_4") (pintype "input"))
    )
    (net (code "182") (name "SWR_SEL_REV") (class "Default")
      (node (ref "R0922") (pin "2") (pinfunction "2_2") (pintype "passive"))
      (node (ref "U0921") (pin "3") (pinfunction "3_3") (pintype "input"))
    )
    (net (code "183") (name "TPS_LBO") (class "Default")
      (node (ref "R1322") (pin "1") (pinfunction "1_1") (pintype "passive"))
      (node (ref "U1301") (pin "2") (pinfunction "LBO_2") (pintype "output"))
    )
    (net (code "184") (name "TPS_PG") (class "Default")
      (node (ref "R1321") (pin "1") (pinfunction "1_1") (pintype "passive"))
      (node (ref "U1301") (pin "4") (pinfunction "PG_4") (pintype "output"))
    )
    (net (code "185") (name "VDDUSB") (class "Default")
      (node (ref "PF1411") (pin "2") (pinfunction "2_2") (pintype "passive"))
      (node (ref "U0101") (pin "48") (pinfunction "VDDUSB_48") (pintype "power_in"))
    )
    (net (code "186") (name "unconnected-(U0101-PA2_WKUP-Pad16)") (class "Default")
      (node (ref "U0101") (pin "16") (pinfunction "PA2_WKUP_16") (pintype "bidirectional"))
    )
    (net (code "187") (name "unconnected-(U0101-PA4-Pad20)") (class "Default")
      (node (ref "U0101") (pin "20") (pinfunction "PA4_20") (pintype "bidirectional"))
    )
    (net (code "188") (name "unconnected-(U0101-PA8-Pad41)") (class "Default")
      (node (ref "U0101") (pin "41") (pinfunction "PA8_41") (pintype "bidirectional"))
    )
    (net (code "189") (name "unconnected-(U0101-PB3_JTDO_TRACESWO-Pad55)") (class "Default")
      (node (ref "U0101") (pin "55") (pinfunction "PB3_JTDO_TRACESWO_55") (pintype "bidirectional"))
    )
    (net (code "190") (name "unconnected-(U0101-PB4_NJTRST-Pad56)") (class "Default")
      (node (ref "U0101") (pin "56") (pinfunction "PB4_NJTRST_56") (pintype "bidirectional"))
    )
    (net (code "191") (name "unconnected-(U0101-PB5-Pad57)") (class "Default")
      (node (ref "U0101") (pin "57") (pinfunction "PB5_57") (pintype "bidirectional"))
    )
    (net (code "192") (name "unconnected-(U0101-PB8-Pad61)") (class "Default")
      (node (ref "U0101") (pin "61") (pinfunction "PB8_61") (pintype "bidirectional"))
    )
    (net (code "193") (name "unconnected-(U0101-PB14-Pad35)") (class "Default")
      (node (ref "U0101") (pin "35") (pinfunction "PB14_35") (pintype "bidirectional"))
    )
    (net (code "194") (name "unconnected-(U0101-PB15-Pad36)") (class "Default")
      (node (ref "U0101") (pin "36") (pinfunction "PB15_36") (pintype "bidirectional"))
    )
    (net (code "195") (name "unconnected-(U0101-PC5_WKUP-Pad25)") (class "Default")
      (node (ref "U0101") (pin "25") (pinfunction "PC5_WKUP_25") (pintype "bidirectional"))
    )
    (net (code "196") (name "unconnected-(U0101-PC6-Pad37)") (class "Default")
      (node (ref "U0101") (pin "37") (pinfunction "PC6_37") (pintype "bidirectional"))
    )
    (net (code "197") (name "unconnected-(U0101-PC7-Pad38)") (class "Default")
      (node (ref "U0101") (pin "38") (pinfunction "PC7_38") (pintype "bidirectional"))
    )
    (net (code "198") (name "unconnected-(U0101-PC8-Pad39)") (class "Default")
      (node (ref "U0101") (pin "39") (pinfunction "PC8_39") (pintype "bidirectional"))
    )
    (net (code "199") (name "unconnected-(U0101-PC9-Pad40)") (class "Default")
      (node (ref "U0101") (pin "40") (pinfunction "PC9_40") (pintype "bidirectional"))
    )
    (net (code "200") (name "unconnected-(U0101-PC10-Pad51)") (class "Default")
      (node (ref "U0101") (pin "51") (pinfunction "PC10_51") (pintype "bidirectional"))
    )
    (net (code "201") (name "unconnected-(U0101-PC11-Pad52)") (class "Default")
      (node (ref "U0101") (pin "52") (pinfunction "PC11_52") (pintype "bidirectional"))
    )
    (net (code "202") (name "unconnected-(U0101-PC12-Pad53)") (class "Default")
      (node (ref "U0101") (pin "53") (pinfunction "PC12_53") (pintype "bidirectional"))
    )
    (net (code "203") (name "unconnected-(U0101-PC13_WKUP-Pad2)") (class "Default")
      (node (ref "U0101") (pin "2") (pinfunction "PC13_WKUP_2") (pintype "bidirectional"))
    )
    (net (code "204") (name "unconnected-(U0101-PD2-Pad54)") (class "Default")
      (node (ref "U0101") (pin "54") (pinfunction "PD2_54") (pintype "bidirectional"))
    )
    (net (code "205") (name "unconnected-(U1201-NC-Pad14)") (class "Default")
      (node (ref "U1201") (pin "14") (pinfunction "NC_14") (pintype "no_connect"))
    )
    (net (code "206") (name "unconnected-(U1201-~{RESET}-Pad8)") (class "Default")
      (node (ref "U1201") (pin "8") (pinfunction "~{RESET}_8") (pintype "output"))
    )
    (net (code "207") (name "unconnected-(X0201-Pad6)") (class "Default")
      (node (ref "X0201") (pin "6") (pinfunction "6_6") (pintype "passive"))
    )
    (net (code "208") (name "unconnected-(X0201-Pad7)") (class "Default")
      (node (ref "X0201") (pin "7") (pinfunction "7_7") (pintype "passive"))
    )
    (net (code "209") (name "unconnected-(X0201-Pad8)") (class "Default")
      (node (ref "X0201") (pin "8") (pinfunction "8_8") (pintype "passive"))
    )
  )
)
